# final_schematic.net
KiCad netlist of a schematic drawn in EAGLE
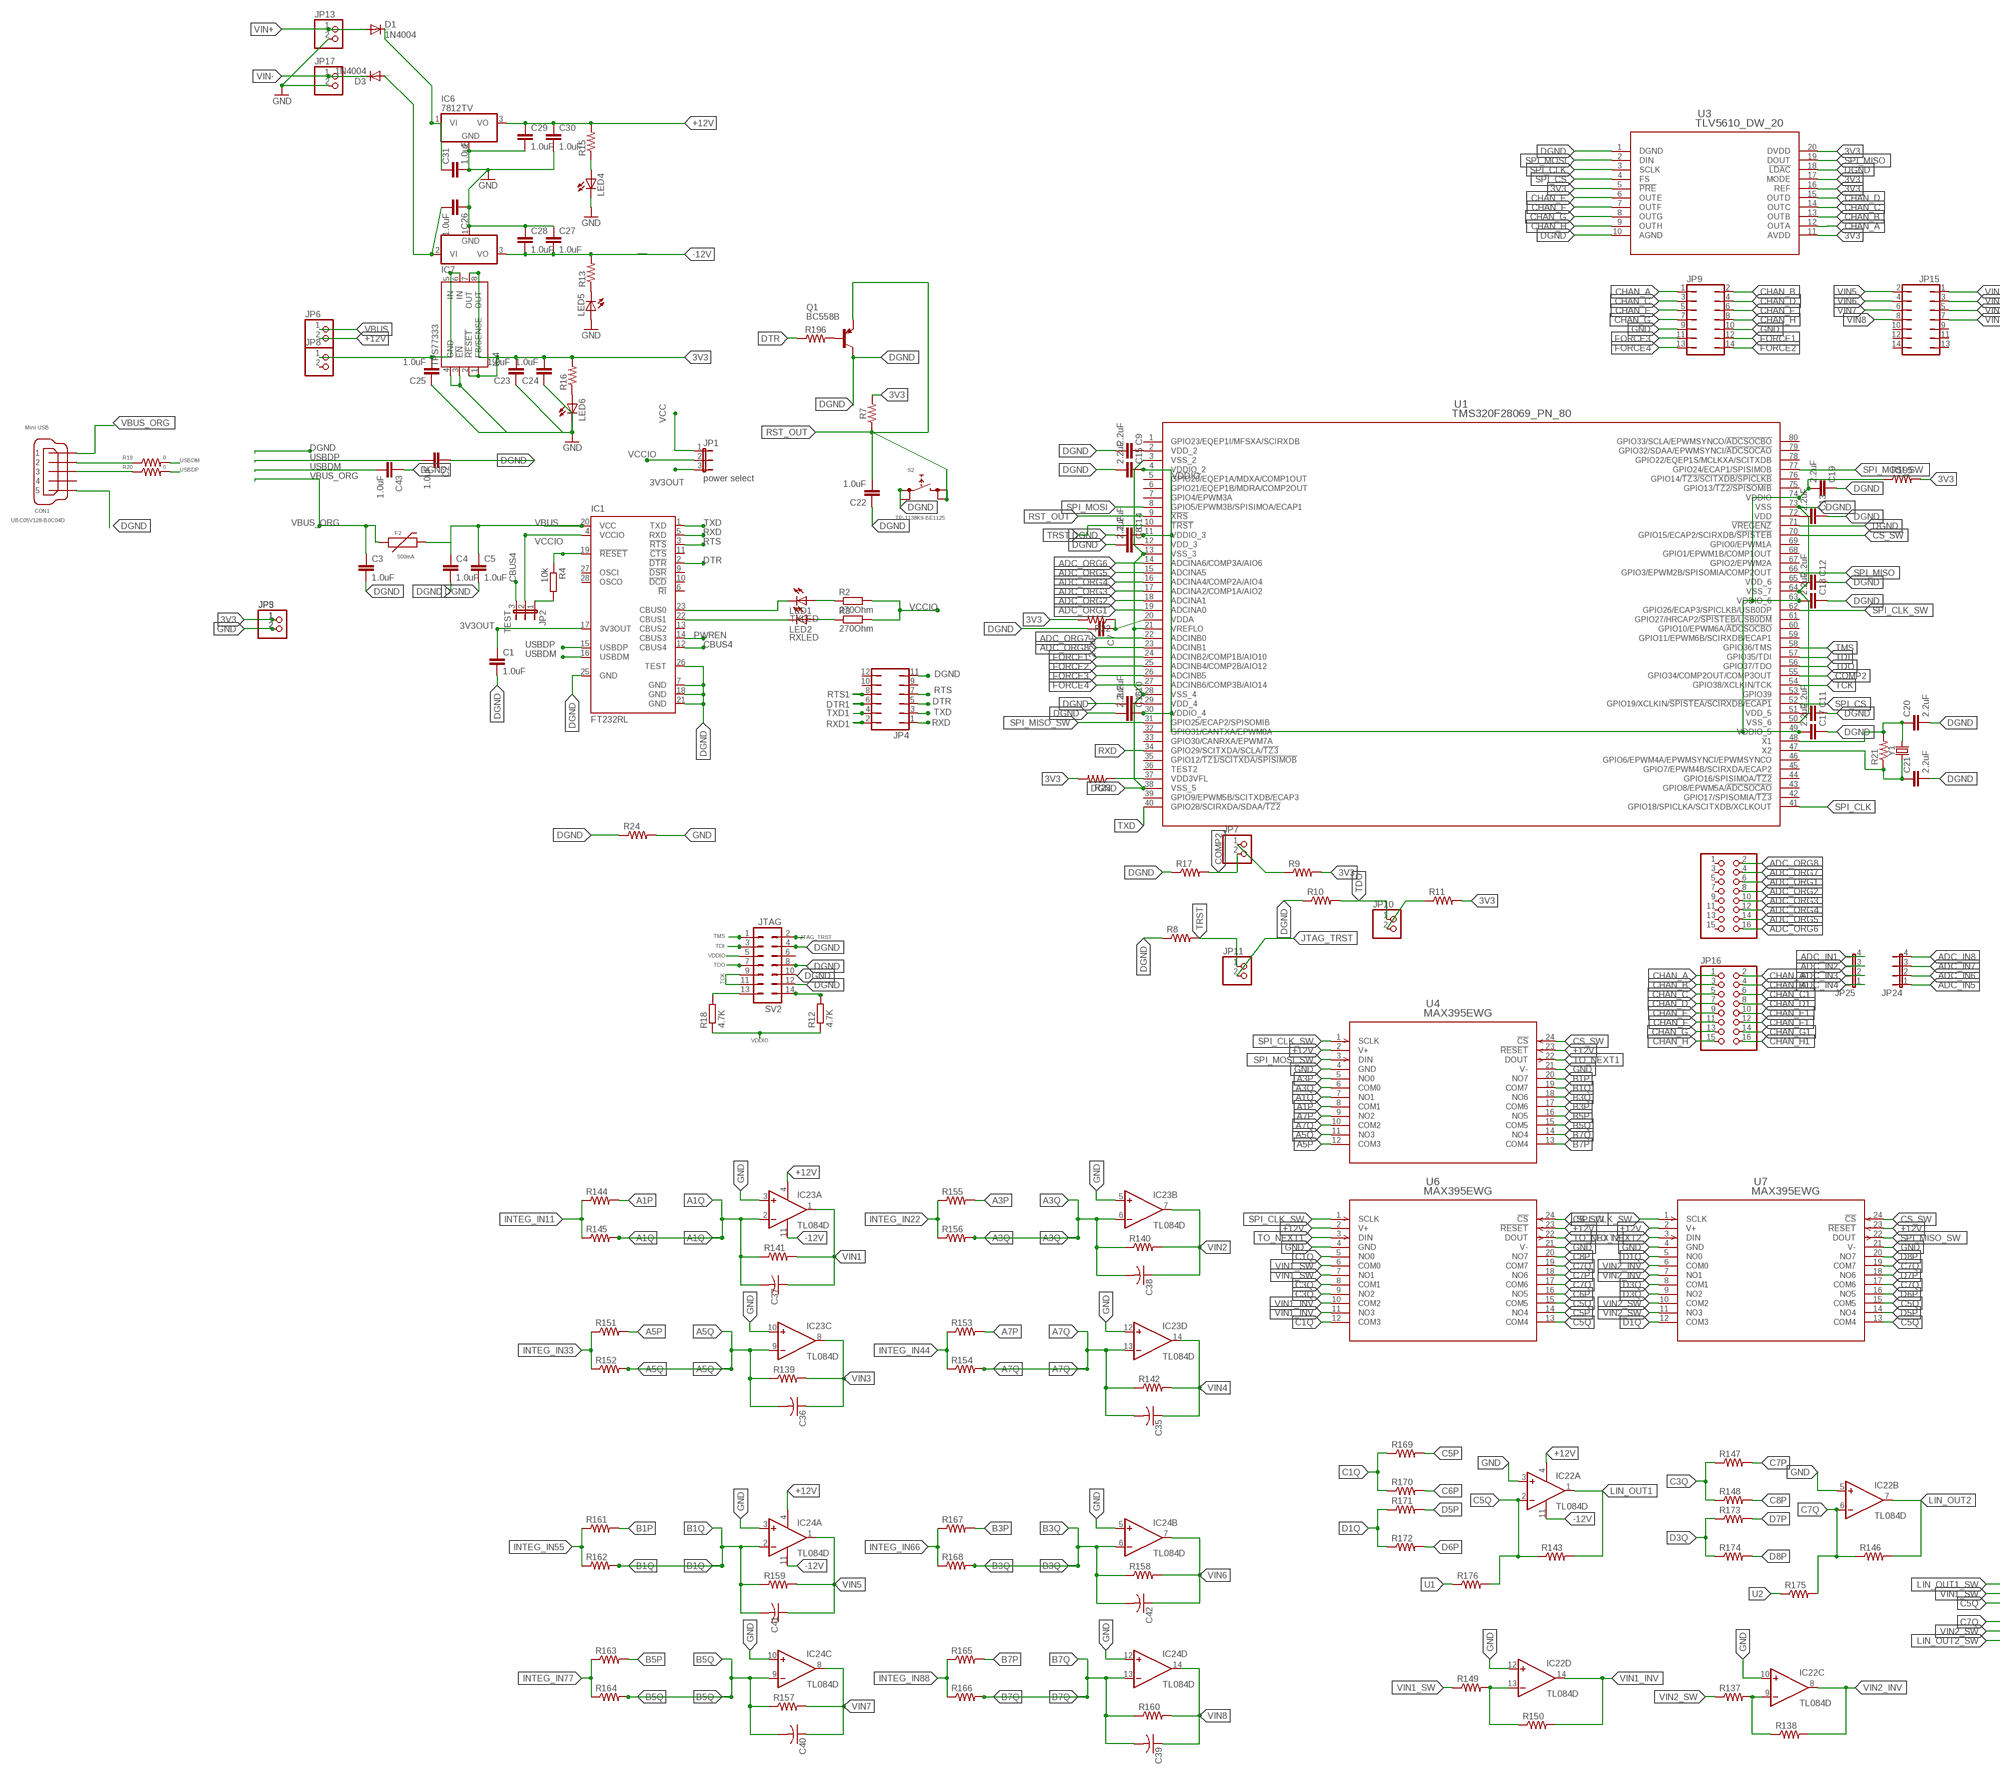
[diagram p0: schematic, sheet 1, part 1 of 3]
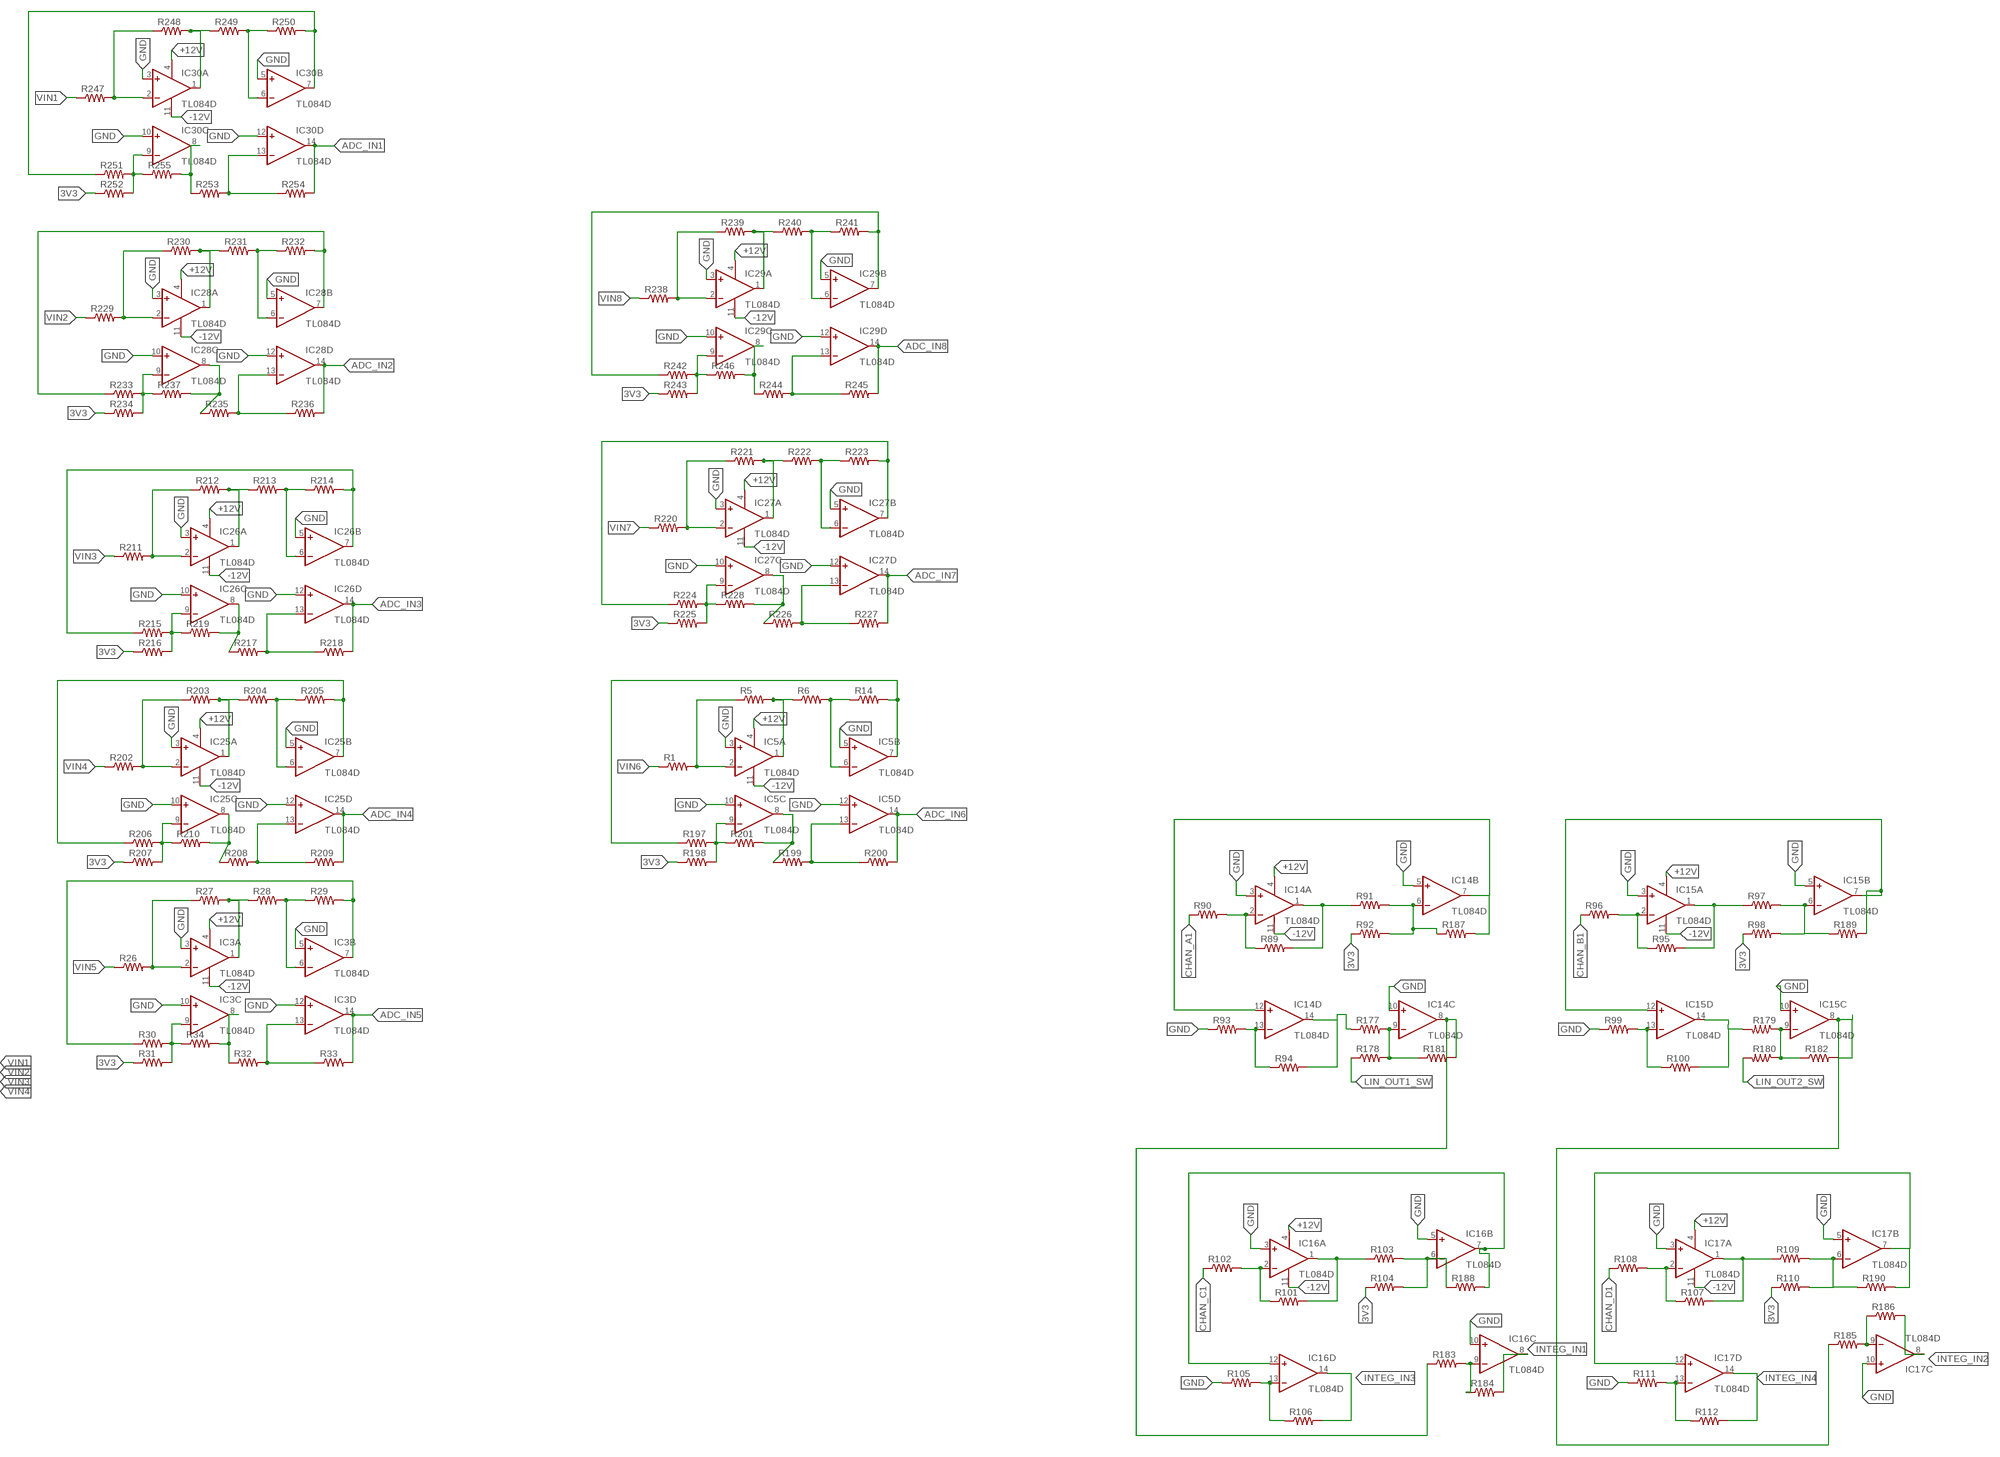
[diagram p1: schematic, sheet 1, part 2 of 3]
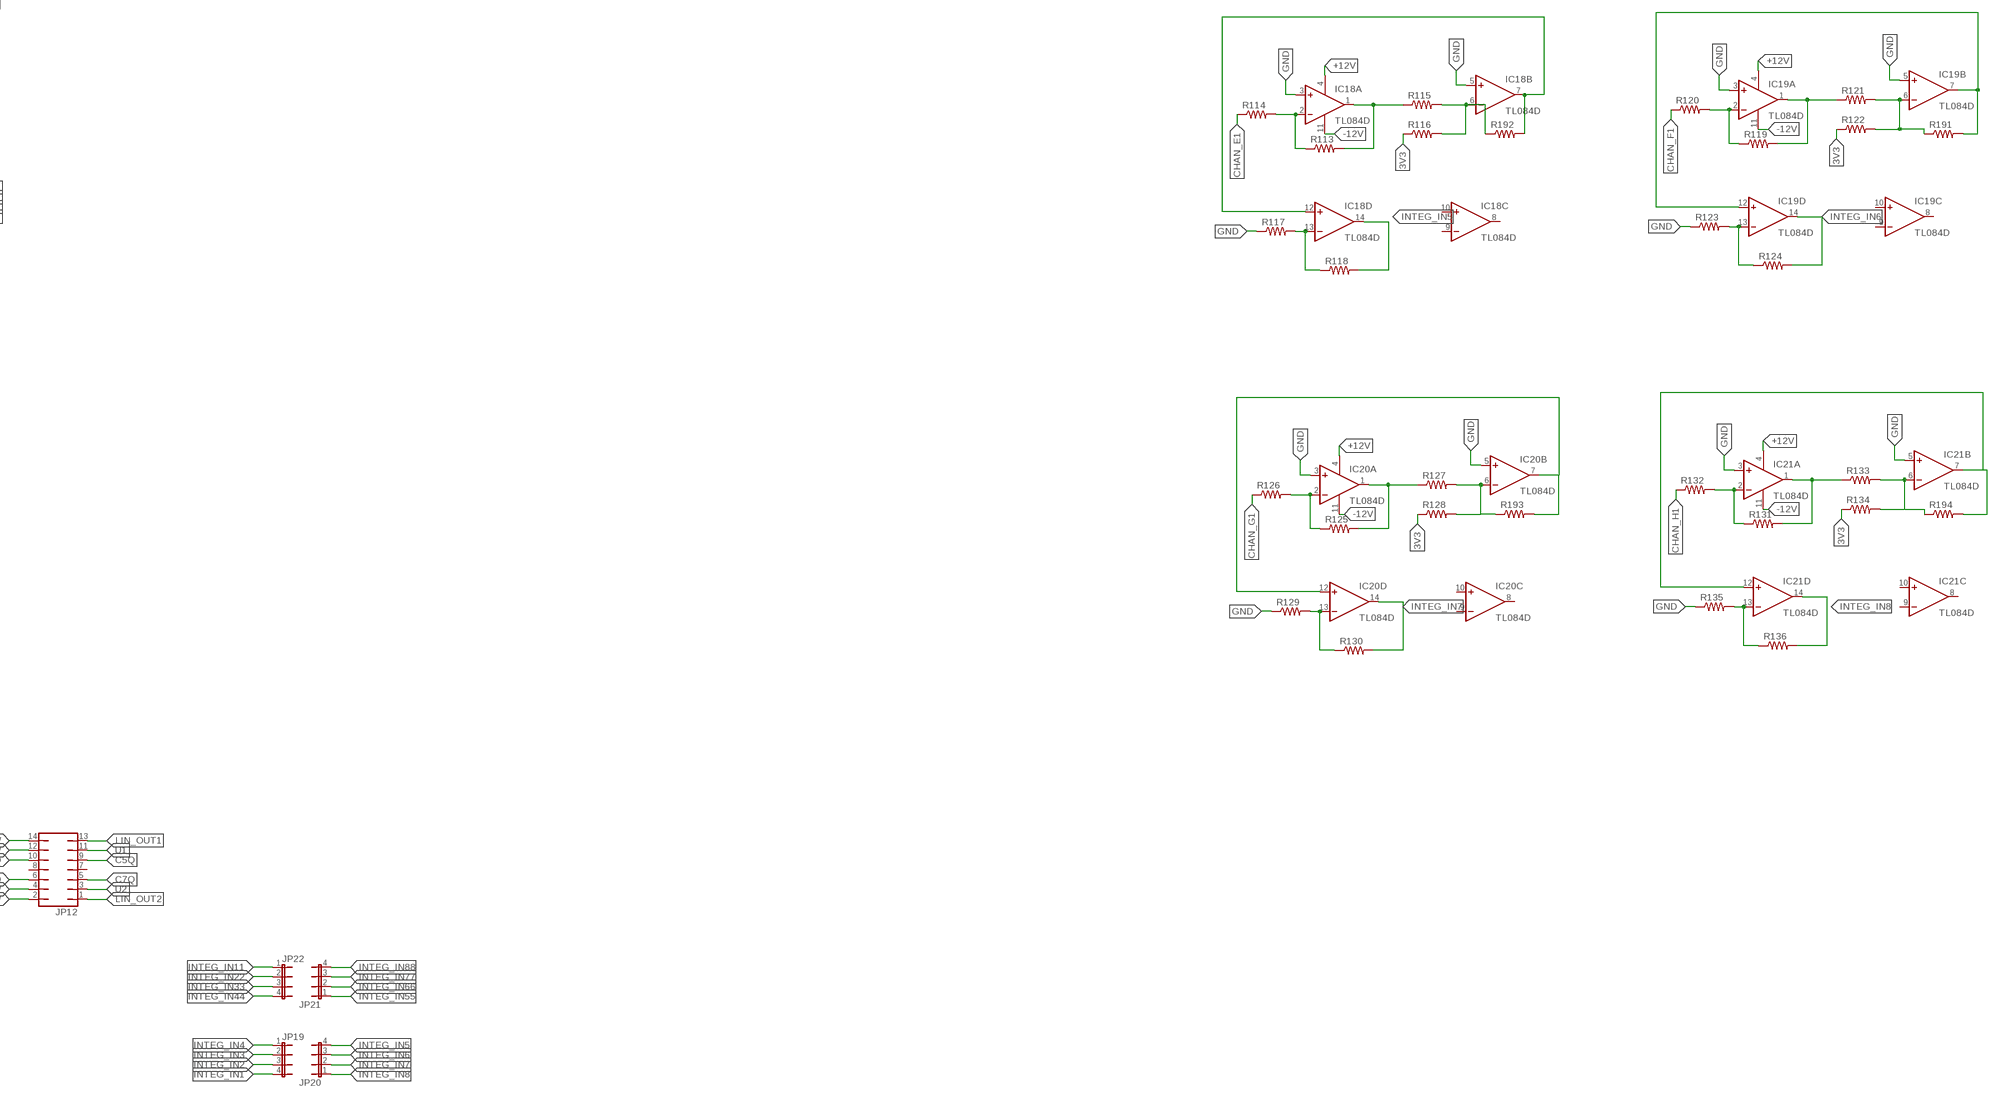
[diagram p2: schematic, sheet 1, part 3 of 3]

(export (version "E")
  (design (tool "Eeschema 10.0.6"))
  (components
    (comp (ref "C1")
      (value "1.0uF")
      (footprint "eagle-import:1206")
      (libsource (lib "eagle-import") (part "1.0UF-1206-50V-10%"))
    )
    (comp (ref "C2")
      (value "1.0uF")
      (footprint "eagle-import:1206")
      (libsource (lib "eagle-import") (part "1.0UF-1206-50V-10%"))
    )
    (comp (ref "C3")
      (value "1.0uF")
      (footprint "eagle-import:1206")
      (libsource (lib "eagle-import") (part "1.0UF-1206-50V-10%"))
    )
    (comp (ref "C4")
      (value "1.0uF")
      (footprint "eagle-import:1206")
      (libsource (lib "eagle-import") (part "1.0UF-1206-50V-10%"))
    )
    (comp (ref "C5")
      (value "1.0uF")
      (footprint "eagle-import:1206")
      (libsource (lib "eagle-import") (part "1.0UF-1206-50V-10%"))
    )
    (comp (ref "C7")
      (value "2.2uF")
      (footprint "eagle-import:1206")
      (libsource (lib "eagle-import") (part "2.2UF-1206-50V-10%"))
    )
    (comp (ref "C8")
      (value "2.2uF")
      (footprint "eagle-import:1206")
      (libsource (lib "eagle-import") (part "2.2UF-1206-50V-10%"))
    )
    (comp (ref "C9")
      (value "2.2uF")
      (footprint "eagle-import:1206")
      (libsource (lib "eagle-import") (part "2.2UF-1206-50V-10%"))
    )
    (comp (ref "C10")
      (value "2.2uF")
      (footprint "eagle-import:1206")
      (libsource (lib "eagle-import") (part "2.2UF-1206-50V-10%"))
    )
    (comp (ref "C11")
      (value "2.2uF")
      (footprint "eagle-import:1206")
      (libsource (lib "eagle-import") (part "2.2UF-1206-50V-10%"))
    )
    (comp (ref "C12")
      (value "2.2uF")
      (footprint "eagle-import:1206")
      (libsource (lib "eagle-import") (part "2.2UF-1206-50V-10%"))
    )
    (comp (ref "C13")
      (value "2.2uF")
      (footprint "eagle-import:1206")
      (libsource (lib "eagle-import") (part "2.2UF-1206-50V-10%"))
    )
    (comp (ref "C14")
      (value "2.2uF")
      (footprint "eagle-import:1206")
      (libsource (lib "eagle-import") (part "2.2UF-1206-50V-10%"))
    )
    (comp (ref "C15")
      (value "2.2uF")
      (footprint "eagle-import:1206")
      (libsource (lib "eagle-import") (part "2.2UF-1206-50V-10%"))
    )
    (comp (ref "C16")
      (value "2.2uF")
      (footprint "eagle-import:1206")
      (libsource (lib "eagle-import") (part "2.2UF-1206-50V-10%"))
    )
    (comp (ref "C17")
      (value "2.2uF")
      (footprint "eagle-import:1206")
      (libsource (lib "eagle-import") (part "2.2UF-1206-50V-10%"))
    )
    (comp (ref "C18")
      (value "2.2uF")
      (footprint "eagle-import:1206")
      (libsource (lib "eagle-import") (part "2.2UF-1206-50V-10%"))
    )
    (comp (ref "C19")
      (value "2.2uF")
      (footprint "eagle-import:1206")
      (libsource (lib "eagle-import") (part "2.2UF-1206-50V-10%"))
    )
    (comp (ref "C20")
      (value "2.2uF")
      (footprint "eagle-import:1206")
      (libsource (lib "eagle-import") (part "2.2UF-1206-50V-10%"))
    )
    (comp (ref "C21")
      (value "2.2uF")
      (footprint "eagle-import:1206")
      (libsource (lib "eagle-import") (part "2.2UF-1206-50V-10%"))
    )
    (comp (ref "C22")
      (value "1.0uF")
      (footprint "eagle-import:1206")
      (libsource (lib "eagle-import") (part "1.0UF-1206-50V-10%"))
    )
    (comp (ref "C23")
      (value "1.0uF")
      (footprint "eagle-import:1206")
      (libsource (lib "eagle-import") (part "1.0UF-1206-50V-10%"))
    )
    (comp (ref "C24")
      (value "1.0uF")
      (footprint "eagle-import:1206")
      (libsource (lib "eagle-import") (part "1.0UF-1206-50V-10%"))
    )
    (comp (ref "C25")
      (value "1.0uF")
      (footprint "eagle-import:1206")
      (libsource (lib "eagle-import") (part "1.0UF-1206-50V-10%"))
    )
    (comp (ref "C26")
      (value "1.0uF")
      (footprint "eagle-import:1206")
      (libsource (lib "eagle-import") (part "1.0UF-1206-50V-10%"))
    )
    (comp (ref "C27")
      (value "1.0uF")
      (footprint "eagle-import:1206")
      (libsource (lib "eagle-import") (part "1.0UF-1206-50V-10%"))
    )
    (comp (ref "C28")
      (value "1.0uF")
      (footprint "eagle-import:1206")
      (libsource (lib "eagle-import") (part "1.0UF-1206-50V-10%"))
    )
    (comp (ref "C29")
      (value "1.0uF")
      (footprint "eagle-import:1206")
      (libsource (lib "eagle-import") (part "1.0UF-1206-50V-10%"))
    )
    (comp (ref "C30")
      (value "1.0uF")
      (footprint "eagle-import:1206")
      (libsource (lib "eagle-import") (part "1.0UF-1206-50V-10%"))
    )
    (comp (ref "C31")
      (value "1.0uF")
      (footprint "eagle-import:1206")
      (libsource (lib "eagle-import") (part "1.0UF-1206-50V-10%"))
    )
    (comp (ref "C35")
      (value "C-USC1206")
      (footprint "eagle-import:C1206")
      (libsource (lib "eagle-import") (part "C-USC1206"))
    )
    (comp (ref "C36")
      (value "C-USC1206")
      (footprint "eagle-import:C1206")
      (libsource (lib "eagle-import") (part "C-USC1206"))
    )
    (comp (ref "C37")
      (value "C-USC1206")
      (footprint "eagle-import:C1206")
      (libsource (lib "eagle-import") (part "C-USC1206"))
    )
    (comp (ref "C38")
      (value "C-USC1206")
      (footprint "eagle-import:C1206")
      (libsource (lib "eagle-import") (part "C-USC1206"))
    )
    (comp (ref "C39")
      (value "C-USC1206")
      (footprint "eagle-import:C1206")
      (libsource (lib "eagle-import") (part "C-USC1206"))
    )
    (comp (ref "C40")
      (value "C-USC1206")
      (footprint "eagle-import:C1206")
      (libsource (lib "eagle-import") (part "C-USC1206"))
    )
    (comp (ref "C41")
      (value "C-USC1206")
      (footprint "eagle-import:C1206")
      (libsource (lib "eagle-import") (part "C-USC1206"))
    )
    (comp (ref "C42")
      (value "C-USC1206")
      (footprint "eagle-import:C1206")
      (libsource (lib "eagle-import") (part "C-USC1206"))
    )
    (comp (ref "C43")
      (value "1.0uF")
      (footprint "eagle-import:1206")
      (libsource (lib "eagle-import") (part "1.0UF-1206-50V-10%"))
    )
    (comp (ref "CON1")
      (value "UBC05V128-B0C04D")
      (footprint "eagle-import:32005-201")
      (libsource (lib "eagle-import") (part "MINI-USB-32005-201"))
    )
    (comp (ref "D1")
      (value "1N4004")
      (footprint "eagle-import:DO41-10")
      (libsource (lib "eagle-import") (part "1N4004"))
    )
    (comp (ref "D3")
      (value "1N4004")
      (footprint "eagle-import:DO41-10")
      (libsource (lib "eagle-import") (part "1N4004"))
    )
    (comp (ref "F2")
      (value "500mA")
      (footprint "eagle-import:PTC-1206")
      (libsource (lib "eagle-import") (part "PTCSMD"))
    )
    (comp (ref "IC1")
      (value "FT232RL")
      (footprint "eagle-import:SSOP28")
      (libsource (lib "eagle-import") (part "FT232RL"))
    )
    (comp (ref "IC3")
      (value "TL084D")
      (footprint "eagle-import:SO14")
      (fields (field (name "SPICEPREFIX") "B"))
      (libsource (lib "eagle-import") (part "TL084D"))
    )
    (comp (ref "IC4")
      (value "TPS77333")
      (footprint "eagle-import:DGK_S-PDSO-G8")
      (fields (field (name "MF") "TEXAS INSTRUMENTS") (field (name "MPN") "TPS77333DGK"))
      (libsource (lib "eagle-import") (part "TPS77333"))
    )
    (comp (ref "IC5")
      (value "TL084D")
      (footprint "eagle-import:SO14")
      (libsource (lib "eagle-import") (part "TL084D"))
    )
    (comp (ref "IC6")
      (value "7812TV")
      (footprint "eagle-import:TO220V")
      (libsource (lib "eagle-import") (part "78TV12"))
    )
    (comp (ref "IC7")
      (value "7912T")
      (footprint "eagle-import:TO220H")
      (libsource (lib "eagle-import") (part "79T12"))
    )
    (comp (ref "IC14")
      (value "TL084D")
      (footprint "eagle-import:SO14")
      (libsource (lib "eagle-import") (part "TL084D"))
    )
    (comp (ref "IC15")
      (value "TL084D")
      (footprint "eagle-import:SO14")
      (libsource (lib "eagle-import") (part "TL084D"))
    )
    (comp (ref "IC16")
      (value "TL084D")
      (footprint "eagle-import:SO14")
      (libsource (lib "eagle-import") (part "TL084D"))
    )
    (comp (ref "IC17")
      (value "TL084D")
      (footprint "eagle-import:SO14")
      (libsource (lib "eagle-import") (part "TL084D"))
    )
    (comp (ref "IC18")
      (value "TL084D")
      (footprint "eagle-import:SO14")
      (libsource (lib "eagle-import") (part "TL084D"))
    )
    (comp (ref "IC19")
      (value "TL084D")
      (footprint "eagle-import:SO14")
      (libsource (lib "eagle-import") (part "TL084D"))
    )
    (comp (ref "IC20")
      (value "TL084D")
      (footprint "eagle-import:SO14")
      (libsource (lib "eagle-import") (part "TL084D"))
    )
    (comp (ref "IC21")
      (value "TL084D")
      (footprint "eagle-import:SO14")
      (libsource (lib "eagle-import") (part "TL084D"))
    )
    (comp (ref "IC22")
      (value "TL084D")
      (footprint "eagle-import:SO14")
      (libsource (lib "eagle-import") (part "TL084D"))
    )
    (comp (ref "IC23")
      (value "TL084D")
      (footprint "eagle-import:SO14")
      (libsource (lib "eagle-import") (part "TL084D"))
    )
    (comp (ref "IC24")
      (value "TL084D")
      (footprint "eagle-import:SO14")
      (libsource (lib "eagle-import") (part "TL084D"))
    )
    (comp (ref "IC25")
      (value "TL084D")
      (footprint "eagle-import:SO14")
      (libsource (lib "eagle-import") (part "TL084D"))
    )
    (comp (ref "IC26")
      (value "TL084D")
      (footprint "eagle-import:SO14")
      (libsource (lib "eagle-import") (part "TL084D"))
    )
    (comp (ref "IC27")
      (value "TL084D")
      (footprint "eagle-import:SO14")
      (libsource (lib "eagle-import") (part "TL084D"))
    )
    (comp (ref "IC28")
      (value "TL084D")
      (footprint "eagle-import:SO14")
      (libsource (lib "eagle-import") (part "TL084D"))
    )
    (comp (ref "IC29")
      (value "TL084D")
      (footprint "eagle-import:SO14")
      (libsource (lib "eagle-import") (part "TL084D"))
    )
    (comp (ref "IC30")
      (value "TL084D")
      (footprint "eagle-import:SO14")
      (fields (field (name "SPICEPREFIX") "B"))
      (libsource (lib "eagle-import") (part "TL084D"))
    )
    (comp (ref "JP1")
      (value "power select")
      (footprint "eagle-import:JP2")
      (libsource (lib "eagle-import") (part "JP2E"))
    )
    (comp (ref "JP2")
      (value "TEST")
      (footprint "eagle-import:JP2")
      (libsource (lib "eagle-import") (part "JP2E"))
    )
    (comp (ref "JP3")
      (value "PINHD-1X2")
      (footprint "eagle-import:1X02")
      (libsource (lib "eagle-import") (part "PINHD-1X2"))
    )
    (comp (ref "JP4")
      (value "JP6Q")
      (footprint "eagle-import:JP6Q")
      (libsource (lib "eagle-import") (part "JP6Q"))
    )
    (comp (ref "JP5")
      (value "PINHD-1X2")
      (footprint "eagle-import:1X02")
      (libsource (lib "eagle-import") (part "PINHD-1X2"))
    )
    (comp (ref "JP6")
      (value "PINHD-1X2")
      (footprint "eagle-import:1X02")
      (libsource (lib "eagle-import") (part "PINHD-1X2"))
    )
    (comp (ref "JP7")
      (value "PINHD-1X2")
      (footprint "eagle-import:1X02")
      (libsource (lib "eagle-import") (part "PINHD-1X2"))
    )
    (comp (ref "JP8")
      (value "PINHD-1X2")
      (footprint "eagle-import:1X02")
      (libsource (lib "eagle-import") (part "PINHD-1X2"))
    )
    (comp (ref "JP9")
      (value "JP7Q")
      (footprint "eagle-import:JP7Q")
      (libsource (lib "eagle-import") (part "JP7Q"))
    )
    (comp (ref "JP10")
      (value "PINHD-1X2")
      (footprint "eagle-import:1X02")
      (libsource (lib "eagle-import") (part "PINHD-1X2"))
    )
    (comp (ref "JP11")
      (value "PINHD-1X2")
      (footprint "eagle-import:1X02")
      (libsource (lib "eagle-import") (part "PINHD-1X2"))
    )
    (comp (ref "JP12")
      (value "JP7Q")
      (footprint "eagle-import:JP7Q")
      (libsource (lib "eagle-import") (part "JP7Q"))
    )
    (comp (ref "JP13")
      (value "PINHD-1X2")
      (footprint "eagle-import:1X02")
      (libsource (lib "eagle-import") (part "PINHD-1X2"))
    )
    (comp (ref "JP15")
      (value "JP7Q")
      (footprint "eagle-import:JP7Q")
      (libsource (lib "eagle-import") (part "JP7Q"))
    )
    (comp (ref "JP16")
      (value "PINHD-2X8")
      (footprint "eagle-import:2X08")
      (libsource (lib "eagle-import") (part "PINHD-2X8"))
    )
    (comp (ref "JP17")
      (value "PINHD-1X2")
      (footprint "eagle-import:1X02")
      (libsource (lib "eagle-import") (part "PINHD-1X2"))
    )
    (comp (ref "JP18")
      (value "PINHD-2X8")
      (footprint "eagle-import:2X08")
      (libsource (lib "eagle-import") (part "PINHD-2X8"))
    )
    (comp (ref "JP19")
      (value "JP4E")
      (footprint "eagle-import:JP4")
      (libsource (lib "eagle-import") (part "JP4E"))
    )
    (comp (ref "JP20")
      (value "JP4E")
      (footprint "eagle-import:JP4")
      (libsource (lib "eagle-import") (part "JP4E"))
    )
    (comp (ref "JP21")
      (value "JP4E")
      (footprint "eagle-import:JP4")
      (libsource (lib "eagle-import") (part "JP4E"))
    )
    (comp (ref "JP22")
      (value "JP4E")
      (footprint "eagle-import:JP4")
      (libsource (lib "eagle-import") (part "JP4E"))
    )
    (comp (ref "JP24")
      (value "JP4E")
      (footprint "eagle-import:JP4")
      (libsource (lib "eagle-import") (part "JP4E"))
    )
    (comp (ref "JP25")
      (value "JP4E")
      (footprint "eagle-import:JP4")
      (libsource (lib "eagle-import") (part "JP4E"))
    )
    (comp (ref "LED1")
      (value "TXLED")
      (footprint "eagle-import:CHIPLED_1206")
      (libsource (lib "eagle-import") (part "LEDCHIPLED_1206"))
    )
    (comp (ref "LED2")
      (value "RXLED")
      (footprint "eagle-import:CHIPLED_1206")
      (libsource (lib "eagle-import") (part "LEDCHIPLED_1206"))
    )
    (comp (ref "LED4")
      (value "LED3MM")
      (footprint "eagle-import:LED3MM")
      (libsource (lib "eagle-import") (part "led_259_LED3MM"))
    )
    (comp (ref "LED5")
      (value "LED3MM")
      (footprint "eagle-import:LED3MM")
      (libsource (lib "eagle-import") (part "led_259_LED3MM"))
    )
    (comp (ref "LED6")
      (value "LED3MM")
      (footprint "eagle-import:LED3MM")
      (libsource (lib "eagle-import") (part "led_259_LED3MM"))
    )
    (comp (ref "Q1")
      (value "BC558B")
      (footprint "eagle-import:TO92-EBC")
      (libsource (lib "eagle-import") (part "BC558B"))
    )
    (comp (ref "R1")
      (value "R-US_R1206")
      (footprint "eagle-import:R1206")
      (libsource (lib "eagle-import") (part "rcl_334_R-US_R1206"))
    )
    (comp (ref "R2")
      (value "270Ohm")
      (footprint "eagle-import:M1206")
      (libsource (lib "eagle-import") (part "R-EU_M1206"))
    )
    (comp (ref "R3")
      (value "270Ohm")
      (footprint "eagle-import:M1206")
      (libsource (lib "eagle-import") (part "R-EU_M1206"))
    )
    (comp (ref "R4")
      (value "10k")
      (footprint "eagle-import:M1206")
      (libsource (lib "eagle-import") (part "R-EU_M1206"))
    )
    (comp (ref "R5")
      (value "R-US_R1206")
      (footprint "eagle-import:R1206")
      (libsource (lib "eagle-import") (part "rcl_334_R-US_R1206"))
    )
    (comp (ref "R6")
      (value "R-US_R1206")
      (footprint "eagle-import:R1206")
      (libsource (lib "eagle-import") (part "rcl_334_R-US_R1206"))
    )
    (comp (ref "R7")
      (value "RESISTOR1206")
      (footprint "eagle-import:1206")
      (libsource (lib "eagle-import") (part "RESISTOR1206"))
    )
    (comp (ref "R8")
      (value "R-US_R1206")
      (footprint "eagle-import:R1206")
      (libsource (lib "eagle-import") (part "rcl_334_R-US_R1206"))
    )
    (comp (ref "R9")
      (value "R-US_R1206")
      (footprint "eagle-import:R1206")
      (libsource (lib "eagle-import") (part "rcl_334_R-US_R1206"))
    )
    (comp (ref "R10")
      (value "R-US_R1206")
      (footprint "eagle-import:R1206")
      (libsource (lib "eagle-import") (part "rcl_334_R-US_R1206"))
    )
    (comp (ref "R11")
      (value "R-US_R1206")
      (footprint "eagle-import:R1206")
      (libsource (lib "eagle-import") (part "rcl_334_R-US_R1206"))
    )
    (comp (ref "R12")
      (value "4.7K")
      (footprint "eagle-import:M1206")
      (libsource (lib "eagle-import") (part "R-EU_M1206"))
    )
    (comp (ref "R13")
      (value "R-US_R1206")
      (footprint "eagle-import:R1206")
      (libsource (lib "eagle-import") (part "rcl_334_R-US_R1206"))
    )
    (comp (ref "R14")
      (value "R-US_R1206")
      (footprint "eagle-import:R1206")
      (libsource (lib "eagle-import") (part "rcl_334_R-US_R1206"))
    )
    (comp (ref "R15")
      (value "R-US_R1206")
      (footprint "eagle-import:R1206")
      (libsource (lib "eagle-import") (part "rcl_334_R-US_R1206"))
    )
    (comp (ref "R16")
      (value "R-US_R1206")
      (footprint "eagle-import:R1206")
      (libsource (lib "eagle-import") (part "rcl_334_R-US_R1206"))
    )
    (comp (ref "R17")
      (value "R-US_R1206")
      (footprint "eagle-import:R1206")
      (libsource (lib "eagle-import") (part "rcl_334_R-US_R1206"))
    )
    (comp (ref "R18")
      (value "4.7K")
      (footprint "eagle-import:M1206")
      (libsource (lib "eagle-import") (part "R-EU_M1206"))
    )
    (comp (ref "R19")
      (value "0")
      (footprint "eagle-import:R1206")
      (libsource (lib "eagle-import") (part "rcl_R-US_R1206"))
    )
    (comp (ref "R20")
      (value "0")
      (footprint "eagle-import:R1206W")
      (libsource (lib "eagle-import") (part "rcl_R-US_R1206W"))
    )
    (comp (ref "R21")
      (value "R-US_R1206")
      (footprint "eagle-import:R1206")
      (libsource (lib "eagle-import") (part "rcl_334_R-US_R1206"))
    )
    (comp (ref "R22")
      (value "R-US_R1206")
      (footprint "eagle-import:R1206")
      (libsource (lib "eagle-import") (part "rcl_334_R-US_R1206"))
    )
    (comp (ref "R23")
      (value "R-US_R1206")
      (footprint "eagle-import:R1206")
      (libsource (lib "eagle-import") (part "rcl_334_R-US_R1206"))
    )
    (comp (ref "R24")
      (value "R-US_0207/7")
      (footprint "eagle-import:0207_7")
      (libsource (lib "eagle-import") (part "R-US_0207/7"))
    )
    (comp (ref "R26")
      (value "R-US_R1206")
      (footprint "eagle-import:R1206")
      (libsource (lib "eagle-import") (part "rcl_334_R-US_R1206"))
    )
    (comp (ref "R27")
      (value "R-US_R1206")
      (footprint "eagle-import:R1206")
      (libsource (lib "eagle-import") (part "rcl_334_R-US_R1206"))
    )
    (comp (ref "R28")
      (value "R-US_R1206")
      (footprint "eagle-import:R1206")
      (libsource (lib "eagle-import") (part "rcl_334_R-US_R1206"))
    )
    (comp (ref "R29")
      (value "R-US_R1206")
      (footprint "eagle-import:R1206")
      (libsource (lib "eagle-import") (part "rcl_334_R-US_R1206"))
    )
    (comp (ref "R30")
      (value "R-US_R1206")
      (footprint "eagle-import:R1206")
      (libsource (lib "eagle-import") (part "rcl_334_R-US_R1206"))
    )
    (comp (ref "R31")
      (value "R-US_R1206")
      (footprint "eagle-import:R1206")
      (libsource (lib "eagle-import") (part "rcl_334_R-US_R1206"))
    )
    (comp (ref "R32")
      (value "R-US_R1206")
      (footprint "eagle-import:R1206")
      (libsource (lib "eagle-import") (part "rcl_334_R-US_R1206"))
    )
    (comp (ref "R33")
      (value "R-US_R1206")
      (footprint "eagle-import:R1206")
      (libsource (lib "eagle-import") (part "rcl_334_R-US_R1206"))
    )
    (comp (ref "R34")
      (value "R-US_R1206")
      (footprint "eagle-import:R1206")
      (libsource (lib "eagle-import") (part "rcl_334_R-US_R1206"))
    )
    (comp (ref "R89")
      (value "R-US_R1206")
      (footprint "eagle-import:R1206")
      (libsource (lib "eagle-import") (part "rcl_334_R-US_R1206"))
    )
    (comp (ref "R90")
      (value "R-US_R1206")
      (footprint "eagle-import:R1206")
      (libsource (lib "eagle-import") (part "rcl_334_R-US_R1206"))
    )
    (comp (ref "R91")
      (value "R-US_R1206")
      (footprint "eagle-import:R1206")
      (libsource (lib "eagle-import") (part "rcl_334_R-US_R1206"))
    )
    (comp (ref "R92")
      (value "R-US_R1206")
      (footprint "eagle-import:R1206")
      (libsource (lib "eagle-import") (part "rcl_334_R-US_R1206"))
    )
    (comp (ref "R93")
      (value "R-US_R1206")
      (footprint "eagle-import:R1206")
      (libsource (lib "eagle-import") (part "rcl_334_R-US_R1206"))
    )
    (comp (ref "R94")
      (value "R-US_R1206")
      (footprint "eagle-import:R1206")
      (libsource (lib "eagle-import") (part "rcl_334_R-US_R1206"))
    )
    (comp (ref "R95")
      (value "R-US_R1206")
      (footprint "eagle-import:R1206")
      (libsource (lib "eagle-import") (part "rcl_334_R-US_R1206"))
    )
    (comp (ref "R96")
      (value "R-US_R1206")
      (footprint "eagle-import:R1206")
      (libsource (lib "eagle-import") (part "rcl_334_R-US_R1206"))
    )
    (comp (ref "R97")
      (value "R-US_R1206")
      (footprint "eagle-import:R1206")
      (libsource (lib "eagle-import") (part "rcl_334_R-US_R1206"))
    )
    (comp (ref "R98")
      (value "R-US_R1206")
      (footprint "eagle-import:R1206")
      (libsource (lib "eagle-import") (part "rcl_334_R-US_R1206"))
    )
    (comp (ref "R99")
      (value "R-US_R1206")
      (footprint "eagle-import:R1206")
      (libsource (lib "eagle-import") (part "rcl_334_R-US_R1206"))
    )
    (comp (ref "R100")
      (value "R-US_R1206")
      (footprint "eagle-import:R1206")
      (libsource (lib "eagle-import") (part "rcl_334_R-US_R1206"))
    )
    (comp (ref "R101")
      (value "R-US_R1206")
      (footprint "eagle-import:R1206")
      (libsource (lib "eagle-import") (part "rcl_334_R-US_R1206"))
    )
    (comp (ref "R102")
      (value "R-US_R1206")
      (footprint "eagle-import:R1206")
      (libsource (lib "eagle-import") (part "rcl_334_R-US_R1206"))
    )
    (comp (ref "R103")
      (value "R-US_R1206")
      (footprint "eagle-import:R1206")
      (libsource (lib "eagle-import") (part "rcl_334_R-US_R1206"))
    )
    (comp (ref "R104")
      (value "R-US_R1206")
      (footprint "eagle-import:R1206")
      (libsource (lib "eagle-import") (part "rcl_334_R-US_R1206"))
    )
    (comp (ref "R105")
      (value "R-US_R1206")
      (footprint "eagle-import:R1206")
      (libsource (lib "eagle-import") (part "rcl_334_R-US_R1206"))
    )
    (comp (ref "R106")
      (value "R-US_R1206")
      (footprint "eagle-import:R1206")
      (libsource (lib "eagle-import") (part "rcl_334_R-US_R1206"))
    )
    (comp (ref "R107")
      (value "R-US_R1206")
      (footprint "eagle-import:R1206")
      (libsource (lib "eagle-import") (part "rcl_334_R-US_R1206"))
    )
    (comp (ref "R108")
      (value "R-US_R1206")
      (footprint "eagle-import:R1206")
      (libsource (lib "eagle-import") (part "rcl_334_R-US_R1206"))
    )
    (comp (ref "R109")
      (value "R-US_R1206")
      (footprint "eagle-import:R1206")
      (libsource (lib "eagle-import") (part "rcl_334_R-US_R1206"))
    )
    (comp (ref "R110")
      (value "R-US_R1206")
      (footprint "eagle-import:R1206")
      (libsource (lib "eagle-import") (part "rcl_334_R-US_R1206"))
    )
    (comp (ref "R111")
      (value "R-US_R1206")
      (footprint "eagle-import:R1206")
      (libsource (lib "eagle-import") (part "rcl_334_R-US_R1206"))
    )
    (comp (ref "R112")
      (value "R-US_R1206")
      (footprint "eagle-import:R1206")
      (libsource (lib "eagle-import") (part "rcl_334_R-US_R1206"))
    )
    (comp (ref "R113")
      (value "R-US_R1206")
      (footprint "eagle-import:R1206")
      (libsource (lib "eagle-import") (part "rcl_334_R-US_R1206"))
    )
    (comp (ref "R114")
      (value "R-US_R1206")
      (footprint "eagle-import:R1206")
      (libsource (lib "eagle-import") (part "rcl_334_R-US_R1206"))
    )
    (comp (ref "R115")
      (value "R-US_R1206")
      (footprint "eagle-import:R1206")
      (libsource (lib "eagle-import") (part "rcl_334_R-US_R1206"))
    )
    (comp (ref "R116")
      (value "R-US_R1206")
      (footprint "eagle-import:R1206")
      (libsource (lib "eagle-import") (part "rcl_334_R-US_R1206"))
    )
    (comp (ref "R117")
      (value "R-US_R1206")
      (footprint "eagle-import:R1206")
      (libsource (lib "eagle-import") (part "rcl_334_R-US_R1206"))
    )
    (comp (ref "R118")
      (value "R-US_R1206")
      (footprint "eagle-import:R1206")
      (libsource (lib "eagle-import") (part "rcl_334_R-US_R1206"))
    )
    (comp (ref "R119")
      (value "R-US_R1206")
      (footprint "eagle-import:R1206")
      (libsource (lib "eagle-import") (part "rcl_334_R-US_R1206"))
    )
    (comp (ref "R120")
      (value "R-US_R1206")
      (footprint "eagle-import:R1206")
      (libsource (lib "eagle-import") (part "rcl_334_R-US_R1206"))
    )
    (comp (ref "R121")
      (value "R-US_R1206")
      (footprint "eagle-import:R1206")
      (libsource (lib "eagle-import") (part "rcl_334_R-US_R1206"))
    )
    (comp (ref "R122")
      (value "R-US_R1206")
      (footprint "eagle-import:R1206")
      (libsource (lib "eagle-import") (part "rcl_334_R-US_R1206"))
    )
    (comp (ref "R123")
      (value "R-US_R1206")
      (footprint "eagle-import:R1206")
      (libsource (lib "eagle-import") (part "rcl_334_R-US_R1206"))
    )
    (comp (ref "R124")
      (value "R-US_R1206")
      (footprint "eagle-import:R1206")
      (libsource (lib "eagle-import") (part "rcl_334_R-US_R1206"))
    )
    (comp (ref "R125")
      (value "R-US_R1206")
      (footprint "eagle-import:R1206")
      (libsource (lib "eagle-import") (part "rcl_334_R-US_R1206"))
    )
    (comp (ref "R126")
      (value "R-US_R1206")
      (footprint "eagle-import:R1206")
      (libsource (lib "eagle-import") (part "rcl_334_R-US_R1206"))
    )
    (comp (ref "R127")
      (value "R-US_R1206")
      (footprint "eagle-import:R1206")
      (libsource (lib "eagle-import") (part "rcl_334_R-US_R1206"))
    )
    (comp (ref "R128")
      (value "R-US_R1206")
      (footprint "eagle-import:R1206")
      (libsource (lib "eagle-import") (part "rcl_334_R-US_R1206"))
    )
    (comp (ref "R129")
      (value "R-US_R1206")
      (footprint "eagle-import:R1206")
      (libsource (lib "eagle-import") (part "rcl_334_R-US_R1206"))
    )
    (comp (ref "R130")
      (value "R-US_R1206")
      (footprint "eagle-import:R1206")
      (libsource (lib "eagle-import") (part "rcl_334_R-US_R1206"))
    )
    (comp (ref "R131")
      (value "R-US_R1206")
      (footprint "eagle-import:R1206")
      (libsource (lib "eagle-import") (part "rcl_334_R-US_R1206"))
    )
    (comp (ref "R132")
      (value "R-US_R1206")
      (footprint "eagle-import:R1206")
      (libsource (lib "eagle-import") (part "rcl_334_R-US_R1206"))
    )
    (comp (ref "R133")
      (value "R-US_R1206")
      (footprint "eagle-import:R1206")
      (libsource (lib "eagle-import") (part "rcl_334_R-US_R1206"))
    )
    (comp (ref "R134")
      (value "R-US_R1206")
      (footprint "eagle-import:R1206")
      (libsource (lib "eagle-import") (part "rcl_334_R-US_R1206"))
    )
    (comp (ref "R135")
      (value "R-US_R1206")
      (footprint "eagle-import:R1206")
      (libsource (lib "eagle-import") (part "rcl_334_R-US_R1206"))
    )
    (comp (ref "R136")
      (value "R-US_R1206")
      (footprint "eagle-import:R1206")
      (libsource (lib "eagle-import") (part "rcl_334_R-US_R1206"))
    )
    (comp (ref "R137")
      (value "R-US_R1206")
      (footprint "eagle-import:R1206")
      (libsource (lib "eagle-import") (part "rcl_334_R-US_R1206"))
    )
    (comp (ref "R138")
      (value "R-US_R1206")
      (footprint "eagle-import:R1206")
      (libsource (lib "eagle-import") (part "rcl_334_R-US_R1206"))
    )
    (comp (ref "R139")
      (value "R-US_R1206")
      (footprint "eagle-import:R1206")
      (libsource (lib "eagle-import") (part "rcl_334_R-US_R1206"))
    )
    (comp (ref "R140")
      (value "R-US_R1206")
      (footprint "eagle-import:R1206")
      (libsource (lib "eagle-import") (part "rcl_334_R-US_R1206"))
    )
    (comp (ref "R141")
      (value "R-US_R1206")
      (footprint "eagle-import:R1206")
      (libsource (lib "eagle-import") (part "rcl_334_R-US_R1206"))
    )
    (comp (ref "R142")
      (value "R-US_R1206")
      (footprint "eagle-import:R1206")
      (libsource (lib "eagle-import") (part "rcl_334_R-US_R1206"))
    )
    (comp (ref "R143")
      (value "R-US_R1206")
      (footprint "eagle-import:R1206")
      (libsource (lib "eagle-import") (part "rcl_334_R-US_R1206"))
    )
    (comp (ref "R144")
      (value "R-US_R1206")
      (footprint "eagle-import:R1206")
      (libsource (lib "eagle-import") (part "rcl_334_R-US_R1206"))
    )
    (comp (ref "R145")
      (value "R-US_R1206")
      (footprint "eagle-import:R1206")
      (libsource (lib "eagle-import") (part "rcl_334_R-US_R1206"))
    )
    (comp (ref "R146")
      (value "R-US_R1206")
      (footprint "eagle-import:R1206")
      (libsource (lib "eagle-import") (part "rcl_334_R-US_R1206"))
    )
    (comp (ref "R147")
      (value "R-US_R1206")
      (footprint "eagle-import:R1206")
      (libsource (lib "eagle-import") (part "rcl_334_R-US_R1206"))
    )
    (comp (ref "R148")
      (value "R-US_R1206")
      (footprint "eagle-import:R1206")
      (libsource (lib "eagle-import") (part "rcl_334_R-US_R1206"))
    )
    (comp (ref "R149")
      (value "R-US_R1206")
      (footprint "eagle-import:R1206")
      (libsource (lib "eagle-import") (part "rcl_334_R-US_R1206"))
    )
    (comp (ref "R150")
      (value "R-US_R1206")
      (footprint "eagle-import:R1206")
      (libsource (lib "eagle-import") (part "rcl_334_R-US_R1206"))
    )
    (comp (ref "R151")
      (value "R-US_R1206")
      (footprint "eagle-import:R1206")
      (libsource (lib "eagle-import") (part "rcl_334_R-US_R1206"))
    )
    (comp (ref "R152")
      (value "R-US_R1206")
      (footprint "eagle-import:R1206")
      (libsource (lib "eagle-import") (part "rcl_334_R-US_R1206"))
    )
    (comp (ref "R153")
      (value "R-US_R1206")
      (footprint "eagle-import:R1206")
      (libsource (lib "eagle-import") (part "rcl_334_R-US_R1206"))
    )
    (comp (ref "R154")
      (value "R-US_R1206")
      (footprint "eagle-import:R1206")
      (libsource (lib "eagle-import") (part "rcl_334_R-US_R1206"))
    )
    (comp (ref "R155")
      (value "R-US_R1206")
      (footprint "eagle-import:R1206")
      (libsource (lib "eagle-import") (part "rcl_334_R-US_R1206"))
    )
    (comp (ref "R156")
      (value "R-US_R1206")
      (footprint "eagle-import:R1206")
      (libsource (lib "eagle-import") (part "rcl_334_R-US_R1206"))
    )
    (comp (ref "R157")
      (value "R-US_R1206")
      (footprint "eagle-import:R1206")
      (libsource (lib "eagle-import") (part "rcl_334_R-US_R1206"))
    )
    (comp (ref "R158")
      (value "R-US_R1206")
      (footprint "eagle-import:R1206")
      (libsource (lib "eagle-import") (part "rcl_334_R-US_R1206"))
    )
    (comp (ref "R159")
      (value "R-US_R1206")
      (footprint "eagle-import:R1206")
      (libsource (lib "eagle-import") (part "rcl_334_R-US_R1206"))
    )
    (comp (ref "R160")
      (value "R-US_R1206")
      (footprint "eagle-import:R1206")
      (libsource (lib "eagle-import") (part "rcl_334_R-US_R1206"))
    )
    (comp (ref "R161")
      (value "R-US_R1206")
      (footprint "eagle-import:R1206")
      (libsource (lib "eagle-import") (part "rcl_334_R-US_R1206"))
    )
    (comp (ref "R162")
      (value "R-US_R1206")
      (footprint "eagle-import:R1206")
      (libsource (lib "eagle-import") (part "rcl_334_R-US_R1206"))
    )
    (comp (ref "R163")
      (value "R-US_R1206")
      (footprint "eagle-import:R1206")
      (libsource (lib "eagle-import") (part "rcl_334_R-US_R1206"))
    )
    (comp (ref "R164")
      (value "R-US_R1206")
      (footprint "eagle-import:R1206")
      (libsource (lib "eagle-import") (part "rcl_334_R-US_R1206"))
    )
    (comp (ref "R165")
      (value "R-US_R1206")
      (footprint "eagle-import:R1206")
      (libsource (lib "eagle-import") (part "rcl_334_R-US_R1206"))
    )
    (comp (ref "R166")
      (value "R-US_R1206")
      (footprint "eagle-import:R1206")
      (libsource (lib "eagle-import") (part "rcl_334_R-US_R1206"))
    )
    (comp (ref "R167")
      (value "R-US_R1206")
      (footprint "eagle-import:R1206")
      (libsource (lib "eagle-import") (part "rcl_334_R-US_R1206"))
    )
    (comp (ref "R168")
      (value "R-US_R1206")
      (footprint "eagle-import:R1206")
      (libsource (lib "eagle-import") (part "rcl_334_R-US_R1206"))
    )
    (comp (ref "R169")
      (value "R-US_R1206")
      (footprint "eagle-import:R1206")
      (libsource (lib "eagle-import") (part "rcl_334_R-US_R1206"))
    )
    (comp (ref "R170")
      (value "R-US_R1206")
      (footprint "eagle-import:R1206")
      (libsource (lib "eagle-import") (part "rcl_334_R-US_R1206"))
    )
    (comp (ref "R171")
      (value "R-US_R1206")
      (footprint "eagle-import:R1206")
      (libsource (lib "eagle-import") (part "rcl_334_R-US_R1206"))
    )
    (comp (ref "R172")
      (value "R-US_R1206")
      (footprint "eagle-import:R1206")
      (libsource (lib "eagle-import") (part "rcl_334_R-US_R1206"))
    )
    (comp (ref "R173")
      (value "R-US_R1206")
      (footprint "eagle-import:R1206")
      (libsource (lib "eagle-import") (part "rcl_334_R-US_R1206"))
    )
    (comp (ref "R174")
      (value "R-US_R1206")
      (footprint "eagle-import:R1206")
      (libsource (lib "eagle-import") (part "rcl_334_R-US_R1206"))
    )
    (comp (ref "R175")
      (value "R-US_R1206")
      (footprint "eagle-import:R1206")
      (libsource (lib "eagle-import") (part "rcl_334_R-US_R1206"))
    )
    (comp (ref "R176")
      (value "R-US_R1206")
      (footprint "eagle-import:R1206")
      (libsource (lib "eagle-import") (part "rcl_334_R-US_R1206"))
    )
    (comp (ref "R177")
      (value "R-US_R1206")
      (footprint "eagle-import:R1206")
      (libsource (lib "eagle-import") (part "rcl_334_R-US_R1206"))
    )
    (comp (ref "R178")
      (value "R-US_R1206")
      (footprint "eagle-import:R1206")
      (libsource (lib "eagle-import") (part "rcl_334_R-US_R1206"))
    )
    (comp (ref "R179")
      (value "R-US_R1206")
      (footprint "eagle-import:R1206")
      (libsource (lib "eagle-import") (part "rcl_334_R-US_R1206"))
    )
    (comp (ref "R180")
      (value "R-US_R1206")
      (footprint "eagle-import:R1206")
      (libsource (lib "eagle-import") (part "rcl_334_R-US_R1206"))
    )
    (comp (ref "R181")
      (value "R-US_R1206")
      (footprint "eagle-import:R1206")
      (libsource (lib "eagle-import") (part "rcl_334_R-US_R1206"))
    )
    (comp (ref "R182")
      (value "R-US_R1206")
      (footprint "eagle-import:R1206")
      (libsource (lib "eagle-import") (part "rcl_334_R-US_R1206"))
    )
    (comp (ref "R183")
      (value "R-US_R1206")
      (footprint "eagle-import:R1206")
      (libsource (lib "eagle-import") (part "rcl_334_R-US_R1206"))
    )
    (comp (ref "R184")
      (value "R-US_R1206")
      (footprint "eagle-import:R1206")
      (libsource (lib "eagle-import") (part "rcl_334_R-US_R1206"))
    )
    (comp (ref "R185")
      (value "R-US_R1206")
      (footprint "eagle-import:R1206")
      (libsource (lib "eagle-import") (part "rcl_334_R-US_R1206"))
    )
    (comp (ref "R186")
      (value "R-US_R1206")
      (footprint "eagle-import:R1206")
      (libsource (lib "eagle-import") (part "rcl_334_R-US_R1206"))
    )
    (comp (ref "R187")
      (value "R-US_R1206")
      (footprint "eagle-import:R1206")
      (libsource (lib "eagle-import") (part "rcl_334_R-US_R1206"))
    )
    (comp (ref "R188")
      (value "R-US_R1206")
      (footprint "eagle-import:R1206")
      (libsource (lib "eagle-import") (part "rcl_334_R-US_R1206"))
    )
    (comp (ref "R189")
      (value "R-US_R1206")
      (footprint "eagle-import:R1206")
      (libsource (lib "eagle-import") (part "rcl_334_R-US_R1206"))
    )
    (comp (ref "R190")
      (value "R-US_R1206")
      (footprint "eagle-import:R1206")
      (libsource (lib "eagle-import") (part "rcl_334_R-US_R1206"))
    )
    (comp (ref "R191")
      (value "R-US_R1206")
      (footprint "eagle-import:R1206")
      (libsource (lib "eagle-import") (part "rcl_334_R-US_R1206"))
    )
    (comp (ref "R192")
      (value "R-US_R1206")
      (footprint "eagle-import:R1206")
      (libsource (lib "eagle-import") (part "rcl_334_R-US_R1206"))
    )
    (comp (ref "R193")
      (value "R-US_R1206")
      (footprint "eagle-import:R1206")
      (libsource (lib "eagle-import") (part "rcl_334_R-US_R1206"))
    )
    (comp (ref "R194")
      (value "R-US_R1206")
      (footprint "eagle-import:R1206")
      (libsource (lib "eagle-import") (part "rcl_334_R-US_R1206"))
    )
    (comp (ref "R195")
      (value "RESISTOR1206")
      (footprint "eagle-import:1206")
      (libsource (lib "eagle-import") (part "RESISTOR1206"))
    )
    (comp (ref "R196")
      (value "RESISTOR1206")
      (footprint "eagle-import:1206")
      (libsource (lib "eagle-import") (part "RESISTOR1206"))
    )
    (comp (ref "R197")
      (value "R-US_R1206")
      (footprint "eagle-import:R1206")
      (libsource (lib "eagle-import") (part "rcl_334_R-US_R1206"))
    )
    (comp (ref "R198")
      (value "R-US_R1206")
      (footprint "eagle-import:R1206")
      (libsource (lib "eagle-import") (part "rcl_334_R-US_R1206"))
    )
    (comp (ref "R199")
      (value "R-US_R1206")
      (footprint "eagle-import:R1206")
      (libsource (lib "eagle-import") (part "rcl_334_R-US_R1206"))
    )
    (comp (ref "R200")
      (value "R-US_R1206")
      (footprint "eagle-import:R1206")
      (libsource (lib "eagle-import") (part "rcl_334_R-US_R1206"))
    )
    (comp (ref "R201")
      (value "R-US_R1206")
      (footprint "eagle-import:R1206")
      (libsource (lib "eagle-import") (part "rcl_334_R-US_R1206"))
    )
    (comp (ref "R202")
      (value "R-US_R1206")
      (footprint "eagle-import:R1206")
      (libsource (lib "eagle-import") (part "rcl_334_R-US_R1206"))
    )
    (comp (ref "R203")
      (value "R-US_R1206")
      (footprint "eagle-import:R1206")
      (libsource (lib "eagle-import") (part "rcl_334_R-US_R1206"))
    )
    (comp (ref "R204")
      (value "R-US_R1206")
      (footprint "eagle-import:R1206")
      (libsource (lib "eagle-import") (part "rcl_334_R-US_R1206"))
    )
    (comp (ref "R205")
      (value "R-US_R1206")
      (footprint "eagle-import:R1206")
      (libsource (lib "eagle-import") (part "rcl_334_R-US_R1206"))
    )
    (comp (ref "R206")
      (value "R-US_R1206")
      (footprint "eagle-import:R1206")
      (libsource (lib "eagle-import") (part "rcl_334_R-US_R1206"))
    )
    (comp (ref "R207")
      (value "R-US_R1206")
      (footprint "eagle-import:R1206")
      (libsource (lib "eagle-import") (part "rcl_334_R-US_R1206"))
    )
    (comp (ref "R208")
      (value "R-US_R1206")
      (footprint "eagle-import:R1206")
      (libsource (lib "eagle-import") (part "rcl_334_R-US_R1206"))
    )
    (comp (ref "R209")
      (value "R-US_R1206")
      (footprint "eagle-import:R1206")
      (libsource (lib "eagle-import") (part "rcl_334_R-US_R1206"))
    )
    (comp (ref "R210")
      (value "R-US_R1206")
      (footprint "eagle-import:R1206")
      (libsource (lib "eagle-import") (part "rcl_334_R-US_R1206"))
    )
    (comp (ref "R211")
      (value "R-US_R1206")
      (footprint "eagle-import:R1206")
      (libsource (lib "eagle-import") (part "rcl_334_R-US_R1206"))
    )
    (comp (ref "R212")
      (value "R-US_R1206")
      (footprint "eagle-import:R1206")
      (libsource (lib "eagle-import") (part "rcl_334_R-US_R1206"))
    )
    (comp (ref "R213")
      (value "R-US_R1206")
      (footprint "eagle-import:R1206")
      (libsource (lib "eagle-import") (part "rcl_334_R-US_R1206"))
    )
    (comp (ref "R214")
      (value "R-US_R1206")
      (footprint "eagle-import:R1206")
      (libsource (lib "eagle-import") (part "rcl_334_R-US_R1206"))
    )
    (comp (ref "R215")
      (value "R-US_R1206")
      (footprint "eagle-import:R1206")
      (libsource (lib "eagle-import") (part "rcl_334_R-US_R1206"))
    )
    (comp (ref "R216")
      (value "R-US_R1206")
      (footprint "eagle-import:R1206")
      (libsource (lib "eagle-import") (part "rcl_334_R-US_R1206"))
    )
    (comp (ref "R217")
      (value "R-US_R1206")
      (footprint "eagle-import:R1206")
      (libsource (lib "eagle-import") (part "rcl_334_R-US_R1206"))
    )
    (comp (ref "R218")
      (value "R-US_R1206")
      (footprint "eagle-import:R1206")
      (libsource (lib "eagle-import") (part "rcl_334_R-US_R1206"))
    )
    (comp (ref "R219")
      (value "R-US_R1206")
      (footprint "eagle-import:R1206")
      (libsource (lib "eagle-import") (part "rcl_334_R-US_R1206"))
    )
    (comp (ref "R220")
      (value "R-US_R1206")
      (footprint "eagle-import:R1206")
      (libsource (lib "eagle-import") (part "rcl_334_R-US_R1206"))
    )
    (comp (ref "R221")
      (value "R-US_R1206")
      (footprint "eagle-import:R1206")
      (libsource (lib "eagle-import") (part "rcl_334_R-US_R1206"))
    )
    (comp (ref "R222")
      (value "R-US_R1206")
      (footprint "eagle-import:R1206")
      (libsource (lib "eagle-import") (part "rcl_334_R-US_R1206"))
    )
    (comp (ref "R223")
      (value "R-US_R1206")
      (footprint "eagle-import:R1206")
      (libsource (lib "eagle-import") (part "rcl_334_R-US_R1206"))
    )
    (comp (ref "R224")
      (value "R-US_R1206")
      (footprint "eagle-import:R1206")
      (libsource (lib "eagle-import") (part "rcl_334_R-US_R1206"))
    )
    (comp (ref "R225")
      (value "R-US_R1206")
      (footprint "eagle-import:R1206")
      (libsource (lib "eagle-import") (part "rcl_334_R-US_R1206"))
    )
    (comp (ref "R226")
      (value "R-US_R1206")
      (footprint "eagle-import:R1206")
      (libsource (lib "eagle-import") (part "rcl_334_R-US_R1206"))
    )
    (comp (ref "R227")
      (value "R-US_R1206")
      (footprint "eagle-import:R1206")
      (libsource (lib "eagle-import") (part "rcl_334_R-US_R1206"))
    )
    (comp (ref "R228")
      (value "R-US_R1206")
      (footprint "eagle-import:R1206")
      (libsource (lib "eagle-import") (part "rcl_334_R-US_R1206"))
    )
    (comp (ref "R229")
      (value "R-US_R1206")
      (footprint "eagle-import:R1206")
      (libsource (lib "eagle-import") (part "rcl_334_R-US_R1206"))
    )
    (comp (ref "R230")
      (value "R-US_R1206")
      (footprint "eagle-import:R1206")
      (libsource (lib "eagle-import") (part "rcl_334_R-US_R1206"))
    )
    (comp (ref "R231")
      (value "R-US_R1206")
      (footprint "eagle-import:R1206")
      (libsource (lib "eagle-import") (part "rcl_334_R-US_R1206"))
    )
    (comp (ref "R232")
      (value "R-US_R1206")
      (footprint "eagle-import:R1206")
      (libsource (lib "eagle-import") (part "rcl_334_R-US_R1206"))
    )
    (comp (ref "R233")
      (value "R-US_R1206")
      (footprint "eagle-import:R1206")
      (libsource (lib "eagle-import") (part "rcl_334_R-US_R1206"))
    )
    (comp (ref "R234")
      (value "R-US_R1206")
      (footprint "eagle-import:R1206")
      (libsource (lib "eagle-import") (part "rcl_334_R-US_R1206"))
    )
    (comp (ref "R235")
      (value "R-US_R1206")
      (footprint "eagle-import:R1206")
      (libsource (lib "eagle-import") (part "rcl_334_R-US_R1206"))
    )
    (comp (ref "R236")
      (value "R-US_R1206")
      (footprint "eagle-import:R1206")
      (libsource (lib "eagle-import") (part "rcl_334_R-US_R1206"))
    )
    (comp (ref "R237")
      (value "R-US_R1206")
      (footprint "eagle-import:R1206")
      (libsource (lib "eagle-import") (part "rcl_334_R-US_R1206"))
    )
    (comp (ref "R238")
      (value "R-US_R1206")
      (footprint "eagle-import:R1206")
      (libsource (lib "eagle-import") (part "rcl_334_R-US_R1206"))
    )
    (comp (ref "R239")
      (value "R-US_R1206")
      (footprint "eagle-import:R1206")
      (libsource (lib "eagle-import") (part "rcl_334_R-US_R1206"))
    )
    (comp (ref "R240")
      (value "R-US_R1206")
      (footprint "eagle-import:R1206")
      (libsource (lib "eagle-import") (part "rcl_334_R-US_R1206"))
    )
    (comp (ref "R241")
      (value "R-US_R1206")
      (footprint "eagle-import:R1206")
      (libsource (lib "eagle-import") (part "rcl_334_R-US_R1206"))
    )
    (comp (ref "R242")
      (value "R-US_R1206")
      (footprint "eagle-import:R1206")
      (libsource (lib "eagle-import") (part "rcl_334_R-US_R1206"))
    )
    (comp (ref "R243")
      (value "R-US_R1206")
      (footprint "eagle-import:R1206")
      (libsource (lib "eagle-import") (part "rcl_334_R-US_R1206"))
    )
    (comp (ref "R244")
      (value "R-US_R1206")
      (footprint "eagle-import:R1206")
      (libsource (lib "eagle-import") (part "rcl_334_R-US_R1206"))
    )
    (comp (ref "R245")
      (value "R-US_R1206")
      (footprint "eagle-import:R1206")
      (libsource (lib "eagle-import") (part "rcl_334_R-US_R1206"))
    )
    (comp (ref "R246")
      (value "R-US_R1206")
      (footprint "eagle-import:R1206")
      (libsource (lib "eagle-import") (part "rcl_334_R-US_R1206"))
    )
    (comp (ref "R247")
      (value "R-US_R1206")
      (footprint "eagle-import:R1206")
      (libsource (lib "eagle-import") (part "rcl_334_R-US_R1206"))
    )
    (comp (ref "R248")
      (value "R-US_R1206")
      (footprint "eagle-import:R1206")
      (libsource (lib "eagle-import") (part "rcl_334_R-US_R1206"))
    )
    (comp (ref "R249")
      (value "R-US_R1206")
      (footprint "eagle-import:R1206")
      (libsource (lib "eagle-import") (part "rcl_334_R-US_R1206"))
    )
    (comp (ref "R250")
      (value "R-US_R1206")
      (footprint "eagle-import:R1206")
      (libsource (lib "eagle-import") (part "rcl_334_R-US_R1206"))
    )
    (comp (ref "R251")
      (value "R-US_R1206")
      (footprint "eagle-import:R1206")
      (libsource (lib "eagle-import") (part "rcl_334_R-US_R1206"))
    )
    (comp (ref "R252")
      (value "R-US_R1206")
      (footprint "eagle-import:R1206")
      (libsource (lib "eagle-import") (part "rcl_334_R-US_R1206"))
    )
    (comp (ref "R253")
      (value "R-US_R1206")
      (footprint "eagle-import:R1206")
      (libsource (lib "eagle-import") (part "rcl_334_R-US_R1206"))
    )
    (comp (ref "R254")
      (value "R-US_R1206")
      (footprint "eagle-import:R1206")
      (libsource (lib "eagle-import") (part "rcl_334_R-US_R1206"))
    )
    (comp (ref "R255")
      (value "R-US_R1206")
      (footprint "eagle-import:R1206")
      (libsource (lib "eagle-import") (part "rcl_334_R-US_R1206"))
    )
    (comp (ref "S2")
      (value "TP-1138K9-BE1125")
      (footprint "eagle-import:FSMJSMA")
      (libsource (lib "eagle-import") (part "FSMJSMA"))
    )
    (comp (ref "SV2")
      (value "JTAG")
      (footprint "eagle-import:MA07-2")
      (libsource (lib "eagle-import") (part "MA07-2"))
    )
    (comp (ref "U1")
      (value "TMS320F28069_PN_80")
      (footprint "eagle-import:PN80")
      (libsource (lib "eagle-import") (part "TMS320F28069_PN_80"))
    )
    (comp (ref "U3")
      (value "TLV5610_DW_20")
      (footprint "eagle-import:DW20")
      (libsource (lib "eagle-import") (part "TLV5610_DW_20"))
    )
    (comp (ref "U4")
      (value "MAX395EWG")
      (footprint "eagle-import:21-0042B_24")
      (fields (field (name "MANUFACTURER_PART_NUMBER") "max395ewg"))
      (libsource (lib "eagle-import") (part "MAX395EWG"))
    )
    (comp (ref "U6")
      (value "MAX395EWG")
      (footprint "eagle-import:21-0042B_24")
      (fields (field (name "MANUFACTURER_PART_NUMBER") "max395ewg"))
      (libsource (lib "eagle-import") (part "MAX395EWG"))
    )
    (comp (ref "U7")
      (value "MAX395EWG")
      (footprint "eagle-import:21-0042B_24")
      (fields (field (name "MANUFACTURER_PART_NUMBER") "max395ewg"))
      (libsource (lib "eagle-import") (part "MAX395EWG"))
    )
    (comp (ref "Y1")
      (value "CRYSTALPTH-HC49UV")
      (footprint "eagle-import:HC49U")
      (libsource (lib "eagle-import") (part "CRYSTALPTH-HC49UV"))
    )
  )
  (nets
    (net (code "1") (name "+12V") (class "Default")
      (node (ref "C29") (pin "1") (pinfunction "1_1") (pintype "passive"))
      (node (ref "C30") (pin "1") (pinfunction "1_1") (pintype "passive"))
      (node (ref "IC14") (pin "4") (pinfunction "V+_4") (pintype "power_in"))
      (node (ref "IC15") (pin "4") (pinfunction "V+_4") (pintype "power_in"))
      (node (ref "IC16") (pin "4") (pinfunction "V+_4") (pintype "power_in"))
      (node (ref "IC17") (pin "4") (pinfunction "V+_4") (pintype "power_in"))
      (node (ref "IC18") (pin "4") (pinfunction "V+_4") (pintype "power_in"))
      (node (ref "IC19") (pin "4") (pinfunction "V+_4") (pintype "power_in"))
      (node (ref "IC20") (pin "4") (pinfunction "V+_4") (pintype "power_in"))
      (node (ref "IC21") (pin "4") (pinfunction "V+_4") (pintype "power_in"))
      (node (ref "IC22") (pin "4") (pinfunction "V+_4") (pintype "power_in"))
      (node (ref "IC23") (pin "4") (pinfunction "V+_4") (pintype "power_in"))
      (node (ref "IC24") (pin "4") (pinfunction "V+_4") (pintype "power_in"))
      (node (ref "IC25") (pin "4") (pinfunction "V+_4") (pintype "power_in"))
      (node (ref "IC26") (pin "4") (pinfunction "V+_4") (pintype "power_in"))
      (node (ref "IC27") (pin "4") (pinfunction "V+_4") (pintype "power_in"))
      (node (ref "IC28") (pin "4") (pinfunction "V+_4") (pintype "power_in"))
      (node (ref "IC29") (pin "4") (pinfunction "V+_4") (pintype "power_in"))
      (node (ref "IC3") (pin "4") (pinfunction "V+_4") (pintype "power_in"))
      (node (ref "IC30") (pin "4") (pinfunction "V+_4") (pintype "power_in"))
      (node (ref "IC5") (pin "4") (pinfunction "V+_4") (pintype "power_in"))
      (node (ref "IC6") (pin "3") (pinfunction "VO_3") (pintype "passive"))
      (node (ref "JP6") (pin "2") (pinfunction "2_2") (pintype "passive"))
      (node (ref "R15") (pin "2") (pinfunction "2_2") (pintype "passive"))
      (node (ref "U4") (pin "2") (pinfunction "V+_2") (pintype "power_in"))
      (node (ref "U4") (pin "23") (pinfunction "~{RESET}_23") (pintype "input"))
      (node (ref "U6") (pin "2") (pinfunction "V+_2") (pintype "power_in"))
      (node (ref "U6") (pin "23") (pinfunction "~{RESET}_23") (pintype "input"))
      (node (ref "U7") (pin "2") (pinfunction "V+_2") (pintype "power_in"))
      (node (ref "U7") (pin "23") (pinfunction "~{RESET}_23") (pintype "input"))
    )
    (net (code "2") (name "-12V") (class "Default")
      (node (ref "C27") (pin "2") (pinfunction "2_2") (pintype "passive"))
      (node (ref "C28") (pin "2") (pinfunction "2_2") (pintype "passive"))
      (node (ref "IC14") (pin "11") (pinfunction "V-_11") (pintype "power_in"))
      (node (ref "IC15") (pin "11") (pinfunction "V-_11") (pintype "power_in"))
      (node (ref "IC16") (pin "11") (pinfunction "V-_11") (pintype "power_in"))
      (node (ref "IC17") (pin "11") (pinfunction "V-_11") (pintype "power_in"))
      (node (ref "IC18") (pin "11") (pinfunction "V-_11") (pintype "power_in"))
      (node (ref "IC19") (pin "11") (pinfunction "V-_11") (pintype "power_in"))
      (node (ref "IC20") (pin "11") (pinfunction "V-_11") (pintype "power_in"))
      (node (ref "IC21") (pin "11") (pinfunction "V-_11") (pintype "power_in"))
      (node (ref "IC22") (pin "11") (pinfunction "V-_11") (pintype "power_in"))
      (node (ref "IC23") (pin "11") (pinfunction "V-_11") (pintype "power_in"))
      (node (ref "IC24") (pin "11") (pinfunction "V-_11") (pintype "power_in"))
      (node (ref "IC25") (pin "11") (pinfunction "V-_11") (pintype "power_in"))
      (node (ref "IC26") (pin "11") (pinfunction "V-_11") (pintype "power_in"))
      (node (ref "IC27") (pin "11") (pinfunction "V-_11") (pintype "power_in"))
      (node (ref "IC28") (pin "11") (pinfunction "V-_11") (pintype "power_in"))
      (node (ref "IC29") (pin "11") (pinfunction "V-_11") (pintype "power_in"))
      (node (ref "IC3") (pin "11") (pinfunction "V-_11") (pintype "power_in"))
      (node (ref "IC30") (pin "11") (pinfunction "V-_11") (pintype "power_in"))
      (node (ref "IC5") (pin "11") (pinfunction "V-_11") (pintype "power_in"))
      (node (ref "IC7") (pin "3") (pinfunction "VO_3") (pintype "passive"))
      (node (ref "R13") (pin "2") (pinfunction "2_2") (pintype "passive"))
    )
    (net (code "3") (name "/3V3OUT") (class "Default")
      (node (ref "C1") (pin "1") (pinfunction "1_1") (pintype "passive"))
      (node (ref "IC1") (pin "17") (pinfunction "3V3OUT_17") (pintype "output"))
      (node (ref "JP1") (pin "3") (pinfunction "3_3") (pintype "passive"))
    )
    (net (code "4") (name "/CBUS4") (class "Default")
      (node (ref "IC1") (pin "12") (pinfunction "CBUS4_12") (pintype "bidirectional"))
      (node (ref "JP2") (pin "3") (pinfunction "3_3") (pintype "passive"))
    )
    (net (code "5") (name "/DTR1") (class "Default")
      (node (ref "JP4") (pin "6") (pinfunction "6_6") (pintype "passive"))
    )
    (net (code "6") (name "/PWREN") (class "Default")
      (node (ref "IC1") (pin "14") (pinfunction "CBUS3_14") (pintype "bidirectional"))
    )
    (net (code "7") (name "/RTS") (class "Default")
      (node (ref "IC1") (pin "3") (pinfunction "~{RTS}_3") (pintype "output"))
      (node (ref "JP4") (pin "7") (pinfunction "7_7") (pintype "passive"))
    )
    (net (code "8") (name "/RTS1") (class "Default")
      (node (ref "JP4") (pin "8") (pinfunction "8_8") (pintype "passive"))
    )
    (net (code "9") (name "/RXD1") (class "Default")
      (node (ref "JP4") (pin "2") (pinfunction "2_2") (pintype "passive"))
    )
    (net (code "10") (name "/TXD1") (class "Default")
      (node (ref "JP4") (pin "4") (pinfunction "4_4") (pintype "passive"))
    )
    (net (code "11") (name "/USBDM") (class "Default")
      (node (ref "C43") (pin "2") (pinfunction "2_2") (pintype "passive"))
      (node (ref "IC1") (pin "16") (pinfunction "USBDM_16") (pintype "bidirectional"))
      (node (ref "R19") (pin "2") (pinfunction "2_2") (pintype "passive"))
    )
    (net (code "12") (name "/USBDP") (class "Default")
      (node (ref "C2") (pin "2") (pinfunction "2_2") (pintype "passive"))
      (node (ref "IC1") (pin "15") (pinfunction "USBDP_15") (pintype "bidirectional"))
      (node (ref "R20") (pin "2") (pinfunction "2_2") (pintype "passive"))
    )
    (net (code "13") (name "/VCC") (class "Default")
      (node (ref "JP1") (pin "1") (pinfunction "1_1") (pintype "passive"))
    )
    (net (code "14") (name "/VCCIO") (class "Default")
      (node (ref "IC1") (pin "4") (pinfunction "VCCIO_4") (pintype "power_in"))
      (node (ref "JP1") (pin "2") (pinfunction "2_2") (pintype "passive"))
      (node (ref "JP2") (pin "2") (pinfunction "2_2") (pintype "passive"))
      (node (ref "R2") (pin "2") (pinfunction "2_2") (pintype "passive"))
      (node (ref "R3") (pin "2") (pinfunction "2_2") (pintype "passive"))
    )
    (net (code "15") (name "/VDDIO") (class "Default")
      (node (ref "C14") (pin "1") (pinfunction "1_1") (pintype "passive"))
      (node (ref "C15") (pin "1") (pinfunction "1_1") (pintype "passive"))
      (node (ref "C16") (pin "1") (pinfunction "1_1") (pintype "passive"))
      (node (ref "C17") (pin "2") (pinfunction "2_2") (pintype "passive"))
      (node (ref "C18") (pin "2") (pinfunction "2_2") (pintype "passive"))
      (node (ref "C19") (pin "2") (pinfunction "2_2") (pintype "passive"))
      (node (ref "R12") (pin "1") (pinfunction "1_1") (pintype "passive"))
      (node (ref "R18") (pin "1") (pinfunction "1_1") (pintype "passive"))
      (node (ref "R195") (pin "1") (pinfunction "1_1") (pintype "passive"))
      (node (ref "SV2") (pin "5") (pinfunction "5_5") (pintype "passive"))
      (node (ref "U1") (pin "11") (pinfunction "VDDIO_3_11") (pintype "power_in"))
      (node (ref "U1") (pin "30") (pinfunction "VDDIO_4_30") (pintype "power_in"))
      (node (ref "U1") (pin "4") (pinfunction "VDDIO_2_4") (pintype "power_in"))
      (node (ref "U1") (pin "49") (pinfunction "VDDIO_5_49") (pintype "power_in"))
      (node (ref "U1") (pin "63") (pinfunction "VDDIO_6_63") (pintype "power_in"))
      (node (ref "U1") (pin "74") (pinfunction "VDDIO_74") (pintype "power_in"))
    )
    (net (code "16") (name "3V3") (class "Default")
      (node (ref "C23") (pin "2") (pinfunction "2_2") (pintype "passive"))
      (node (ref "C24") (pin "2") (pinfunction "2_2") (pintype "passive"))
      (node (ref "IC4") (pin "1") (pinfunction "FB/SENSE_1") (pintype "input"))
      (node (ref "IC4") (pin "2") (pinfunction "~{RESET}_2") (pintype "output"))
      (node (ref "IC4") (pin "7") (pinfunction "OUT_7") (pintype "output"))
      (node (ref "IC4") (pin "8") (pinfunction "OUT_8") (pintype "passive"))
      (node (ref "JP3") (pin "1") (pinfunction "1_1") (pintype "passive"))
      (node (ref "JP5") (pin "1") (pinfunction "1_1") (pintype "passive"))
      (node (ref "R104") (pin "1") (pinfunction "1_1") (pintype "passive"))
      (node (ref "R11") (pin "2") (pinfunction "2_2") (pintype "passive"))
      (node (ref "R110") (pin "1") (pinfunction "1_1") (pintype "passive"))
      (node (ref "R116") (pin "1") (pinfunction "1_1") (pintype "passive"))
      (node (ref "R122") (pin "1") (pinfunction "1_1") (pintype "passive"))
      (node (ref "R128") (pin "1") (pinfunction "1_1") (pintype "passive"))
      (node (ref "R134") (pin "1") (pinfunction "1_1") (pintype "passive"))
      (node (ref "R16") (pin "2") (pinfunction "2_2") (pintype "passive"))
      (node (ref "R195") (pin "2") (pinfunction "2_2") (pintype "passive"))
      (node (ref "R198") (pin "1") (pinfunction "1_1") (pintype "passive"))
      (node (ref "R207") (pin "1") (pinfunction "1_1") (pintype "passive"))
      (node (ref "R216") (pin "1") (pinfunction "1_1") (pintype "passive"))
      (node (ref "R22") (pin "2") (pinfunction "2_2") (pintype "passive"))
      (node (ref "R225") (pin "1") (pinfunction "1_1") (pintype "passive"))
      (node (ref "R23") (pin "2") (pinfunction "2_2") (pintype "passive"))
      (node (ref "R234") (pin "1") (pinfunction "1_1") (pintype "passive"))
      (node (ref "R243") (pin "1") (pinfunction "1_1") (pintype "passive"))
      (node (ref "R252") (pin "1") (pinfunction "1_1") (pintype "passive"))
      (node (ref "R31") (pin "1") (pinfunction "1_1") (pintype "passive"))
      (node (ref "R7") (pin "2") (pinfunction "2_2") (pintype "passive"))
      (node (ref "R9") (pin "2") (pinfunction "2_2") (pintype "passive"))
      (node (ref "R92") (pin "1") (pinfunction "1_1") (pintype "passive"))
      (node (ref "R98") (pin "1") (pinfunction "1_1") (pintype "passive"))
      (node (ref "U3") (pin "11") (pinfunction "AVDD_11") (pintype "power_in"))
      (node (ref "U3") (pin "16") (pinfunction "REF_16") (pintype "input"))
      (node (ref "U3") (pin "17") (pinfunction "MODE_17") (pintype "input"))
      (node (ref "U3") (pin "20") (pinfunction "DVDD_20") (pintype "power_in"))
      (node (ref "U3") (pin "5") (pinfunction "~{PRE}_5") (pintype "input"))
    )
    (net (code "17") (name "A1P") (class "Default")
      (node (ref "R144") (pin "2") (pinfunction "2_2") (pintype "passive"))
      (node (ref "U4") (pin "8") (pinfunction "COM1_8") (pintype "passive"))
    )
    (net (code "18") (name "A1Q") (class "Default")
      (node (ref "C37") (pin "2") (pinfunction "2_2") (pintype "passive"))
      (node (ref "IC23") (pin "2") (pinfunction "-IN_2") (pintype "input"))
      (node (ref "R141") (pin "1") (pinfunction "1_1") (pintype "passive"))
      (node (ref "R145") (pin "2") (pinfunction "2_2") (pintype "passive"))
      (node (ref "U4") (pin "7") (pinfunction "NO1_7") (pintype "passive"))
    )
    (net (code "19") (name "A3P") (class "Default")
      (node (ref "R155") (pin "2") (pinfunction "2_2") (pintype "passive"))
      (node (ref "U4") (pin "5") (pinfunction "NO0_5") (pintype "passive"))
    )
    (net (code "20") (name "A3Q") (class "Default")
      (node (ref "C38") (pin "2") (pinfunction "2_2") (pintype "passive"))
      (node (ref "IC23") (pin "6") (pinfunction "-IN_6") (pintype "input"))
      (node (ref "R140") (pin "1") (pinfunction "1_1") (pintype "passive"))
      (node (ref "R156") (pin "2") (pinfunction "2_2") (pintype "passive"))
      (node (ref "U4") (pin "6") (pinfunction "COM0_6") (pintype "passive"))
    )
    (net (code "21") (name "A5P") (class "Default")
      (node (ref "R151") (pin "2") (pinfunction "2_2") (pintype "passive"))
      (node (ref "U4") (pin "12") (pinfunction "COM3_12") (pintype "passive"))
    )
    (net (code "22") (name "A5Q") (class "Default")
      (node (ref "C36") (pin "2") (pinfunction "2_2") (pintype "passive"))
      (node (ref "IC23") (pin "9") (pinfunction "-IN_9") (pintype "input"))
      (node (ref "R139") (pin "1") (pinfunction "1_1") (pintype "passive"))
      (node (ref "R152") (pin "2") (pinfunction "2_2") (pintype "passive"))
      (node (ref "U4") (pin "11") (pinfunction "NO3_11") (pintype "passive"))
    )
    (net (code "23") (name "A7P") (class "Default")
      (node (ref "R153") (pin "2") (pinfunction "2_2") (pintype "passive"))
      (node (ref "U4") (pin "9") (pinfunction "NO2_9") (pintype "passive"))
    )
    (net (code "24") (name "A7Q") (class "Default")
      (node (ref "C35") (pin "2") (pinfunction "2_2") (pintype "passive"))
      (node (ref "IC23") (pin "13") (pinfunction "-IN_13") (pintype "input"))
      (node (ref "R142") (pin "1") (pinfunction "1_1") (pintype "passive"))
      (node (ref "R154") (pin "2") (pinfunction "2_2") (pintype "passive"))
      (node (ref "U4") (pin "10") (pinfunction "COM2_10") (pintype "passive"))
    )
    (net (code "25") (name "ADC_IN1") (class "Default")
      (node (ref "IC30") (pin "14") (pinfunction "OUT_14") (pintype "output"))
      (node (ref "JP25") (pin "4") (pinfunction "4_4") (pintype "passive"))
      (node (ref "R254") (pin "2") (pinfunction "2_2") (pintype "passive"))
    )
    (net (code "26") (name "ADC_IN2") (class "Default")
      (node (ref "IC28") (pin "14") (pinfunction "OUT_14") (pintype "output"))
      (node (ref "JP25") (pin "3") (pinfunction "3_3") (pintype "passive"))
      (node (ref "R236") (pin "2") (pinfunction "2_2") (pintype "passive"))
    )
    (net (code "27") (name "ADC_IN3") (class "Default")
      (node (ref "IC26") (pin "14") (pinfunction "OUT_14") (pintype "output"))
      (node (ref "JP25") (pin "2") (pinfunction "2_2") (pintype "passive"))
      (node (ref "R218") (pin "2") (pinfunction "2_2") (pintype "passive"))
    )
    (net (code "28") (name "ADC_IN4") (class "Default")
      (node (ref "IC25") (pin "14") (pinfunction "OUT_14") (pintype "output"))
      (node (ref "JP25") (pin "1") (pinfunction "1_1") (pintype "passive"))
      (node (ref "R209") (pin "2") (pinfunction "2_2") (pintype "passive"))
    )
    (net (code "29") (name "ADC_IN5") (class "Default")
      (node (ref "IC3") (pin "14") (pinfunction "OUT_14") (pintype "output"))
      (node (ref "JP24") (pin "1") (pinfunction "1_1") (pintype "passive"))
      (node (ref "R33") (pin "2") (pinfunction "2_2") (pintype "passive"))
    )
    (net (code "30") (name "ADC_IN6") (class "Default")
      (node (ref "IC5") (pin "14") (pinfunction "OUT_14") (pintype "output"))
      (node (ref "JP24") (pin "2") (pinfunction "2_2") (pintype "passive"))
      (node (ref "R200") (pin "2") (pinfunction "2_2") (pintype "passive"))
    )
    (net (code "31") (name "ADC_IN7") (class "Default")
      (node (ref "IC27") (pin "14") (pinfunction "OUT_14") (pintype "output"))
      (node (ref "JP24") (pin "3") (pinfunction "3_3") (pintype "passive"))
      (node (ref "R227") (pin "2") (pinfunction "2_2") (pintype "passive"))
    )
    (net (code "32") (name "ADC_IN8") (class "Default")
      (node (ref "IC29") (pin "14") (pinfunction "OUT_14") (pintype "output"))
      (node (ref "JP24") (pin "4") (pinfunction "4_4") (pintype "passive"))
      (node (ref "R245") (pin "2") (pinfunction "2_2") (pintype "passive"))
    )
    (net (code "33") (name "ADC_ORG1") (class "Default")
      (node (ref "JP18") (pin "6") (pinfunction "6_6") (pintype "passive"))
      (node (ref "U1") (pin "19") (pinfunction "ADCINA0_19") (pintype "passive"))
    )
    (net (code "34") (name "ADC_ORG2") (class "Default")
      (node (ref "JP18") (pin "8") (pinfunction "8_8") (pintype "passive"))
      (node (ref "U1") (pin "18") (pinfunction "ADCINA1_18") (pintype "input"))
    )
    (net (code "35") (name "ADC_ORG3") (class "Default")
      (node (ref "JP18") (pin "10") (pinfunction "10_10") (pintype "passive"))
      (node (ref "U1") (pin "17") (pinfunction "ADCINA2/COMP1A/AIO2_17") (pintype "bidirectional"))
    )
    (net (code "36") (name "ADC_ORG4") (class "Default")
      (node (ref "JP18") (pin "12") (pinfunction "12_12") (pintype "passive"))
      (node (ref "U1") (pin "16") (pinfunction "ADCINA4/COMP2A/AIO4_16") (pintype "bidirectional"))
    )
    (net (code "37") (name "ADC_ORG5") (class "Default")
      (node (ref "JP18") (pin "14") (pinfunction "14_14") (pintype "passive"))
      (node (ref "U1") (pin "15") (pinfunction "ADCINA5_15") (pintype "input"))
    )
    (net (code "38") (name "ADC_ORG6") (class "Default")
      (node (ref "JP18") (pin "16") (pinfunction "16_16") (pintype "passive"))
      (node (ref "U1") (pin "14") (pinfunction "ADCINA6/COMP3A/AIO6_14") (pintype "bidirectional"))
    )
    (net (code "39") (name "ADC_ORG7") (class "Default")
      (node (ref "JP18") (pin "4") (pinfunction "4_4") (pintype "passive"))
      (node (ref "U1") (pin "22") (pinfunction "ADCINB0_22") (pintype "input"))
    )
    (net (code "40") (name "ADC_ORG8") (class "Default")
      (node (ref "JP18") (pin "2") (pinfunction "2_2") (pintype "passive"))
      (node (ref "U1") (pin "23") (pinfunction "ADCINB1_23") (pintype "input"))
    )
    (net (code "41") (name "B1P") (class "Default")
      (node (ref "R161") (pin "2") (pinfunction "2_2") (pintype "passive"))
      (node (ref "U4") (pin "20") (pinfunction "NO7_20") (pintype "passive"))
    )
    (net (code "42") (name "B1Q") (class "Default")
      (node (ref "C41") (pin "2") (pinfunction "2_2") (pintype "passive"))
      (node (ref "IC24") (pin "2") (pinfunction "-IN_2") (pintype "input"))
      (node (ref "R159") (pin "1") (pinfunction "1_1") (pintype "passive"))
      (node (ref "R162") (pin "2") (pinfunction "2_2") (pintype "passive"))
      (node (ref "U4") (pin "19") (pinfunction "COM7_19") (pintype "passive"))
    )
    (net (code "43") (name "B3P") (class "Default")
      (node (ref "R167") (pin "2") (pinfunction "2_2") (pintype "passive"))
      (node (ref "U4") (pin "17") (pinfunction "COM6_17") (pintype "passive"))
    )
    (net (code "44") (name "B3Q") (class "Default")
      (node (ref "C42") (pin "2") (pinfunction "2_2") (pintype "passive"))
      (node (ref "IC24") (pin "6") (pinfunction "-IN_6") (pintype "input"))
      (node (ref "R158") (pin "1") (pinfunction "1_1") (pintype "passive"))
      (node (ref "R168") (pin "2") (pinfunction "2_2") (pintype "passive"))
      (node (ref "U4") (pin "18") (pinfunction "NO6_18") (pintype "passive"))
    )
    (net (code "45") (name "B5P") (class "Default")
      (node (ref "R163") (pin "2") (pinfunction "2_2") (pintype "passive"))
      (node (ref "U4") (pin "16") (pinfunction "NO5_16") (pintype "passive"))
    )
    (net (code "46") (name "B5Q") (class "Default")
      (node (ref "C40") (pin "2") (pinfunction "2_2") (pintype "passive"))
      (node (ref "IC24") (pin "9") (pinfunction "-IN_9") (pintype "input"))
      (node (ref "R157") (pin "1") (pinfunction "1_1") (pintype "passive"))
      (node (ref "R164") (pin "2") (pinfunction "2_2") (pintype "passive"))
      (node (ref "U4") (pin "15") (pinfunction "COM5_15") (pintype "passive"))
    )
    (net (code "47") (name "B7P") (class "Default")
      (node (ref "R165") (pin "2") (pinfunction "2_2") (pintype "passive"))
      (node (ref "U4") (pin "13") (pinfunction "COM4_13") (pintype "passive"))
    )
    (net (code "48") (name "B7Q") (class "Default")
      (node (ref "C39") (pin "2") (pinfunction "2_2") (pintype "passive"))
      (node (ref "IC24") (pin "13") (pinfunction "-IN_13") (pintype "input"))
      (node (ref "R160") (pin "1") (pinfunction "1_1") (pintype "passive"))
      (node (ref "R166") (pin "2") (pinfunction "2_2") (pintype "passive"))
      (node (ref "U4") (pin "14") (pinfunction "NO4_14") (pintype "passive"))
    )
    (net (code "49") (name "C1Q") (class "Default")
      (node (ref "R169") (pin "1") (pinfunction "1_1") (pintype "passive"))
      (node (ref "R170") (pin "1") (pinfunction "1_1") (pintype "passive"))
      (node (ref "U6") (pin "12") (pinfunction "COM3_12") (pintype "passive"))
      (node (ref "U6") (pin "5") (pinfunction "NO0_5") (pintype "passive"))
    )
    (net (code "50") (name "C3Q") (class "Default")
      (node (ref "R147") (pin "1") (pinfunction "1_1") (pintype "passive"))
      (node (ref "R148") (pin "1") (pinfunction "1_1") (pintype "passive"))
      (node (ref "U6") (pin "8") (pinfunction "COM1_8") (pintype "passive"))
      (node (ref "U6") (pin "9") (pinfunction "NO2_9") (pintype "passive"))
    )
    (net (code "51") (name "C5P") (class "Default")
      (node (ref "R169") (pin "2") (pinfunction "2_2") (pintype "passive"))
      (node (ref "U6") (pin "14") (pinfunction "NO4_14") (pintype "passive"))
    )
    (net (code "52") (name "C5Q") (class "Default")
      (node (ref "IC22") (pin "2") (pinfunction "-IN_2") (pintype "input"))
      (node (ref "JP12") (pin "10") (pinfunction "10_10") (pintype "passive"))
      (node (ref "JP12") (pin "9") (pinfunction "9_9") (pintype "passive"))
      (node (ref "R143") (pin "1") (pinfunction "1_1") (pintype "passive"))
      (node (ref "R176") (pin "2") (pinfunction "2_2") (pintype "passive"))
      (node (ref "U6") (pin "13") (pinfunction "COM4_13") (pintype "passive"))
      (node (ref "U6") (pin "15") (pinfunction "COM5_15") (pintype "passive"))
      (node (ref "U7") (pin "13") (pinfunction "COM4_13") (pintype "passive"))
      (node (ref "U7") (pin "15") (pinfunction "COM5_15") (pintype "passive"))
    )
    (net (code "53") (name "C6P") (class "Default")
      (node (ref "R170") (pin "2") (pinfunction "2_2") (pintype "passive"))
      (node (ref "U6") (pin "16") (pinfunction "NO5_16") (pintype "passive"))
    )
    (net (code "54") (name "C7P") (class "Default")
      (node (ref "R147") (pin "2") (pinfunction "2_2") (pintype "passive"))
      (node (ref "U6") (pin "18") (pinfunction "NO6_18") (pintype "passive"))
    )
    (net (code "55") (name "C7Q") (class "Default")
      (node (ref "IC22") (pin "6") (pinfunction "-IN_6") (pintype "input"))
      (node (ref "JP12") (pin "5") (pinfunction "5_5") (pintype "passive"))
      (node (ref "JP12") (pin "6") (pinfunction "6_6") (pintype "passive"))
      (node (ref "R146") (pin "1") (pinfunction "1_1") (pintype "passive"))
      (node (ref "R175") (pin "2") (pinfunction "2_2") (pintype "passive"))
      (node (ref "U6") (pin "17") (pinfunction "COM6_17") (pintype "passive"))
      (node (ref "U6") (pin "19") (pinfunction "COM7_19") (pintype "passive"))
      (node (ref "U7") (pin "17") (pinfunction "COM6_17") (pintype "passive"))
      (node (ref "U7") (pin "19") (pinfunction "COM7_19") (pintype "passive"))
    )
    (net (code "56") (name "C8P") (class "Default")
      (node (ref "R148") (pin "2") (pinfunction "2_2") (pintype "passive"))
      (node (ref "U6") (pin "20") (pinfunction "NO7_20") (pintype "passive"))
    )
    (net (code "57") (name "CHAN_A") (class "Default")
      (node (ref "JP16") (pin "1") (pinfunction "1_1") (pintype "passive"))
      (node (ref "JP9") (pin "1") (pinfunction "1_1") (pintype "passive"))
      (node (ref "U3") (pin "12") (pinfunction "OUTA_12") (pintype "output"))
    )
    (net (code "58") (name "CHAN_A1") (class "Default")
      (node (ref "JP16") (pin "2") (pinfunction "2_2") (pintype "passive"))
      (node (ref "R90") (pin "1") (pinfunction "1_1") (pintype "passive"))
    )
    (net (code "59") (name "CHAN_B") (class "Default")
      (node (ref "JP16") (pin "3") (pinfunction "3_3") (pintype "passive"))
      (node (ref "JP9") (pin "2") (pinfunction "2_2") (pintype "passive"))
      (node (ref "U3") (pin "13") (pinfunction "OUTB_13") (pintype "output"))
    )
    (net (code "60") (name "CHAN_B1") (class "Default")
      (node (ref "JP16") (pin "4") (pinfunction "4_4") (pintype "passive"))
      (node (ref "R96") (pin "1") (pinfunction "1_1") (pintype "passive"))
    )
    (net (code "61") (name "CHAN_C") (class "Default")
      (node (ref "JP16") (pin "5") (pinfunction "5_5") (pintype "passive"))
      (node (ref "JP9") (pin "3") (pinfunction "3_3") (pintype "passive"))
      (node (ref "U3") (pin "14") (pinfunction "OUTC_14") (pintype "output"))
    )
    (net (code "62") (name "CHAN_C1") (class "Default")
      (node (ref "JP16") (pin "6") (pinfunction "6_6") (pintype "passive"))
      (node (ref "R102") (pin "1") (pinfunction "1_1") (pintype "passive"))
    )
    (net (code "63") (name "CHAN_D") (class "Default")
      (node (ref "JP16") (pin "7") (pinfunction "7_7") (pintype "passive"))
      (node (ref "JP9") (pin "4") (pinfunction "4_4") (pintype "passive"))
      (node (ref "U3") (pin "15") (pinfunction "OUTD_15") (pintype "output"))
    )
    (net (code "64") (name "CHAN_D1") (class "Default")
      (node (ref "JP16") (pin "8") (pinfunction "8_8") (pintype "passive"))
      (node (ref "R108") (pin "1") (pinfunction "1_1") (pintype "passive"))
    )
    (net (code "65") (name "CHAN_E") (class "Default")
      (node (ref "JP16") (pin "9") (pinfunction "9_9") (pintype "passive"))
      (node (ref "JP9") (pin "5") (pinfunction "5_5") (pintype "passive"))
      (node (ref "U3") (pin "6") (pinfunction "OUTE_6") (pintype "output"))
    )
    (net (code "66") (name "CHAN_E1") (class "Default")
      (node (ref "JP16") (pin "10") (pinfunction "10_10") (pintype "passive"))
      (node (ref "R114") (pin "1") (pinfunction "1_1") (pintype "passive"))
    )
    (net (code "67") (name "CHAN_F") (class "Default")
      (node (ref "JP16") (pin "11") (pinfunction "11_11") (pintype "passive"))
      (node (ref "JP9") (pin "6") (pinfunction "6_6") (pintype "passive"))
      (node (ref "U3") (pin "7") (pinfunction "OUTF_7") (pintype "output"))
    )
    (net (code "68") (name "CHAN_F1") (class "Default")
      (node (ref "JP16") (pin "12") (pinfunction "12_12") (pintype "passive"))
      (node (ref "R120") (pin "1") (pinfunction "1_1") (pintype "passive"))
    )
    (net (code "69") (name "CHAN_G") (class "Default")
      (node (ref "JP16") (pin "13") (pinfunction "13_13") (pintype "passive"))
      (node (ref "JP9") (pin "7") (pinfunction "7_7") (pintype "passive"))
      (node (ref "U3") (pin "8") (pinfunction "OUTG_8") (pintype "output"))
    )
    (net (code "70") (name "CHAN_G1") (class "Default")
      (node (ref "JP16") (pin "14") (pinfunction "14_14") (pintype "passive"))
      (node (ref "R126") (pin "1") (pinfunction "1_1") (pintype "passive"))
    )
    (net (code "71") (name "CHAN_H") (class "Default")
      (node (ref "JP16") (pin "15") (pinfunction "15_15") (pintype "passive"))
      (node (ref "JP9") (pin "8") (pinfunction "8_8") (pintype "passive"))
      (node (ref "U3") (pin "9") (pinfunction "OUTH_9") (pintype "output"))
    )
    (net (code "72") (name "CHAN_H1") (class "Default")
      (node (ref "JP16") (pin "16") (pinfunction "16_16") (pintype "passive"))
      (node (ref "R132") (pin "1") (pinfunction "1_1") (pintype "passive"))
    )
    (net (code "73") (name "COMP2") (class "Default")
      (node (ref "JP7") (pin "2") (pinfunction "2_2") (pintype "passive"))
      (node (ref "R17") (pin "2") (pinfunction "2_2") (pintype "passive"))
      (node (ref "U1") (pin "55") (pinfunction "GPIO34/COMP2OUT/COMP3OUT_55") (pintype "bidirectional"))
    )
    (net (code "74") (name "CS_SW") (class "Default")
      (node (ref "U1") (pin "70") (pinfunction "GPIO15/ECAP2/SCIRXDB/~{SPISTEB}_70") (pintype "bidirectional"))
      (node (ref "U4") (pin "24") (pinfunction "~{CS}_24") (pintype "input"))
      (node (ref "U6") (pin "24") (pinfunction "~{CS}_24") (pintype "input"))
      (node (ref "U7") (pin "24") (pinfunction "~{CS}_24") (pintype "input"))
    )
    (net (code "75") (name "D1Q") (class "Default")
      (node (ref "R171") (pin "1") (pinfunction "1_1") (pintype "passive"))
      (node (ref "R172") (pin "1") (pinfunction "1_1") (pintype "passive"))
      (node (ref "U7") (pin "12") (pinfunction "COM3_12") (pintype "passive"))
      (node (ref "U7") (pin "5") (pinfunction "NO0_5") (pintype "passive"))
    )
    (net (code "76") (name "D3Q") (class "Default")
      (node (ref "R173") (pin "1") (pinfunction "1_1") (pintype "passive"))
      (node (ref "R174") (pin "1") (pinfunction "1_1") (pintype "passive"))
      (node (ref "U7") (pin "8") (pinfunction "COM1_8") (pintype "passive"))
      (node (ref "U7") (pin "9") (pinfunction "NO2_9") (pintype "passive"))
    )
    (net (code "77") (name "D5P") (class "Default")
      (node (ref "R171") (pin "2") (pinfunction "2_2") (pintype "passive"))
      (node (ref "U7") (pin "14") (pinfunction "NO4_14") (pintype "passive"))
    )
    (net (code "78") (name "D6P") (class "Default")
      (node (ref "R172") (pin "2") (pinfunction "2_2") (pintype "passive"))
      (node (ref "U7") (pin "16") (pinfunction "NO5_16") (pintype "passive"))
    )
    (net (code "79") (name "D7P") (class "Default")
      (node (ref "R173") (pin "2") (pinfunction "2_2") (pintype "passive"))
      (node (ref "U7") (pin "18") (pinfunction "NO6_18") (pintype "passive"))
    )
    (net (code "80") (name "D8P") (class "Default")
      (node (ref "R174") (pin "2") (pinfunction "2_2") (pintype "passive"))
      (node (ref "U7") (pin "20") (pinfunction "NO7_20") (pintype "passive"))
    )
    (net (code "81") (name "DGND") (class "Default")
      (node (ref "C1") (pin "2") (pinfunction "2_2") (pintype "passive"))
      (node (ref "C10") (pin "2") (pinfunction "2_2") (pintype "passive"))
      (node (ref "C11") (pin "1") (pinfunction "1_1") (pintype "passive"))
      (node (ref "C12") (pin "1") (pinfunction "1_1") (pintype "passive"))
      (node (ref "C13") (pin "1") (pinfunction "1_1") (pintype "passive"))
      (node (ref "C14") (pin "2") (pinfunction "2_2") (pintype "passive"))
      (node (ref "C15") (pin "2") (pinfunction "2_2") (pintype "passive"))
      (node (ref "C16") (pin "2") (pinfunction "2_2") (pintype "passive"))
      (node (ref "C17") (pin "1") (pinfunction "1_1") (pintype "passive"))
      (node (ref "C18") (pin "1") (pinfunction "1_1") (pintype "passive"))
      (node (ref "C19") (pin "1") (pinfunction "1_1") (pintype "passive"))
      (node (ref "C2") (pin "1") (pinfunction "1_1") (pintype "passive"))
      (node (ref "C20") (pin "2") (pinfunction "2_2") (pintype "passive"))
      (node (ref "C21") (pin "2") (pinfunction "2_2") (pintype "passive"))
      (node (ref "C22") (pin "1") (pinfunction "1_1") (pintype "passive"))
      (node (ref "C3") (pin "2") (pinfunction "2_2") (pintype "passive"))
      (node (ref "C4") (pin "2") (pinfunction "2_2") (pintype "passive"))
      (node (ref "C43") (pin "1") (pinfunction "1_1") (pintype "passive"))
      (node (ref "C5") (pin "2") (pinfunction "2_2") (pintype "passive"))
      (node (ref "C7") (pin "2") (pinfunction "2_2") (pintype "passive"))
      (node (ref "C8") (pin "2") (pinfunction "2_2") (pintype "passive"))
      (node (ref "C9") (pin "2") (pinfunction "2_2") (pintype "passive"))
      (node (ref "CON1") (pin "5") (pinfunction "5_5") (pintype "passive"))
      (node (ref "IC1") (pin "18") (pinfunction "GND_18") (pintype "power_in"))
      (node (ref "IC1") (pin "21") (pinfunction "GND_21") (pintype "power_in"))
      (node (ref "IC1") (pin "25") (pinfunction "GND_25") (pintype "power_in"))
      (node (ref "IC1") (pin "26") (pinfunction "TEST_26") (pintype "input"))
      (node (ref "IC1") (pin "7") (pinfunction "GND_7") (pintype "power_in"))
      (node (ref "JP4") (pin "11") (pinfunction "11_11") (pintype "passive"))
      (node (ref "Q1") (pin "C") (pinfunction "C_C") (pintype "passive"))
      (node (ref "R10") (pin "1") (pinfunction "1_1") (pintype "passive"))
      (node (ref "R17") (pin "1") (pinfunction "1_1") (pintype "passive"))
      (node (ref "R24") (pin "1") (pinfunction "1_1") (pintype "passive"))
      (node (ref "R8") (pin "1") (pinfunction "1_1") (pintype "passive"))
      (node (ref "S2") (pin "P$1") (pinfunction "0_P$1") (pintype "passive"))
      (node (ref "S2") (pin "P$2") (pinfunction "0_P$2") (pintype "passive"))
      (node (ref "SV2") (pin "10") (pinfunction "10_10") (pintype "passive"))
      (node (ref "SV2") (pin "12") (pinfunction "12_12") (pintype "passive"))
      (node (ref "SV2") (pin "4") (pinfunction "4_4") (pintype "passive"))
      (node (ref "SV2") (pin "8") (pinfunction "8_8") (pintype "passive"))
      (node (ref "U1") (pin "13") (pinfunction "VSS_3_13") (pintype "power_in"))
      (node (ref "U1") (pin "21") (pinfunction "VREFLO_21") (pintype "passive"))
      (node (ref "U1") (pin "28") (pinfunction "VSS_4_28") (pintype "power_in"))
      (node (ref "U1") (pin "3") (pinfunction "VSS_2_3") (pintype "power_in"))
      (node (ref "U1") (pin "38") (pinfunction "VSS_5_38") (pintype "power_in"))
      (node (ref "U1") (pin "50") (pinfunction "VSS_6_50") (pintype "power_in"))
      (node (ref "U1") (pin "64") (pinfunction "VSS_7_64") (pintype "power_in"))
      (node (ref "U1") (pin "71") (pinfunction "~{VREGENZ}_71") (pintype "input"))
      (node (ref "U1") (pin "73") (pinfunction "VSS_73") (pintype "power_in"))
      (node (ref "U3") (pin "1") (pinfunction "DGND_1") (pintype "power_in"))
      (node (ref "U3") (pin "10") (pinfunction "AGND_10") (pintype "power_in"))
      (node (ref "U3") (pin "18") (pinfunction "~{LDAC}_18") (pintype "input"))
    )
    (net (code "82") (name "DTR") (class "Default")
      (node (ref "IC1") (pin "2") (pinfunction "~{DTR}_2") (pintype "output"))
      (node (ref "JP4") (pin "5") (pinfunction "5_5") (pintype "passive"))
      (node (ref "R196") (pin "1") (pinfunction "1_1") (pintype "passive"))
    )
    (net (code "83") (name "FORCE1") (class "Default")
      (node (ref "JP9") (pin "12") (pinfunction "12_12") (pintype "passive"))
      (node (ref "U1") (pin "24") (pinfunction "ADCINB2/COMP1B/AIO10_24") (pintype "bidirectional"))
    )
    (net (code "84") (name "FORCE2") (class "Default")
      (node (ref "JP9") (pin "14") (pinfunction "14_14") (pintype "passive"))
      (node (ref "U1") (pin "25") (pinfunction "ADCINB4/COMP2B/AIO12_25") (pintype "bidirectional"))
    )
    (net (code "85") (name "FORCE3") (class "Default")
      (node (ref "JP9") (pin "11") (pinfunction "11_11") (pintype "passive"))
      (node (ref "U1") (pin "26") (pinfunction "ADCINB5_26") (pintype "input"))
    )
    (net (code "86") (name "FORCE4") (class "Default")
      (node (ref "JP9") (pin "13") (pinfunction "13_13") (pintype "passive"))
      (node (ref "U1") (pin "27") (pinfunction "ADCINB6/COMP3B/AIO14_27") (pintype "bidirectional"))
    )
    (net (code "87") (name "GND") (class "Default")
      (node (ref "C23") (pin "1") (pinfunction "1_1") (pintype "passive"))
      (node (ref "C24") (pin "1") (pinfunction "1_1") (pintype "passive"))
      (node (ref "C25") (pin "1") (pinfunction "1_1") (pintype "passive"))
      (node (ref "C26") (pin "1") (pinfunction "1_1") (pintype "passive"))
      (node (ref "C27") (pin "1") (pinfunction "1_1") (pintype "passive"))
      (node (ref "C28") (pin "1") (pinfunction "1_1") (pintype "passive"))
      (node (ref "C29") (pin "2") (pinfunction "2_2") (pintype "passive"))
      (node (ref "C30") (pin "2") (pinfunction "2_2") (pintype "passive"))
      (node (ref "C31") (pin "2") (pinfunction "2_2") (pintype "passive"))
      (node (ref "IC14") (pin "10") (pinfunction "+IN_10") (pintype "input"))
      (node (ref "IC14") (pin "3") (pinfunction "+IN_3") (pintype "input"))
      (node (ref "IC14") (pin "5") (pinfunction "+IN_5") (pintype "input"))
      (node (ref "IC15") (pin "10") (pinfunction "+IN_10") (pintype "input"))
      (node (ref "IC15") (pin "3") (pinfunction "+IN_3") (pintype "input"))
      (node (ref "IC15") (pin "5") (pinfunction "+IN_5") (pintype "input"))
      (node (ref "IC16") (pin "10") (pinfunction "+IN_10") (pintype "input"))
      (node (ref "IC16") (pin "3") (pinfunction "+IN_3") (pintype "input"))
      (node (ref "IC16") (pin "5") (pinfunction "+IN_5") (pintype "input"))
      (node (ref "IC17") (pin "10") (pinfunction "+IN_10") (pintype "input"))
      (node (ref "IC17") (pin "3") (pinfunction "+IN_3") (pintype "input"))
      (node (ref "IC17") (pin "5") (pinfunction "+IN_5") (pintype "input"))
      (node (ref "IC18") (pin "3") (pinfunction "+IN_3") (pintype "input"))
      (node (ref "IC18") (pin "5") (pinfunction "+IN_5") (pintype "input"))
      (node (ref "IC19") (pin "3") (pinfunction "+IN_3") (pintype "input"))
      (node (ref "IC19") (pin "5") (pinfunction "+IN_5") (pintype "input"))
      (node (ref "IC20") (pin "3") (pinfunction "+IN_3") (pintype "input"))
      (node (ref "IC20") (pin "5") (pinfunction "+IN_5") (pintype "input"))
      (node (ref "IC21") (pin "3") (pinfunction "+IN_3") (pintype "input"))
      (node (ref "IC21") (pin "5") (pinfunction "+IN_5") (pintype "input"))
      (node (ref "IC22") (pin "10") (pinfunction "+IN_10") (pintype "input"))
      (node (ref "IC22") (pin "12") (pinfunction "+IN_12") (pintype "input"))
      (node (ref "IC22") (pin "3") (pinfunction "+IN_3") (pintype "input"))
      (node (ref "IC22") (pin "5") (pinfunction "+IN_5") (pintype "input"))
      (node (ref "IC23") (pin "10") (pinfunction "+IN_10") (pintype "input"))
      (node (ref "IC23") (pin "12") (pinfunction "+IN_12") (pintype "input"))
      (node (ref "IC23") (pin "3") (pinfunction "+IN_3") (pintype "input"))
      (node (ref "IC23") (pin "5") (pinfunction "+IN_5") (pintype "input"))
      (node (ref "IC24") (pin "10") (pinfunction "+IN_10") (pintype "input"))
      (node (ref "IC24") (pin "12") (pinfunction "+IN_12") (pintype "input"))
      (node (ref "IC24") (pin "3") (pinfunction "+IN_3") (pintype "input"))
      (node (ref "IC24") (pin "5") (pinfunction "+IN_5") (pintype "input"))
      (node (ref "IC25") (pin "10") (pinfunction "+IN_10") (pintype "input"))
      (node (ref "IC25") (pin "12") (pinfunction "+IN_12") (pintype "input"))
      (node (ref "IC25") (pin "3") (pinfunction "+IN_3") (pintype "input"))
      (node (ref "IC25") (pin "5") (pinfunction "+IN_5") (pintype "input"))
      (node (ref "IC26") (pin "10") (pinfunction "+IN_10") (pintype "input"))
      (node (ref "IC26") (pin "12") (pinfunction "+IN_12") (pintype "input"))
      (node (ref "IC26") (pin "3") (pinfunction "+IN_3") (pintype "input"))
      (node (ref "IC26") (pin "5") (pinfunction "+IN_5") (pintype "input"))
      (node (ref "IC27") (pin "10") (pinfunction "+IN_10") (pintype "input"))
      (node (ref "IC27") (pin "12") (pinfunction "+IN_12") (pintype "input"))
      (node (ref "IC27") (pin "3") (pinfunction "+IN_3") (pintype "input"))
      (node (ref "IC27") (pin "5") (pinfunction "+IN_5") (pintype "input"))
      (node (ref "IC28") (pin "10") (pinfunction "+IN_10") (pintype "input"))
      (node (ref "IC28") (pin "12") (pinfunction "+IN_12") (pintype "input"))
      (node (ref "IC28") (pin "3") (pinfunction "+IN_3") (pintype "input"))
      (node (ref "IC28") (pin "5") (pinfunction "+IN_5") (pintype "input"))
      (node (ref "IC29") (pin "10") (pinfunction "+IN_10") (pintype "input"))
      (node (ref "IC29") (pin "12") (pinfunction "+IN_12") (pintype "input"))
      (node (ref "IC29") (pin "3") (pinfunction "+IN_3") (pintype "input"))
      (node (ref "IC29") (pin "5") (pinfunction "+IN_5") (pintype "input"))
      (node (ref "IC3") (pin "10") (pinfunction "+IN_10") (pintype "input"))
      (node (ref "IC3") (pin "12") (pinfunction "+IN_12") (pintype "input"))
      (node (ref "IC3") (pin "3") (pinfunction "+IN_3") (pintype "input"))
      (node (ref "IC3") (pin "5") (pinfunction "+IN_5") (pintype "input"))
      (node (ref "IC30") (pin "10") (pinfunction "+IN_10") (pintype "input"))
      (node (ref "IC30") (pin "12") (pinfunction "+IN_12") (pintype "input"))
      (node (ref "IC30") (pin "3") (pinfunction "+IN_3") (pintype "input"))
      (node (ref "IC30") (pin "5") (pinfunction "+IN_5") (pintype "input"))
      (node (ref "IC4") (pin "3") (pinfunction "~{EN}_3") (pintype "input"))
      (node (ref "IC4") (pin "4") (pinfunction "GND_4") (pintype "power_in"))
      (node (ref "IC5") (pin "10") (pinfunction "+IN_10") (pintype "input"))
      (node (ref "IC5") (pin "12") (pinfunction "+IN_12") (pintype "input"))
      (node (ref "IC5") (pin "3") (pinfunction "+IN_3") (pintype "input"))
      (node (ref "IC5") (pin "5") (pinfunction "+IN_5") (pintype "input"))
      (node (ref "IC6") (pin "2") (pinfunction "GND_2") (pintype "passive"))
      (node (ref "IC7") (pin "1") (pinfunction "GND_1") (pintype "passive"))
      (node (ref "JP13") (pin "2") (pinfunction "2_2") (pintype "passive"))
      (node (ref "JP17") (pin "2") (pinfunction "2_2") (pintype "passive"))
      (node (ref "JP3") (pin "2") (pinfunction "2_2") (pintype "passive"))
      (node (ref "JP5") (pin "2") (pinfunction "2_2") (pintype "passive"))
      (node (ref "JP9") (pin "10") (pinfunction "10_10") (pintype "passive"))
      (node (ref "JP9") (pin "9") (pinfunction "9_9") (pintype "passive"))
      (node (ref "LED4") (pin "K") (pinfunction "C_K") (pintype "passive"))
      (node (ref "LED5") (pin "A") (pinfunction "A_A") (pintype "passive"))
      (node (ref "LED6") (pin "K") (pinfunction "C_K") (pintype "passive"))
      (node (ref "R105") (pin "1") (pinfunction "1_1") (pintype "passive"))
      (node (ref "R111") (pin "1") (pinfunction "1_1") (pintype "passive"))
      (node (ref "R117") (pin "1") (pinfunction "1_1") (pintype "passive"))
      (node (ref "R123") (pin "1") (pinfunction "1_1") (pintype "passive"))
      (node (ref "R129") (pin "1") (pinfunction "1_1") (pintype "passive"))
      (node (ref "R135") (pin "1") (pinfunction "1_1") (pintype "passive"))
      (node (ref "R24") (pin "2") (pinfunction "2_2") (pintype "passive"))
      (node (ref "R93") (pin "1") (pinfunction "1_1") (pintype "passive"))
      (node (ref "R99") (pin "1") (pinfunction "1_1") (pintype "passive"))
      (node (ref "U4") (pin "21") (pinfunction "V-_21") (pintype "power_in"))
      (node (ref "U4") (pin "4") (pinfunction "GND_4") (pintype "power_in"))
      (node (ref "U6") (pin "21") (pinfunction "V-_21") (pintype "power_in"))
      (node (ref "U6") (pin "4") (pinfunction "GND_4") (pintype "power_in"))
      (node (ref "U7") (pin "21") (pinfunction "V-_21") (pintype "power_in"))
      (node (ref "U7") (pin "4") (pinfunction "GND_4") (pintype "power_in"))
    )
    (net (code "88") (name "INTEG_IN1") (class "Default")
      (node (ref "IC16") (pin "8") (pinfunction "OUT_8") (pintype "output"))
      (node (ref "JP19") (pin "4") (pinfunction "4_4") (pintype "passive"))
      (node (ref "R184") (pin "2") (pinfunction "2_2") (pintype "passive"))
    )
    (net (code "89") (name "INTEG_IN2") (class "Default")
      (node (ref "IC17") (pin "8") (pinfunction "OUT_8") (pintype "output"))
      (node (ref "JP19") (pin "3") (pinfunction "3_3") (pintype "passive"))
      (node (ref "R186") (pin "2") (pinfunction "2_2") (pintype "passive"))
    )
    (net (code "90") (name "INTEG_IN3") (class "Default")
      (node (ref "IC16") (pin "14") (pinfunction "OUT_14") (pintype "output"))
      (node (ref "JP19") (pin "2") (pinfunction "2_2") (pintype "passive"))
      (node (ref "R106") (pin "2") (pinfunction "2_2") (pintype "passive"))
    )
    (net (code "91") (name "INTEG_IN4") (class "Default")
      (node (ref "IC17") (pin "14") (pinfunction "OUT_14") (pintype "output"))
      (node (ref "JP19") (pin "1") (pinfunction "1_1") (pintype "passive"))
      (node (ref "R112") (pin "2") (pinfunction "2_2") (pintype "passive"))
    )
    (net (code "92") (name "INTEG_IN5") (class "Default")
      (node (ref "IC18") (pin "14") (pinfunction "OUT_14") (pintype "output"))
      (node (ref "JP20") (pin "4") (pinfunction "4_4") (pintype "passive"))
      (node (ref "R118") (pin "2") (pinfunction "2_2") (pintype "passive"))
    )
    (net (code "93") (name "INTEG_IN6") (class "Default")
      (node (ref "IC19") (pin "14") (pinfunction "OUT_14") (pintype "output"))
      (node (ref "JP20") (pin "3") (pinfunction "3_3") (pintype "passive"))
      (node (ref "R124") (pin "2") (pinfunction "2_2") (pintype "passive"))
    )
    (net (code "94") (name "INTEG_IN7") (class "Default")
      (node (ref "IC20") (pin "14") (pinfunction "OUT_14") (pintype "output"))
      (node (ref "JP20") (pin "2") (pinfunction "2_2") (pintype "passive"))
      (node (ref "R130") (pin "2") (pinfunction "2_2") (pintype "passive"))
    )
    (net (code "95") (name "INTEG_IN8") (class "Default")
      (node (ref "IC21") (pin "14") (pinfunction "OUT_14") (pintype "output"))
      (node (ref "JP20") (pin "1") (pinfunction "1_1") (pintype "passive"))
      (node (ref "R136") (pin "2") (pinfunction "2_2") (pintype "passive"))
    )
    (net (code "96") (name "INTEG_IN11") (class "Default")
      (node (ref "JP22") (pin "1") (pinfunction "1_1") (pintype "passive"))
      (node (ref "R144") (pin "1") (pinfunction "1_1") (pintype "passive"))
      (node (ref "R145") (pin "1") (pinfunction "1_1") (pintype "passive"))
    )
    (net (code "97") (name "INTEG_IN22") (class "Default")
      (node (ref "JP22") (pin "2") (pinfunction "2_2") (pintype "passive"))
      (node (ref "R155") (pin "1") (pinfunction "1_1") (pintype "passive"))
      (node (ref "R156") (pin "1") (pinfunction "1_1") (pintype "passive"))
    )
    (net (code "98") (name "INTEG_IN33") (class "Default")
      (node (ref "JP22") (pin "3") (pinfunction "3_3") (pintype "passive"))
      (node (ref "R151") (pin "1") (pinfunction "1_1") (pintype "passive"))
      (node (ref "R152") (pin "1") (pinfunction "1_1") (pintype "passive"))
    )
    (net (code "99") (name "INTEG_IN44") (class "Default")
      (node (ref "JP22") (pin "4") (pinfunction "4_4") (pintype "passive"))
      (node (ref "R153") (pin "1") (pinfunction "1_1") (pintype "passive"))
      (node (ref "R154") (pin "1") (pinfunction "1_1") (pintype "passive"))
    )
    (net (code "100") (name "INTEG_IN55") (class "Default")
      (node (ref "JP21") (pin "1") (pinfunction "1_1") (pintype "passive"))
      (node (ref "R161") (pin "1") (pinfunction "1_1") (pintype "passive"))
      (node (ref "R162") (pin "1") (pinfunction "1_1") (pintype "passive"))
    )
    (net (code "101") (name "INTEG_IN66") (class "Default")
      (node (ref "JP21") (pin "2") (pinfunction "2_2") (pintype "passive"))
      (node (ref "R167") (pin "1") (pinfunction "1_1") (pintype "passive"))
      (node (ref "R168") (pin "1") (pinfunction "1_1") (pintype "passive"))
    )
    (net (code "102") (name "INTEG_IN77") (class "Default")
      (node (ref "JP21") (pin "3") (pinfunction "3_3") (pintype "passive"))
      (node (ref "R163") (pin "1") (pinfunction "1_1") (pintype "passive"))
      (node (ref "R164") (pin "1") (pinfunction "1_1") (pintype "passive"))
    )
    (net (code "103") (name "INTEG_IN88") (class "Default")
      (node (ref "JP21") (pin "4") (pinfunction "4_4") (pintype "passive"))
      (node (ref "R165") (pin "1") (pinfunction "1_1") (pintype "passive"))
      (node (ref "R166") (pin "1") (pinfunction "1_1") (pintype "passive"))
    )
    (net (code "104") (name "JTAG_TRST") (class "Default")
      (node (ref "JP11") (pin "2") (pinfunction "2_2") (pintype "passive"))
      (node (ref "SV2") (pin "2") (pinfunction "2_2") (pintype "passive"))
    )
    (net (code "105") (name "LIN_OUT1") (class "Default")
      (node (ref "IC22") (pin "1") (pinfunction "OUT_1") (pintype "output"))
      (node (ref "JP12") (pin "13") (pinfunction "13_13") (pintype "passive"))
      (node (ref "R143") (pin "2") (pinfunction "2_2") (pintype "passive"))
    )
    (net (code "106") (name "LIN_OUT1_SW") (class "Default")
      (node (ref "JP12") (pin "14") (pinfunction "14_14") (pintype "passive"))
      (node (ref "R178") (pin "1") (pinfunction "1_1") (pintype "passive"))
    )
    (net (code "107") (name "LIN_OUT2") (class "Default")
      (node (ref "IC22") (pin "7") (pinfunction "OUT_7") (pintype "output"))
      (node (ref "JP12") (pin "1") (pinfunction "1_1") (pintype "passive"))
      (node (ref "R146") (pin "2") (pinfunction "2_2") (pintype "passive"))
    )
    (net (code "108") (name "LIN_OUT2_SW") (class "Default")
      (node (ref "JP12") (pin "2") (pinfunction "2_2") (pintype "passive"))
      (node (ref "R180") (pin "2") (pinfunction "2_2") (pintype "passive"))
    )
    (net (code "109") (name "Net-(C25-Pad2)") (class "Default")
      (node (ref "C25") (pin "2") (pinfunction "2_2") (pintype "passive"))
      (node (ref "IC4") (pin "5") (pinfunction "IN_5") (pintype "input"))
      (node (ref "IC4") (pin "6") (pinfunction "IN_6") (pintype "input"))
      (node (ref "JP8") (pin "1") (pinfunction "1_1") (pintype "passive"))
    )
    (net (code "110") (name "Net-(CON1-Pad2)") (class "Default")
      (node (ref "CON1") (pin "2") (pinfunction "2_2") (pintype "passive"))
      (node (ref "R19") (pin "1") (pinfunction "1_1") (pintype "passive"))
    )
    (net (code "111") (name "Net-(CON1-Pad3)") (class "Default")
      (node (ref "CON1") (pin "3") (pinfunction "3_3") (pintype "passive"))
      (node (ref "R20") (pin "1") (pinfunction "1_1") (pintype "passive"))
    )
    (net (code "112") (name "Net-(IC1-CBUS0)") (class "Default")
      (node (ref "IC1") (pin "23") (pinfunction "CBUS0_23") (pintype "bidirectional"))
      (node (ref "LED1") (pin "C") (pinfunction "C_C") (pintype "passive"))
    )
    (net (code "113") (name "Net-(IC1-CBUS1)") (class "Default")
      (node (ref "IC1") (pin "22") (pinfunction "CBUS1_22") (pintype "bidirectional"))
      (node (ref "LED2") (pin "C") (pinfunction "C_C") (pintype "passive"))
    )
    (net (code "114") (name "Net-(IC1-~{RESET})") (class "Default")
      (node (ref "IC1") (pin "19") (pinfunction "~{RESET}_19") (pintype "input"))
      (node (ref "R4") (pin "1") (pinfunction "1_1") (pintype "passive"))
    )
    (net (code "115") (name "Net-(IC3A--IN)") (class "Default")
      (node (ref "IC3") (pin "2") (pinfunction "-IN_2") (pintype "input"))
      (node (ref "R26") (pin "2") (pinfunction "2_2") (pintype "passive"))
      (node (ref "R27") (pin "1") (pinfunction "1_1") (pintype "passive"))
    )
    (net (code "116") (name "Net-(IC3A-OUT)") (class "Default")
      (node (ref "IC3") (pin "1") (pinfunction "OUT_1") (pintype "output"))
      (node (ref "R27") (pin "2") (pinfunction "2_2") (pintype "passive"))
      (node (ref "R28") (pin "1") (pinfunction "1_1") (pintype "passive"))
    )
    (net (code "117") (name "Net-(IC3B--IN)") (class "Default")
      (node (ref "IC3") (pin "6") (pinfunction "-IN_6") (pintype "input"))
      (node (ref "R28") (pin "2") (pinfunction "2_2") (pintype "passive"))
      (node (ref "R29") (pin "1") (pinfunction "1_1") (pintype "passive"))
    )
    (net (code "118") (name "Net-(IC3B-OUT)") (class "Default")
      (node (ref "IC3") (pin "7") (pinfunction "OUT_7") (pintype "output"))
      (node (ref "R29") (pin "2") (pinfunction "2_2") (pintype "passive"))
      (node (ref "R30") (pin "1") (pinfunction "1_1") (pintype "passive"))
    )
    (net (code "119") (name "Net-(IC3C--IN)") (class "Default")
      (node (ref "IC3") (pin "9") (pinfunction "-IN_9") (pintype "input"))
      (node (ref "R30") (pin "2") (pinfunction "2_2") (pintype "passive"))
      (node (ref "R31") (pin "2") (pinfunction "2_2") (pintype "passive"))
      (node (ref "R34") (pin "1") (pinfunction "1_1") (pintype "passive"))
    )
    (net (code "120") (name "Net-(IC3C-OUT)") (class "Default")
      (node (ref "IC3") (pin "8") (pinfunction "OUT_8") (pintype "output"))
      (node (ref "R32") (pin "1") (pinfunction "1_1") (pintype "passive"))
      (node (ref "R34") (pin "2") (pinfunction "2_2") (pintype "passive"))
    )
    (net (code "121") (name "Net-(IC3D--IN)") (class "Default")
      (node (ref "IC3") (pin "13") (pinfunction "-IN_13") (pintype "input"))
      (node (ref "R32") (pin "2") (pinfunction "2_2") (pintype "passive"))
      (node (ref "R33") (pin "1") (pinfunction "1_1") (pintype "passive"))
    )
    (net (code "122") (name "Net-(IC5A--IN)") (class "Default")
      (node (ref "IC5") (pin "2") (pinfunction "-IN_2") (pintype "input"))
      (node (ref "R1") (pin "2") (pinfunction "2_2") (pintype "passive"))
      (node (ref "R5") (pin "1") (pinfunction "1_1") (pintype "passive"))
    )
    (net (code "123") (name "Net-(IC5A-OUT)") (class "Default")
      (node (ref "IC5") (pin "1") (pinfunction "OUT_1") (pintype "output"))
      (node (ref "R5") (pin "2") (pinfunction "2_2") (pintype "passive"))
      (node (ref "R6") (pin "1") (pinfunction "1_1") (pintype "passive"))
    )
    (net (code "124") (name "Net-(IC5B--IN)") (class "Default")
      (node (ref "IC5") (pin "6") (pinfunction "-IN_6") (pintype "input"))
      (node (ref "R14") (pin "1") (pinfunction "1_1") (pintype "passive"))
      (node (ref "R6") (pin "2") (pinfunction "2_2") (pintype "passive"))
    )
    (net (code "125") (name "Net-(IC5B-OUT)") (class "Default")
      (node (ref "IC5") (pin "7") (pinfunction "OUT_7") (pintype "output"))
      (node (ref "R14") (pin "2") (pinfunction "2_2") (pintype "passive"))
      (node (ref "R197") (pin "1") (pinfunction "1_1") (pintype "passive"))
    )
    (net (code "126") (name "Net-(IC5C--IN)") (class "Default")
      (node (ref "IC5") (pin "9") (pinfunction "-IN_9") (pintype "input"))
      (node (ref "R197") (pin "2") (pinfunction "2_2") (pintype "passive"))
      (node (ref "R198") (pin "2") (pinfunction "2_2") (pintype "passive"))
      (node (ref "R201") (pin "1") (pinfunction "1_1") (pintype "passive"))
    )
    (net (code "127") (name "Net-(IC5C-OUT)") (class "Default")
      (node (ref "IC5") (pin "8") (pinfunction "OUT_8") (pintype "output"))
      (node (ref "R199") (pin "1") (pinfunction "1_1") (pintype "passive"))
      (node (ref "R201") (pin "2") (pinfunction "2_2") (pintype "passive"))
    )
    (net (code "128") (name "Net-(IC5D--IN)") (class "Default")
      (node (ref "IC5") (pin "13") (pinfunction "-IN_13") (pintype "input"))
      (node (ref "R199") (pin "2") (pinfunction "2_2") (pintype "passive"))
      (node (ref "R200") (pin "1") (pinfunction "1_1") (pintype "passive"))
    )
    (net (code "129") (name "Net-(IC6-VI)") (class "Default")
      (node (ref "C31") (pin "1") (pinfunction "1_1") (pintype "passive"))
      (node (ref "D1") (pin "C") (pinfunction "C_C") (pintype "passive"))
      (node (ref "IC6") (pin "1") (pinfunction "VI_1") (pintype "input"))
    )
    (net (code "130") (name "Net-(IC7-VI)") (class "Default")
      (node (ref "C26") (pin "2") (pinfunction "2_2") (pintype "passive"))
      (node (ref "D3") (pin "A") (pinfunction "A_A") (pintype "passive"))
      (node (ref "IC7") (pin "2") (pinfunction "VI_2") (pintype "input"))
    )
    (net (code "131") (name "Net-(IC14A--IN)") (class "Default")
      (node (ref "IC14") (pin "2") (pinfunction "-IN_2") (pintype "input"))
      (node (ref "R89") (pin "1") (pinfunction "1_1") (pintype "passive"))
      (node (ref "R90") (pin "2") (pinfunction "2_2") (pintype "passive"))
    )
    (net (code "132") (name "Net-(IC14A-OUT)") (class "Default")
      (node (ref "IC14") (pin "1") (pinfunction "OUT_1") (pintype "output"))
      (node (ref "R89") (pin "2") (pinfunction "2_2") (pintype "passive"))
      (node (ref "R91") (pin "1") (pinfunction "1_1") (pintype "passive"))
    )
    (net (code "133") (name "Net-(IC14B--IN)") (class "Default")
      (node (ref "IC14") (pin "6") (pinfunction "-IN_6") (pintype "input"))
      (node (ref "R187") (pin "1") (pinfunction "1_1") (pintype "passive"))
      (node (ref "R91") (pin "2") (pinfunction "2_2") (pintype "passive"))
      (node (ref "R92") (pin "2") (pinfunction "2_2") (pintype "passive"))
    )
    (net (code "134") (name "Net-(IC14B-OUT)") (class "Default")
      (node (ref "IC14") (pin "12") (pinfunction "+IN_12") (pintype "input"))
      (node (ref "IC14") (pin "7") (pinfunction "OUT_7") (pintype "output"))
      (node (ref "R187") (pin "2") (pinfunction "2_2") (pintype "passive"))
    )
    (net (code "135") (name "Net-(IC14C--IN)") (class "Default")
      (node (ref "IC14") (pin "9") (pinfunction "-IN_9") (pintype "input"))
      (node (ref "R177") (pin "2") (pinfunction "2_2") (pintype "passive"))
      (node (ref "R178") (pin "2") (pinfunction "2_2") (pintype "passive"))
      (node (ref "R181") (pin "1") (pinfunction "1_1") (pintype "passive"))
    )
    (net (code "136") (name "Net-(IC14C-OUT)") (class "Default")
      (node (ref "IC14") (pin "8") (pinfunction "OUT_8") (pintype "output"))
      (node (ref "R181") (pin "2") (pinfunction "2_2") (pintype "passive"))
      (node (ref "R183") (pin "1") (pinfunction "1_1") (pintype "passive"))
    )
    (net (code "137") (name "Net-(IC14D--IN)") (class "Default")
      (node (ref "IC14") (pin "13") (pinfunction "-IN_13") (pintype "input"))
      (node (ref "R93") (pin "2") (pinfunction "2_2") (pintype "passive"))
      (node (ref "R94") (pin "1") (pinfunction "1_1") (pintype "passive"))
    )
    (net (code "138") (name "Net-(IC14D-OUT)") (class "Default")
      (node (ref "IC14") (pin "14") (pinfunction "OUT_14") (pintype "output"))
      (node (ref "R177") (pin "1") (pinfunction "1_1") (pintype "passive"))
      (node (ref "R94") (pin "2") (pinfunction "2_2") (pintype "passive"))
    )
    (net (code "139") (name "Net-(IC15A--IN)") (class "Default")
      (node (ref "IC15") (pin "2") (pinfunction "-IN_2") (pintype "input"))
      (node (ref "R95") (pin "1") (pinfunction "1_1") (pintype "passive"))
      (node (ref "R96") (pin "2") (pinfunction "2_2") (pintype "passive"))
    )
    (net (code "140") (name "Net-(IC15A-OUT)") (class "Default")
      (node (ref "IC15") (pin "1") (pinfunction "OUT_1") (pintype "output"))
      (node (ref "R95") (pin "2") (pinfunction "2_2") (pintype "passive"))
      (node (ref "R97") (pin "1") (pinfunction "1_1") (pintype "passive"))
    )
    (net (code "141") (name "Net-(IC15B--IN)") (class "Default")
      (node (ref "IC15") (pin "6") (pinfunction "-IN_6") (pintype "input"))
      (node (ref "R189") (pin "1") (pinfunction "1_1") (pintype "passive"))
      (node (ref "R97") (pin "2") (pinfunction "2_2") (pintype "passive"))
      (node (ref "R98") (pin "2") (pinfunction "2_2") (pintype "passive"))
    )
    (net (code "142") (name "Net-(IC15B-OUT)") (class "Default")
      (node (ref "IC15") (pin "12") (pinfunction "+IN_12") (pintype "input"))
      (node (ref "IC15") (pin "7") (pinfunction "OUT_7") (pintype "output"))
      (node (ref "R189") (pin "2") (pinfunction "2_2") (pintype "passive"))
    )
    (net (code "143") (name "Net-(IC15C--IN)") (class "Default")
      (node (ref "IC15") (pin "9") (pinfunction "-IN_9") (pintype "input"))
      (node (ref "R179") (pin "1") (pinfunction "1_1") (pintype "passive"))
      (node (ref "R180") (pin "1") (pinfunction "1_1") (pintype "passive"))
      (node (ref "R182") (pin "1") (pinfunction "1_1") (pintype "passive"))
    )
    (net (code "144") (name "Net-(IC15C-OUT)") (class "Default")
      (node (ref "IC15") (pin "8") (pinfunction "OUT_8") (pintype "output"))
      (node (ref "R182") (pin "2") (pinfunction "2_2") (pintype "passive"))
      (node (ref "R185") (pin "1") (pinfunction "1_1") (pintype "passive"))
    )
    (net (code "145") (name "Net-(IC15D--IN)") (class "Default")
      (node (ref "IC15") (pin "13") (pinfunction "-IN_13") (pintype "input"))
      (node (ref "R100") (pin "1") (pinfunction "1_1") (pintype "passive"))
      (node (ref "R99") (pin "2") (pinfunction "2_2") (pintype "passive"))
    )
    (net (code "146") (name "Net-(IC15D-OUT)") (class "Default")
      (node (ref "IC15") (pin "14") (pinfunction "OUT_14") (pintype "output"))
      (node (ref "R100") (pin "2") (pinfunction "2_2") (pintype "passive"))
      (node (ref "R179") (pin "2") (pinfunction "2_2") (pintype "passive"))
    )
    (net (code "147") (name "Net-(IC16A--IN)") (class "Default")
      (node (ref "IC16") (pin "2") (pinfunction "-IN_2") (pintype "input"))
      (node (ref "R101") (pin "1") (pinfunction "1_1") (pintype "passive"))
      (node (ref "R102") (pin "2") (pinfunction "2_2") (pintype "passive"))
    )
    (net (code "148") (name "Net-(IC16A-OUT)") (class "Default")
      (node (ref "IC16") (pin "1") (pinfunction "OUT_1") (pintype "output"))
      (node (ref "R101") (pin "2") (pinfunction "2_2") (pintype "passive"))
      (node (ref "R103") (pin "1") (pinfunction "1_1") (pintype "passive"))
    )
    (net (code "149") (name "Net-(IC16B--IN)") (class "Default")
      (node (ref "IC16") (pin "6") (pinfunction "-IN_6") (pintype "input"))
      (node (ref "R103") (pin "2") (pinfunction "2_2") (pintype "passive"))
      (node (ref "R104") (pin "2") (pinfunction "2_2") (pintype "passive"))
      (node (ref "R188") (pin "1") (pinfunction "1_1") (pintype "passive"))
    )
    (net (code "150") (name "Net-(IC16B-OUT)") (class "Default")
      (node (ref "IC16") (pin "12") (pinfunction "+IN_12") (pintype "input"))
      (node (ref "IC16") (pin "7") (pinfunction "OUT_7") (pintype "output"))
      (node (ref "R188") (pin "2") (pinfunction "2_2") (pintype "passive"))
    )
    (net (code "151") (name "Net-(IC16C--IN)") (class "Default")
      (node (ref "IC16") (pin "9") (pinfunction "-IN_9") (pintype "input"))
      (node (ref "R183") (pin "2") (pinfunction "2_2") (pintype "passive"))
      (node (ref "R184") (pin "1") (pinfunction "1_1") (pintype "passive"))
    )
    (net (code "152") (name "Net-(IC16D--IN)") (class "Default")
      (node (ref "IC16") (pin "13") (pinfunction "-IN_13") (pintype "input"))
      (node (ref "R105") (pin "2") (pinfunction "2_2") (pintype "passive"))
      (node (ref "R106") (pin "1") (pinfunction "1_1") (pintype "passive"))
    )
    (net (code "153") (name "Net-(IC17A--IN)") (class "Default")
      (node (ref "IC17") (pin "2") (pinfunction "-IN_2") (pintype "input"))
      (node (ref "R107") (pin "1") (pinfunction "1_1") (pintype "passive"))
      (node (ref "R108") (pin "2") (pinfunction "2_2") (pintype "passive"))
    )
    (net (code "154") (name "Net-(IC17A-OUT)") (class "Default")
      (node (ref "IC17") (pin "1") (pinfunction "OUT_1") (pintype "output"))
      (node (ref "R107") (pin "2") (pinfunction "2_2") (pintype "passive"))
      (node (ref "R109") (pin "1") (pinfunction "1_1") (pintype "passive"))
    )
    (net (code "155") (name "Net-(IC17B--IN)") (class "Default")
      (node (ref "IC17") (pin "6") (pinfunction "-IN_6") (pintype "input"))
      (node (ref "R109") (pin "2") (pinfunction "2_2") (pintype "passive"))
      (node (ref "R110") (pin "2") (pinfunction "2_2") (pintype "passive"))
      (node (ref "R190") (pin "1") (pinfunction "1_1") (pintype "passive"))
    )
    (net (code "156") (name "Net-(IC17B-OUT)") (class "Default")
      (node (ref "IC17") (pin "12") (pinfunction "+IN_12") (pintype "input"))
      (node (ref "IC17") (pin "7") (pinfunction "OUT_7") (pintype "output"))
      (node (ref "R190") (pin "2") (pinfunction "2_2") (pintype "passive"))
    )
    (net (code "157") (name "Net-(IC17C--IN)") (class "Default")
      (node (ref "IC17") (pin "9") (pinfunction "-IN_9") (pintype "input"))
      (node (ref "R185") (pin "2") (pinfunction "2_2") (pintype "passive"))
      (node (ref "R186") (pin "1") (pinfunction "1_1") (pintype "passive"))
    )
    (net (code "158") (name "Net-(IC17D--IN)") (class "Default")
      (node (ref "IC17") (pin "13") (pinfunction "-IN_13") (pintype "input"))
      (node (ref "R111") (pin "2") (pinfunction "2_2") (pintype "passive"))
      (node (ref "R112") (pin "1") (pinfunction "1_1") (pintype "passive"))
    )
    (net (code "159") (name "Net-(IC18A--IN)") (class "Default")
      (node (ref "IC18") (pin "2") (pinfunction "-IN_2") (pintype "input"))
      (node (ref "R113") (pin "1") (pinfunction "1_1") (pintype "passive"))
      (node (ref "R114") (pin "2") (pinfunction "2_2") (pintype "passive"))
    )
    (net (code "160") (name "Net-(IC18A-OUT)") (class "Default")
      (node (ref "IC18") (pin "1") (pinfunction "OUT_1") (pintype "output"))
      (node (ref "R113") (pin "2") (pinfunction "2_2") (pintype "passive"))
      (node (ref "R115") (pin "1") (pinfunction "1_1") (pintype "passive"))
    )
    (net (code "161") (name "Net-(IC18B--IN)") (class "Default")
      (node (ref "IC18") (pin "6") (pinfunction "-IN_6") (pintype "input"))
      (node (ref "R115") (pin "2") (pinfunction "2_2") (pintype "passive"))
      (node (ref "R116") (pin "2") (pinfunction "2_2") (pintype "passive"))
      (node (ref "R192") (pin "1") (pinfunction "1_1") (pintype "passive"))
    )
    (net (code "162") (name "Net-(IC18B-OUT)") (class "Default")
      (node (ref "IC18") (pin "12") (pinfunction "+IN_12") (pintype "input"))
      (node (ref "IC18") (pin "7") (pinfunction "OUT_7") (pintype "output"))
      (node (ref "R192") (pin "2") (pinfunction "2_2") (pintype "passive"))
    )
    (net (code "163") (name "Net-(IC18D--IN)") (class "Default")
      (node (ref "IC18") (pin "13") (pinfunction "-IN_13") (pintype "input"))
      (node (ref "R117") (pin "2") (pinfunction "2_2") (pintype "passive"))
      (node (ref "R118") (pin "1") (pinfunction "1_1") (pintype "passive"))
    )
    (net (code "164") (name "Net-(IC19A--IN)") (class "Default")
      (node (ref "IC19") (pin "2") (pinfunction "-IN_2") (pintype "input"))
      (node (ref "R119") (pin "1") (pinfunction "1_1") (pintype "passive"))
      (node (ref "R120") (pin "2") (pinfunction "2_2") (pintype "passive"))
    )
    (net (code "165") (name "Net-(IC19A-OUT)") (class "Default")
      (node (ref "IC19") (pin "1") (pinfunction "OUT_1") (pintype "output"))
      (node (ref "R119") (pin "2") (pinfunction "2_2") (pintype "passive"))
      (node (ref "R121") (pin "1") (pinfunction "1_1") (pintype "passive"))
    )
    (net (code "166") (name "Net-(IC19B--IN)") (class "Default")
      (node (ref "IC19") (pin "6") (pinfunction "-IN_6") (pintype "input"))
      (node (ref "R121") (pin "2") (pinfunction "2_2") (pintype "passive"))
      (node (ref "R122") (pin "2") (pinfunction "2_2") (pintype "passive"))
      (node (ref "R191") (pin "1") (pinfunction "1_1") (pintype "passive"))
    )
    (net (code "167") (name "Net-(IC19B-OUT)") (class "Default")
      (node (ref "IC19") (pin "12") (pinfunction "+IN_12") (pintype "input"))
      (node (ref "IC19") (pin "7") (pinfunction "OUT_7") (pintype "output"))
      (node (ref "R191") (pin "2") (pinfunction "2_2") (pintype "passive"))
    )
    (net (code "168") (name "Net-(IC19D--IN)") (class "Default")
      (node (ref "IC19") (pin "13") (pinfunction "-IN_13") (pintype "input"))
      (node (ref "R123") (pin "2") (pinfunction "2_2") (pintype "passive"))
      (node (ref "R124") (pin "1") (pinfunction "1_1") (pintype "passive"))
    )
    (net (code "169") (name "Net-(IC20A--IN)") (class "Default")
      (node (ref "IC20") (pin "2") (pinfunction "-IN_2") (pintype "input"))
      (node (ref "R125") (pin "1") (pinfunction "1_1") (pintype "passive"))
      (node (ref "R126") (pin "2") (pinfunction "2_2") (pintype "passive"))
    )
    (net (code "170") (name "Net-(IC20A-OUT)") (class "Default")
      (node (ref "IC20") (pin "1") (pinfunction "OUT_1") (pintype "output"))
      (node (ref "R125") (pin "2") (pinfunction "2_2") (pintype "passive"))
      (node (ref "R127") (pin "1") (pinfunction "1_1") (pintype "passive"))
    )
    (net (code "171") (name "Net-(IC20B--IN)") (class "Default")
      (node (ref "IC20") (pin "6") (pinfunction "-IN_6") (pintype "input"))
      (node (ref "R127") (pin "2") (pinfunction "2_2") (pintype "passive"))
      (node (ref "R128") (pin "2") (pinfunction "2_2") (pintype "passive"))
      (node (ref "R193") (pin "1") (pinfunction "1_1") (pintype "passive"))
    )
    (net (code "172") (name "Net-(IC20B-OUT)") (class "Default")
      (node (ref "IC20") (pin "12") (pinfunction "+IN_12") (pintype "input"))
      (node (ref "IC20") (pin "7") (pinfunction "OUT_7") (pintype "output"))
      (node (ref "R193") (pin "2") (pinfunction "2_2") (pintype "passive"))
    )
    (net (code "173") (name "Net-(IC20D--IN)") (class "Default")
      (node (ref "IC20") (pin "13") (pinfunction "-IN_13") (pintype "input"))
      (node (ref "R129") (pin "2") (pinfunction "2_2") (pintype "passive"))
      (node (ref "R130") (pin "1") (pinfunction "1_1") (pintype "passive"))
    )
    (net (code "174") (name "Net-(IC21A--IN)") (class "Default")
      (node (ref "IC21") (pin "2") (pinfunction "-IN_2") (pintype "input"))
      (node (ref "R131") (pin "1") (pinfunction "1_1") (pintype "passive"))
      (node (ref "R132") (pin "2") (pinfunction "2_2") (pintype "passive"))
    )
    (net (code "175") (name "Net-(IC21A-OUT)") (class "Default")
      (node (ref "IC21") (pin "1") (pinfunction "OUT_1") (pintype "output"))
      (node (ref "R131") (pin "2") (pinfunction "2_2") (pintype "passive"))
      (node (ref "R133") (pin "1") (pinfunction "1_1") (pintype "passive"))
    )
    (net (code "176") (name "Net-(IC21B--IN)") (class "Default")
      (node (ref "IC21") (pin "6") (pinfunction "-IN_6") (pintype "input"))
      (node (ref "R133") (pin "2") (pinfunction "2_2") (pintype "passive"))
      (node (ref "R134") (pin "2") (pinfunction "2_2") (pintype "passive"))
      (node (ref "R194") (pin "1") (pinfunction "1_1") (pintype "passive"))
    )
    (net (code "177") (name "Net-(IC21B-OUT)") (class "Default")
      (node (ref "IC21") (pin "12") (pinfunction "+IN_12") (pintype "input"))
      (node (ref "IC21") (pin "7") (pinfunction "OUT_7") (pintype "output"))
      (node (ref "R194") (pin "2") (pinfunction "2_2") (pintype "passive"))
    )
    (net (code "178") (name "Net-(IC21D--IN)") (class "Default")
      (node (ref "IC21") (pin "13") (pinfunction "-IN_13") (pintype "input"))
      (node (ref "R135") (pin "2") (pinfunction "2_2") (pintype "passive"))
      (node (ref "R136") (pin "1") (pinfunction "1_1") (pintype "passive"))
    )
    (net (code "179") (name "Net-(IC22C--IN)") (class "Default")
      (node (ref "IC22") (pin "9") (pinfunction "-IN_9") (pintype "input"))
      (node (ref "R137") (pin "2") (pinfunction "2_2") (pintype "passive"))
      (node (ref "R138") (pin "1") (pinfunction "1_1") (pintype "passive"))
    )
    (net (code "180") (name "Net-(IC22D--IN)") (class "Default")
      (node (ref "IC22") (pin "13") (pinfunction "-IN_13") (pintype "input"))
      (node (ref "R149") (pin "2") (pinfunction "2_2") (pintype "passive"))
      (node (ref "R150") (pin "1") (pinfunction "1_1") (pintype "passive"))
    )
    (net (code "181") (name "Net-(IC25A--IN)") (class "Default")
      (node (ref "IC25") (pin "2") (pinfunction "-IN_2") (pintype "input"))
      (node (ref "R202") (pin "2") (pinfunction "2_2") (pintype "passive"))
      (node (ref "R203") (pin "1") (pinfunction "1_1") (pintype "passive"))
    )
    (net (code "182") (name "Net-(IC25A-OUT)") (class "Default")
      (node (ref "IC25") (pin "1") (pinfunction "OUT_1") (pintype "output"))
      (node (ref "R203") (pin "2") (pinfunction "2_2") (pintype "passive"))
      (node (ref "R204") (pin "1") (pinfunction "1_1") (pintype "passive"))
    )
    (net (code "183") (name "Net-(IC25B--IN)") (class "Default")
      (node (ref "IC25") (pin "6") (pinfunction "-IN_6") (pintype "input"))
      (node (ref "R204") (pin "2") (pinfunction "2_2") (pintype "passive"))
      (node (ref "R205") (pin "1") (pinfunction "1_1") (pintype "passive"))
    )
    (net (code "184") (name "Net-(IC25B-OUT)") (class "Default")
      (node (ref "IC25") (pin "7") (pinfunction "OUT_7") (pintype "output"))
      (node (ref "R205") (pin "2") (pinfunction "2_2") (pintype "passive"))
      (node (ref "R206") (pin "1") (pinfunction "1_1") (pintype "passive"))
    )
    (net (code "185") (name "Net-(IC25C--IN)") (class "Default")
      (node (ref "IC25") (pin "9") (pinfunction "-IN_9") (pintype "input"))
      (node (ref "R206") (pin "2") (pinfunction "2_2") (pintype "passive"))
      (node (ref "R207") (pin "2") (pinfunction "2_2") (pintype "passive"))
      (node (ref "R210") (pin "1") (pinfunction "1_1") (pintype "passive"))
    )
    (net (code "186") (name "Net-(IC25C-OUT)") (class "Default")
      (node (ref "IC25") (pin "8") (pinfunction "OUT_8") (pintype "output"))
      (node (ref "R208") (pin "1") (pinfunction "1_1") (pintype "passive"))
      (node (ref "R210") (pin "2") (pinfunction "2_2") (pintype "passive"))
    )
    (net (code "187") (name "Net-(IC25D--IN)") (class "Default")
      (node (ref "IC25") (pin "13") (pinfunction "-IN_13") (pintype "input"))
      (node (ref "R208") (pin "2") (pinfunction "2_2") (pintype "passive"))
      (node (ref "R209") (pin "1") (pinfunction "1_1") (pintype "passive"))
    )
    (net (code "188") (name "Net-(IC26A--IN)") (class "Default")
      (node (ref "IC26") (pin "2") (pinfunction "-IN_2") (pintype "input"))
      (node (ref "R211") (pin "2") (pinfunction "2_2") (pintype "passive"))
      (node (ref "R212") (pin "1") (pinfunction "1_1") (pintype "passive"))
    )
    (net (code "189") (name "Net-(IC26A-OUT)") (class "Default")
      (node (ref "IC26") (pin "1") (pinfunction "OUT_1") (pintype "output"))
      (node (ref "R212") (pin "2") (pinfunction "2_2") (pintype "passive"))
      (node (ref "R213") (pin "1") (pinfunction "1_1") (pintype "passive"))
    )
    (net (code "190") (name "Net-(IC26B--IN)") (class "Default")
      (node (ref "IC26") (pin "6") (pinfunction "-IN_6") (pintype "input"))
      (node (ref "R213") (pin "2") (pinfunction "2_2") (pintype "passive"))
      (node (ref "R214") (pin "1") (pinfunction "1_1") (pintype "passive"))
    )
    (net (code "191") (name "Net-(IC26B-OUT)") (class "Default")
      (node (ref "IC26") (pin "7") (pinfunction "OUT_7") (pintype "output"))
      (node (ref "R214") (pin "2") (pinfunction "2_2") (pintype "passive"))
      (node (ref "R215") (pin "1") (pinfunction "1_1") (pintype "passive"))
    )
    (net (code "192") (name "Net-(IC26C--IN)") (class "Default")
      (node (ref "IC26") (pin "9") (pinfunction "-IN_9") (pintype "input"))
      (node (ref "R215") (pin "2") (pinfunction "2_2") (pintype "passive"))
      (node (ref "R216") (pin "2") (pinfunction "2_2") (pintype "passive"))
      (node (ref "R219") (pin "1") (pinfunction "1_1") (pintype "passive"))
    )
    (net (code "193") (name "Net-(IC26C-OUT)") (class "Default")
      (node (ref "IC26") (pin "8") (pinfunction "OUT_8") (pintype "output"))
      (node (ref "R217") (pin "1") (pinfunction "1_1") (pintype "passive"))
      (node (ref "R219") (pin "2") (pinfunction "2_2") (pintype "passive"))
    )
    (net (code "194") (name "Net-(IC26D--IN)") (class "Default")
      (node (ref "IC26") (pin "13") (pinfunction "-IN_13") (pintype "input"))
      (node (ref "R217") (pin "2") (pinfunction "2_2") (pintype "passive"))
      (node (ref "R218") (pin "1") (pinfunction "1_1") (pintype "passive"))
    )
    (net (code "195") (name "Net-(IC27A--IN)") (class "Default")
      (node (ref "IC27") (pin "2") (pinfunction "-IN_2") (pintype "input"))
      (node (ref "R220") (pin "2") (pinfunction "2_2") (pintype "passive"))
      (node (ref "R221") (pin "1") (pinfunction "1_1") (pintype "passive"))
    )
    (net (code "196") (name "Net-(IC27A-OUT)") (class "Default")
      (node (ref "IC27") (pin "1") (pinfunction "OUT_1") (pintype "output"))
      (node (ref "R221") (pin "2") (pinfunction "2_2") (pintype "passive"))
      (node (ref "R222") (pin "1") (pinfunction "1_1") (pintype "passive"))
    )
    (net (code "197") (name "Net-(IC27B--IN)") (class "Default")
      (node (ref "IC27") (pin "6") (pinfunction "-IN_6") (pintype "input"))
      (node (ref "R222") (pin "2") (pinfunction "2_2") (pintype "passive"))
      (node (ref "R223") (pin "1") (pinfunction "1_1") (pintype "passive"))
    )
    (net (code "198") (name "Net-(IC27B-OUT)") (class "Default")
      (node (ref "IC27") (pin "7") (pinfunction "OUT_7") (pintype "output"))
      (node (ref "R223") (pin "2") (pinfunction "2_2") (pintype "passive"))
      (node (ref "R224") (pin "1") (pinfunction "1_1") (pintype "passive"))
    )
    (net (code "199") (name "Net-(IC27C--IN)") (class "Default")
      (node (ref "IC27") (pin "9") (pinfunction "-IN_9") (pintype "input"))
      (node (ref "R224") (pin "2") (pinfunction "2_2") (pintype "passive"))
      (node (ref "R225") (pin "2") (pinfunction "2_2") (pintype "passive"))
      (node (ref "R228") (pin "1") (pinfunction "1_1") (pintype "passive"))
    )
    (net (code "200") (name "Net-(IC27C-OUT)") (class "Default")
      (node (ref "IC27") (pin "8") (pinfunction "OUT_8") (pintype "output"))
      (node (ref "R226") (pin "1") (pinfunction "1_1") (pintype "passive"))
      (node (ref "R228") (pin "2") (pinfunction "2_2") (pintype "passive"))
    )
    (net (code "201") (name "Net-(IC27D--IN)") (class "Default")
      (node (ref "IC27") (pin "13") (pinfunction "-IN_13") (pintype "input"))
      (node (ref "R226") (pin "2") (pinfunction "2_2") (pintype "passive"))
      (node (ref "R227") (pin "1") (pinfunction "1_1") (pintype "passive"))
    )
    (net (code "202") (name "Net-(IC28A--IN)") (class "Default")
      (node (ref "IC28") (pin "2") (pinfunction "-IN_2") (pintype "input"))
      (node (ref "R229") (pin "2") (pinfunction "2_2") (pintype "passive"))
      (node (ref "R230") (pin "1") (pinfunction "1_1") (pintype "passive"))
    )
    (net (code "203") (name "Net-(IC28A-OUT)") (class "Default")
      (node (ref "IC28") (pin "1") (pinfunction "OUT_1") (pintype "output"))
      (node (ref "R230") (pin "2") (pinfunction "2_2") (pintype "passive"))
      (node (ref "R231") (pin "1") (pinfunction "1_1") (pintype "passive"))
    )
    (net (code "204") (name "Net-(IC28B--IN)") (class "Default")
      (node (ref "IC28") (pin "6") (pinfunction "-IN_6") (pintype "input"))
      (node (ref "R231") (pin "2") (pinfunction "2_2") (pintype "passive"))
      (node (ref "R232") (pin "1") (pinfunction "1_1") (pintype "passive"))
    )
    (net (code "205") (name "Net-(IC28B-OUT)") (class "Default")
      (node (ref "IC28") (pin "7") (pinfunction "OUT_7") (pintype "output"))
      (node (ref "R232") (pin "2") (pinfunction "2_2") (pintype "passive"))
      (node (ref "R233") (pin "1") (pinfunction "1_1") (pintype "passive"))
    )
    (net (code "206") (name "Net-(IC28C--IN)") (class "Default")
      (node (ref "IC28") (pin "9") (pinfunction "-IN_9") (pintype "input"))
      (node (ref "R233") (pin "2") (pinfunction "2_2") (pintype "passive"))
      (node (ref "R234") (pin "2") (pinfunction "2_2") (pintype "passive"))
      (node (ref "R237") (pin "1") (pinfunction "1_1") (pintype "passive"))
    )
    (net (code "207") (name "Net-(IC28C-OUT)") (class "Default")
      (node (ref "IC28") (pin "8") (pinfunction "OUT_8") (pintype "output"))
      (node (ref "R235") (pin "1") (pinfunction "1_1") (pintype "passive"))
      (node (ref "R237") (pin "2") (pinfunction "2_2") (pintype "passive"))
    )
    (net (code "208") (name "Net-(IC28D--IN)") (class "Default")
      (node (ref "IC28") (pin "13") (pinfunction "-IN_13") (pintype "input"))
      (node (ref "R235") (pin "2") (pinfunction "2_2") (pintype "passive"))
      (node (ref "R236") (pin "1") (pinfunction "1_1") (pintype "passive"))
    )
    (net (code "209") (name "Net-(IC29A--IN)") (class "Default")
      (node (ref "IC29") (pin "2") (pinfunction "-IN_2") (pintype "input"))
      (node (ref "R238") (pin "2") (pinfunction "2_2") (pintype "passive"))
      (node (ref "R239") (pin "1") (pinfunction "1_1") (pintype "passive"))
    )
    (net (code "210") (name "Net-(IC29A-OUT)") (class "Default")
      (node (ref "IC29") (pin "1") (pinfunction "OUT_1") (pintype "output"))
      (node (ref "R239") (pin "2") (pinfunction "2_2") (pintype "passive"))
      (node (ref "R240") (pin "1") (pinfunction "1_1") (pintype "passive"))
    )
    (net (code "211") (name "Net-(IC29B--IN)") (class "Default")
      (node (ref "IC29") (pin "6") (pinfunction "-IN_6") (pintype "input"))
      (node (ref "R240") (pin "2") (pinfunction "2_2") (pintype "passive"))
      (node (ref "R241") (pin "1") (pinfunction "1_1") (pintype "passive"))
    )
    (net (code "212") (name "Net-(IC29B-OUT)") (class "Default")
      (node (ref "IC29") (pin "7") (pinfunction "OUT_7") (pintype "output"))
      (node (ref "R241") (pin "2") (pinfunction "2_2") (pintype "passive"))
      (node (ref "R242") (pin "1") (pinfunction "1_1") (pintype "passive"))
    )
    (net (code "213") (name "Net-(IC29C--IN)") (class "Default")
      (node (ref "IC29") (pin "9") (pinfunction "-IN_9") (pintype "input"))
      (node (ref "R242") (pin "2") (pinfunction "2_2") (pintype "passive"))
      (node (ref "R243") (pin "2") (pinfunction "2_2") (pintype "passive"))
      (node (ref "R246") (pin "1") (pinfunction "1_1") (pintype "passive"))
    )
    (net (code "214") (name "Net-(IC29C-OUT)") (class "Default")
      (node (ref "IC29") (pin "8") (pinfunction "OUT_8") (pintype "output"))
      (node (ref "R244") (pin "1") (pinfunction "1_1") (pintype "passive"))
      (node (ref "R246") (pin "2") (pinfunction "2_2") (pintype "passive"))
    )
    (net (code "215") (name "Net-(IC29D--IN)") (class "Default")
      (node (ref "IC29") (pin "13") (pinfunction "-IN_13") (pintype "input"))
      (node (ref "R244") (pin "2") (pinfunction "2_2") (pintype "passive"))
      (node (ref "R245") (pin "1") (pinfunction "1_1") (pintype "passive"))
    )
    (net (code "216") (name "Net-(IC30A--IN)") (class "Default")
      (node (ref "IC30") (pin "2") (pinfunction "-IN_2") (pintype "input"))
      (node (ref "R247") (pin "2") (pinfunction "2_2") (pintype "passive"))
      (node (ref "R248") (pin "1") (pinfunction "1_1") (pintype "passive"))
    )
    (net (code "217") (name "Net-(IC30A-OUT)") (class "Default")
      (node (ref "IC30") (pin "1") (pinfunction "OUT_1") (pintype "output"))
      (node (ref "R248") (pin "2") (pinfunction "2_2") (pintype "passive"))
      (node (ref "R249") (pin "1") (pinfunction "1_1") (pintype "passive"))
    )
    (net (code "218") (name "Net-(IC30B--IN)") (class "Default")
      (node (ref "IC30") (pin "6") (pinfunction "-IN_6") (pintype "input"))
      (node (ref "R249") (pin "2") (pinfunction "2_2") (pintype "passive"))
      (node (ref "R250") (pin "1") (pinfunction "1_1") (pintype "passive"))
    )
    (net (code "219") (name "Net-(IC30B-OUT)") (class "Default")
      (node (ref "IC30") (pin "7") (pinfunction "OUT_7") (pintype "output"))
      (node (ref "R250") (pin "2") (pinfunction "2_2") (pintype "passive"))
      (node (ref "R251") (pin "1") (pinfunction "1_1") (pintype "passive"))
    )
    (net (code "220") (name "Net-(IC30C--IN)") (class "Default")
      (node (ref "IC30") (pin "9") (pinfunction "-IN_9") (pintype "input"))
      (node (ref "R251") (pin "2") (pinfunction "2_2") (pintype "passive"))
      (node (ref "R252") (pin "2") (pinfunction "2_2") (pintype "passive"))
      (node (ref "R255") (pin "1") (pinfunction "1_1") (pintype "passive"))
    )
    (net (code "221") (name "Net-(IC30C-OUT)") (class "Default")
      (node (ref "IC30") (pin "8") (pinfunction "OUT_8") (pintype "output"))
      (node (ref "R253") (pin "1") (pinfunction "1_1") (pintype "passive"))
      (node (ref "R255") (pin "2") (pinfunction "2_2") (pintype "passive"))
    )
    (net (code "222") (name "Net-(IC30D--IN)") (class "Default")
      (node (ref "IC30") (pin "13") (pinfunction "-IN_13") (pintype "input"))
      (node (ref "R253") (pin "2") (pinfunction "2_2") (pintype "passive"))
      (node (ref "R254") (pin "1") (pinfunction "1_1") (pintype "passive"))
    )
    (net (code "223") (name "Net-(JP2-Pad1)") (class "Default")
      (node (ref "JP2") (pin "1") (pinfunction "1_1") (pintype "passive"))
      (node (ref "R4") (pin "2") (pinfunction "2_2") (pintype "passive"))
    )
    (net (code "224") (name "Net-(JP7-Pad1)") (class "Default")
      (node (ref "JP7") (pin "1") (pinfunction "1_1") (pintype "passive"))
      (node (ref "R9") (pin "1") (pinfunction "1_1") (pintype "passive"))
    )
    (net (code "225") (name "Net-(JP10-Pad2)") (class "Default")
      (node (ref "JP10") (pin "2") (pinfunction "2_2") (pintype "passive"))
      (node (ref "R11") (pin "1") (pinfunction "1_1") (pintype "passive"))
    )
    (net (code "226") (name "Net-(LED1-PadA)") (class "Default")
      (node (ref "LED1") (pin "A") (pinfunction "A_A") (pintype "passive"))
      (node (ref "R2") (pin "1") (pinfunction "1_1") (pintype "passive"))
    )
    (net (code "227") (name "Net-(LED2-PadA)") (class "Default")
      (node (ref "LED2") (pin "A") (pinfunction "A_A") (pintype "passive"))
      (node (ref "R3") (pin "1") (pinfunction "1_1") (pintype "passive"))
    )
    (net (code "228") (name "Net-(LED4-PadA)") (class "Default")
      (node (ref "LED4") (pin "A") (pinfunction "A_A") (pintype "passive"))
      (node (ref "R15") (pin "1") (pinfunction "1_1") (pintype "passive"))
    )
    (net (code "229") (name "Net-(LED5-C)") (class "Default")
      (node (ref "LED5") (pin "K") (pinfunction "C_K") (pintype "passive"))
      (node (ref "R13") (pin "1") (pinfunction "1_1") (pintype "passive"))
    )
    (net (code "230") (name "Net-(LED6-PadA)") (class "Default")
      (node (ref "LED6") (pin "A") (pinfunction "A_A") (pintype "passive"))
      (node (ref "R16") (pin "1") (pinfunction "1_1") (pintype "passive"))
    )
    (net (code "231") (name "Net-(Q1-PadB)") (class "Default")
      (node (ref "Q1") (pin "B") (pinfunction "B_B") (pintype "passive"))
      (node (ref "R196") (pin "2") (pinfunction "2_2") (pintype "passive"))
    )
    (net (code "232") (name "Net-(R12-Pad2)") (class "Default")
      (node (ref "R12") (pin "2") (pinfunction "2_2") (pintype "passive"))
      (node (ref "SV2") (pin "14") (pinfunction "14_14") (pintype "passive"))
    )
    (net (code "233") (name "Net-(R18-Pad2)") (class "Default")
      (node (ref "R18") (pin "2") (pinfunction "2_2") (pintype "passive"))
      (node (ref "SV2") (pin "13") (pinfunction "13_13") (pintype "passive"))
    )
    (net (code "234") (name "Net-(U1-VDD)") (class "Default")
      (node (ref "C13") (pin "2") (pinfunction "2_2") (pintype "passive"))
      (node (ref "U1") (pin "72") (pinfunction "VDD_72") (pintype "power_in"))
    )
    (net (code "235") (name "Net-(U1-VDD3VFL)") (class "Default")
      (node (ref "R23") (pin "1") (pinfunction "1_1") (pintype "passive"))
      (node (ref "U1") (pin "37") (pinfunction "VDD3VFL_37") (pintype "power_in"))
    )
    (net (code "236") (name "Net-(U1-VDDA)") (class "Default")
      (node (ref "C7") (pin "1") (pinfunction "1_1") (pintype "passive"))
      (node (ref "R22") (pin "1") (pinfunction "1_1") (pintype "passive"))
      (node (ref "U1") (pin "20") (pinfunction "VDDA_20") (pintype "power_in"))
    )
    (net (code "237") (name "Net-(U1-VDD_2)") (class "Default")
      (node (ref "C9") (pin "1") (pinfunction "1_1") (pintype "passive"))
      (node (ref "U1") (pin "2") (pinfunction "VDD_2_2") (pintype "power_in"))
    )
    (net (code "238") (name "Net-(U1-VDD_3)") (class "Default")
      (node (ref "C8") (pin "1") (pinfunction "1_1") (pintype "passive"))
      (node (ref "U1") (pin "12") (pinfunction "VDD_3_12") (pintype "power_in"))
    )
    (net (code "239") (name "Net-(U1-VDD_4)") (class "Default")
      (node (ref "C10") (pin "1") (pinfunction "1_1") (pintype "passive"))
      (node (ref "U1") (pin "29") (pinfunction "VDD_4_29") (pintype "power_in"))
    )
    (net (code "240") (name "Net-(U1-VDD_5)") (class "Default")
      (node (ref "C11") (pin "2") (pinfunction "2_2") (pintype "passive"))
      (node (ref "U1") (pin "51") (pinfunction "VDD_5_51") (pintype "power_in"))
    )
    (net (code "241") (name "Net-(U1-VDD_6)") (class "Default")
      (node (ref "C12") (pin "2") (pinfunction "2_2") (pintype "passive"))
      (node (ref "U1") (pin "65") (pinfunction "VDD_6_65") (pintype "power_in"))
    )
    (net (code "242") (name "Net-(U1-X1)") (class "Default")
      (node (ref "C20") (pin "1") (pinfunction "1_1") (pintype "passive"))
      (node (ref "R21") (pin "2") (pinfunction "2_2") (pintype "passive"))
      (node (ref "U1") (pin "48") (pinfunction "X1_48") (pintype "input"))
      (node (ref "Y1") (pin "2") (pinfunction "2_2") (pintype "passive"))
    )
    (net (code "243") (name "Net-(U1-X2)") (class "Default")
      (node (ref "C21") (pin "1") (pinfunction "1_1") (pintype "passive"))
      (node (ref "R21") (pin "1") (pinfunction "1_1") (pintype "passive"))
      (node (ref "U1") (pin "47") (pinfunction "X2_47") (pintype "output"))
      (node (ref "Y1") (pin "1") (pinfunction "1_1") (pintype "passive"))
    )
    (net (code "244") (name "RST_OUT") (class "Default")
      (node (ref "C22") (pin "2") (pinfunction "2_2") (pintype "passive"))
      (node (ref "Q1") (pin "E") (pinfunction "E_E") (pintype "passive"))
      (node (ref "R7") (pin "1") (pinfunction "1_1") (pintype "passive"))
      (node (ref "S2") (pin "P$3") (pinfunction "1_P$3") (pintype "passive"))
      (node (ref "S2") (pin "P$4") (pinfunction "1_P$4") (pintype "passive"))
      (node (ref "U1") (pin "9") (pinfunction "~{XRS}_9") (pintype "bidirectional"))
    )
    (net (code "245") (name "RXD") (class "Default")
      (node (ref "IC1") (pin "5") (pinfunction "RXD_5") (pintype "input"))
      (node (ref "JP4") (pin "1") (pinfunction "1_1") (pintype "passive"))
      (node (ref "U1") (pin "34") (pinfunction "GPIO29/SCITXDA/SCLA/~{TZ3}_34") (pintype "bidirectional"))
    )
    (net (code "246") (name "SPI_CLK") (class "Default")
      (node (ref "U1") (pin "41") (pinfunction "GPIO18/SPICLKA/SCITXDB/XCLKOUT_41") (pintype "bidirectional"))
      (node (ref "U3") (pin "3") (pinfunction "SCLK_3") (pintype "input"))
    )
    (net (code "247") (name "SPI_CLK_SW") (class "Default")
      (node (ref "U1") (pin "62") (pinfunction "GPIO26/ECAP3/SPICLKB/USB0DP_62") (pintype "bidirectional"))
      (node (ref "U4") (pin "1") (pinfunction "SCLK_1") (pintype "input"))
      (node (ref "U6") (pin "1") (pinfunction "SCLK_1") (pintype "input"))
      (node (ref "U7") (pin "1") (pinfunction "SCLK_1") (pintype "input"))
    )
    (net (code "248") (name "SPI_CS") (class "Default")
      (node (ref "U1") (pin "52") (pinfunction "GPIO19/XCLKIN/~{SPISTEA/SCIRXDB/ECAP1}_52") (pintype "bidirectional"))
      (node (ref "U3") (pin "4") (pinfunction "FS_4") (pintype "input"))
    )
    (net (code "249") (name "SPI_MISO") (class "Default")
      (node (ref "U1") (pin "66") (pinfunction "GPIO3/EPWM2B/SPISOMIA/COMP2OUT_66") (pintype "bidirectional"))
      (node (ref "U3") (pin "19") (pinfunction "DOUT_19") (pintype "output"))
    )
    (net (code "250") (name "SPI_MISO_SW") (class "Default")
      (node (ref "U1") (pin "31") (pinfunction "GPIO25/ECAP2/SPISOMIB_31") (pintype "bidirectional"))
      (node (ref "U7") (pin "22") (pinfunction "DOUT_22") (pintype "output"))
    )
    (net (code "251") (name "SPI_MOSI") (class "Default")
      (node (ref "U1") (pin "8") (pinfunction "GPIO5/EPWM3B/SPISIMOA/ECAP1_8") (pintype "bidirectional"))
      (node (ref "U3") (pin "2") (pinfunction "DIN_2") (pintype "input"))
    )
    (net (code "252") (name "SPI_MOSI_SW") (class "Default")
      (node (ref "U1") (pin "77") (pinfunction "GPIO24/ECAP1/SPISIMOB_77") (pintype "bidirectional"))
      (node (ref "U4") (pin "3") (pinfunction "DIN_3") (pintype "input"))
    )
    (net (code "253") (name "TCK") (class "Default")
      (node (ref "SV2") (pin "11") (pinfunction "11_11") (pintype "passive"))
      (node (ref "SV2") (pin "9") (pinfunction "9_9") (pintype "passive"))
      (node (ref "U1") (pin "54") (pinfunction "GPIO38/XCLKIN/TCK_54") (pintype "bidirectional"))
    )
    (net (code "254") (name "TDI") (class "Default")
      (node (ref "SV2") (pin "3") (pinfunction "3_3") (pintype "passive"))
      (node (ref "U1") (pin "57") (pinfunction "GPIO35/TDI_57") (pintype "bidirectional"))
    )
    (net (code "255") (name "TDO") (class "Default")
      (node (ref "JP10") (pin "1") (pinfunction "1_1") (pintype "passive"))
      (node (ref "R10") (pin "2") (pinfunction "2_2") (pintype "passive"))
      (node (ref "SV2") (pin "7") (pinfunction "7_7") (pintype "passive"))
      (node (ref "U1") (pin "56") (pinfunction "GPIO37/TDO_56") (pintype "bidirectional"))
    )
    (net (code "256") (name "TMS") (class "Default")
      (node (ref "SV2") (pin "1") (pinfunction "1_1") (pintype "passive"))
      (node (ref "U1") (pin "58") (pinfunction "GPIO36/TMS_58") (pintype "bidirectional"))
    )
    (net (code "257") (name "TO_NEXT1") (class "Default")
      (node (ref "U4") (pin "22") (pinfunction "DOUT_22") (pintype "output"))
      (node (ref "U6") (pin "3") (pinfunction "DIN_3") (pintype "input"))
    )
    (net (code "258") (name "TO_NEXT2") (class "Default")
      (node (ref "U6") (pin "22") (pinfunction "DOUT_22") (pintype "output"))
      (node (ref "U7") (pin "3") (pinfunction "DIN_3") (pintype "input"))
    )
    (net (code "259") (name "TRST") (class "Default")
      (node (ref "JP11") (pin "1") (pinfunction "1_1") (pintype "passive"))
      (node (ref "R8") (pin "2") (pinfunction "2_2") (pintype "passive"))
      (node (ref "U1") (pin "10") (pinfunction "~{TRST}_10") (pintype "input"))
    )
    (net (code "260") (name "TXD") (class "Default")
      (node (ref "IC1") (pin "1") (pinfunction "TXD_1") (pintype "output"))
      (node (ref "JP4") (pin "3") (pinfunction "3_3") (pintype "passive"))
      (node (ref "U1") (pin "40") (pinfunction "GPIO28/SCIRXDA/SDAA/~{TZ2}_40") (pintype "bidirectional"))
    )
    (net (code "261") (name "U1") (class "Default")
      (node (ref "JP12") (pin "11") (pinfunction "11_11") (pintype "passive"))
      (node (ref "R176") (pin "1") (pinfunction "1_1") (pintype "passive"))
    )
    (net (code "262") (name "U2") (class "Default")
      (node (ref "JP12") (pin "3") (pinfunction "3_3") (pintype "passive"))
      (node (ref "R175") (pin "1") (pinfunction "1_1") (pintype "passive"))
    )
    (net (code "263") (name "VBUS") (class "Default")
      (node (ref "C4") (pin "1") (pinfunction "1_1") (pintype "passive"))
      (node (ref "C5") (pin "1") (pinfunction "1_1") (pintype "passive"))
      (node (ref "F2") (pin "2") (pinfunction "2_2") (pintype "bidirectional"))
      (node (ref "IC1") (pin "20") (pinfunction "VCC_20") (pintype "power_in"))
      (node (ref "JP6") (pin "1") (pinfunction "1_1") (pintype "passive"))
    )
    (net (code "264") (name "VBUS_ORG") (class "Default")
      (node (ref "C3") (pin "1") (pinfunction "1_1") (pintype "passive"))
      (node (ref "CON1") (pin "1") (pinfunction "1_1") (pintype "passive"))
      (node (ref "F2") (pin "1") (pinfunction "1_1") (pintype "bidirectional"))
    )
    (net (code "265") (name "VIN+") (class "Default")
      (node (ref "D1") (pin "A") (pinfunction "A_A") (pintype "passive"))
      (node (ref "JP13") (pin "1") (pinfunction "1_1") (pintype "passive"))
    )
    (net (code "266") (name "VIN-") (class "Default")
      (node (ref "D3") (pin "C") (pinfunction "C_C") (pintype "passive"))
      (node (ref "JP17") (pin "1") (pinfunction "1_1") (pintype "passive"))
    )
    (net (code "267") (name "VIN1") (class "Default")
      (node (ref "C37") (pin "1") (pinfunction "1_1") (pintype "passive"))
      (node (ref "IC23") (pin "1") (pinfunction "OUT_1") (pintype "output"))
      (node (ref "JP15") (pin "1") (pinfunction "1_1") (pintype "passive"))
      (node (ref "R141") (pin "2") (pinfunction "2_2") (pintype "passive"))
      (node (ref "R247") (pin "1") (pinfunction "1_1") (pintype "passive"))
    )
    (net (code "268") (name "VIN1_INV") (class "Default")
      (node (ref "IC22") (pin "14") (pinfunction "OUT_14") (pintype "output"))
      (node (ref "R150") (pin "2") (pinfunction "2_2") (pintype "passive"))
      (node (ref "U6") (pin "10") (pinfunction "COM2_10") (pintype "passive"))
      (node (ref "U6") (pin "11") (pinfunction "NO3_11") (pintype "passive"))
    )
    (net (code "269") (name "VIN1_SW") (class "Default")
      (node (ref "JP12") (pin "12") (pinfunction "12_12") (pintype "passive"))
      (node (ref "R149") (pin "1") (pinfunction "1_1") (pintype "passive"))
      (node (ref "U6") (pin "6") (pinfunction "COM0_6") (pintype "passive"))
      (node (ref "U6") (pin "7") (pinfunction "NO1_7") (pintype "passive"))
    )
    (net (code "270") (name "VIN2") (class "Default")
      (node (ref "C38") (pin "1") (pinfunction "1_1") (pintype "passive"))
      (node (ref "IC23") (pin "7") (pinfunction "OUT_7") (pintype "output"))
      (node (ref "JP15") (pin "3") (pinfunction "3_3") (pintype "passive"))
      (node (ref "R140") (pin "2") (pinfunction "2_2") (pintype "passive"))
      (node (ref "R229") (pin "1") (pinfunction "1_1") (pintype "passive"))
    )
    (net (code "271") (name "VIN2_INV") (class "Default")
      (node (ref "IC22") (pin "8") (pinfunction "OUT_8") (pintype "output"))
      (node (ref "R138") (pin "2") (pinfunction "2_2") (pintype "passive"))
      (node (ref "U7") (pin "6") (pinfunction "COM0_6") (pintype "passive"))
      (node (ref "U7") (pin "7") (pinfunction "NO1_7") (pintype "passive"))
    )
    (net (code "272") (name "VIN2_SW") (class "Default")
      (node (ref "JP12") (pin "4") (pinfunction "4_4") (pintype "passive"))
      (node (ref "R137") (pin "1") (pinfunction "1_1") (pintype "passive"))
      (node (ref "U7") (pin "10") (pinfunction "COM2_10") (pintype "passive"))
      (node (ref "U7") (pin "11") (pinfunction "NO3_11") (pintype "passive"))
    )
    (net (code "273") (name "VIN3") (class "Default")
      (node (ref "C36") (pin "1") (pinfunction "1_1") (pintype "passive"))
      (node (ref "IC23") (pin "8") (pinfunction "OUT_8") (pintype "output"))
      (node (ref "JP15") (pin "5") (pinfunction "5_5") (pintype "passive"))
      (node (ref "R139") (pin "2") (pinfunction "2_2") (pintype "passive"))
      (node (ref "R211") (pin "1") (pinfunction "1_1") (pintype "passive"))
    )
    (net (code "274") (name "VIN4") (class "Default")
      (node (ref "C35") (pin "1") (pinfunction "1_1") (pintype "passive"))
      (node (ref "IC23") (pin "14") (pinfunction "OUT_14") (pintype "output"))
      (node (ref "JP15") (pin "7") (pinfunction "7_7") (pintype "passive"))
      (node (ref "R142") (pin "2") (pinfunction "2_2") (pintype "passive"))
      (node (ref "R202") (pin "1") (pinfunction "1_1") (pintype "passive"))
    )
    (net (code "275") (name "VIN5") (class "Default")
      (node (ref "C41") (pin "1") (pinfunction "1_1") (pintype "passive"))
      (node (ref "IC24") (pin "1") (pinfunction "OUT_1") (pintype "output"))
      (node (ref "JP15") (pin "2") (pinfunction "2_2") (pintype "passive"))
      (node (ref "R159") (pin "2") (pinfunction "2_2") (pintype "passive"))
      (node (ref "R26") (pin "1") (pinfunction "1_1") (pintype "passive"))
    )
    (net (code "276") (name "VIN6") (class "Default")
      (node (ref "C42") (pin "1") (pinfunction "1_1") (pintype "passive"))
      (node (ref "IC24") (pin "7") (pinfunction "OUT_7") (pintype "output"))
      (node (ref "JP15") (pin "4") (pinfunction "4_4") (pintype "passive"))
      (node (ref "R1") (pin "1") (pinfunction "1_1") (pintype "passive"))
      (node (ref "R158") (pin "2") (pinfunction "2_2") (pintype "passive"))
    )
    (net (code "277") (name "VIN7") (class "Default")
      (node (ref "C40") (pin "1") (pinfunction "1_1") (pintype "passive"))
      (node (ref "IC24") (pin "8") (pinfunction "OUT_8") (pintype "output"))
      (node (ref "JP15") (pin "6") (pinfunction "6_6") (pintype "passive"))
      (node (ref "R157") (pin "2") (pinfunction "2_2") (pintype "passive"))
      (node (ref "R220") (pin "1") (pinfunction "1_1") (pintype "passive"))
    )
    (net (code "278") (name "VIN8") (class "Default")
      (node (ref "C39") (pin "1") (pinfunction "1_1") (pintype "passive"))
      (node (ref "IC24") (pin "14") (pinfunction "OUT_14") (pintype "output"))
      (node (ref "JP15") (pin "8") (pinfunction "8_8") (pintype "passive"))
      (node (ref "R160") (pin "2") (pinfunction "2_2") (pintype "passive"))
      (node (ref "R238") (pin "1") (pinfunction "1_1") (pintype "passive"))
    )
    (net (code "279") (name "unconnected-(CON1-Pad4)") (class "Default")
      (node (ref "CON1") (pin "4") (pinfunction "4_4") (pintype "passive"))
    )
    (net (code "280") (name "unconnected-(IC1-CBUS2-Pad13)") (class "Default")
      (node (ref "IC1") (pin "13") (pinfunction "CBUS2_13") (pintype "bidirectional"))
    )
    (net (code "281") (name "unconnected-(IC1-OSCI-Pad27)") (class "Default")
      (node (ref "IC1") (pin "27") (pinfunction "OSCI_27") (pintype "input"))
    )
    (net (code "282") (name "unconnected-(IC1-OSCO-Pad28)") (class "Default")
      (node (ref "IC1") (pin "28") (pinfunction "OSCO_28") (pintype "output"))
    )
    (net (code "283") (name "unconnected-(IC1-~{CTS}-Pad11)") (class "Default")
      (node (ref "IC1") (pin "11") (pinfunction "~{CTS}_11") (pintype "input"))
    )
    (net (code "284") (name "unconnected-(IC1-~{DCD}-Pad10)") (class "Default")
      (node (ref "IC1") (pin "10") (pinfunction "~{DCD}_10") (pintype "input"))
    )
    (net (code "285") (name "unconnected-(IC1-~{DSR}-Pad9)") (class "Default")
      (node (ref "IC1") (pin "9") (pinfunction "~{DSR}_9") (pintype "input"))
    )
    (net (code "286") (name "unconnected-(IC1-~{RI}-Pad6)") (class "Default")
      (node (ref "IC1") (pin "6") (pinfunction "~{RI}_6") (pintype "input"))
    )
    (net (code "287") (name "unconnected-(IC18C-+IN-Pad10)") (class "Default")
      (node (ref "IC18") (pin "10") (pinfunction "+IN_10") (pintype "input"))
    )
    (net (code "288") (name "unconnected-(IC18C--IN-Pad9)") (class "Default")
      (node (ref "IC18") (pin "9") (pinfunction "-IN_9") (pintype "input"))
    )
    (net (code "289") (name "unconnected-(IC18C-OUT-Pad8)") (class "Default")
      (node (ref "IC18") (pin "8") (pinfunction "OUT_8") (pintype "output"))
    )
    (net (code "290") (name "unconnected-(IC19C-+IN-Pad10)") (class "Default")
      (node (ref "IC19") (pin "10") (pinfunction "+IN_10") (pintype "input"))
    )
    (net (code "291") (name "unconnected-(IC19C--IN-Pad9)") (class "Default")
      (node (ref "IC19") (pin "9") (pinfunction "-IN_9") (pintype "input"))
    )
    (net (code "292") (name "unconnected-(IC19C-OUT-Pad8)") (class "Default")
      (node (ref "IC19") (pin "8") (pinfunction "OUT_8") (pintype "output"))
    )
    (net (code "293") (name "unconnected-(IC20C-+IN-Pad10)") (class "Default")
      (node (ref "IC20") (pin "10") (pinfunction "+IN_10") (pintype "input"))
    )
    (net (code "294") (name "unconnected-(IC20C--IN-Pad9)") (class "Default")
      (node (ref "IC20") (pin "9") (pinfunction "-IN_9") (pintype "input"))
    )
    (net (code "295") (name "unconnected-(IC20C-OUT-Pad8)") (class "Default")
      (node (ref "IC20") (pin "8") (pinfunction "OUT_8") (pintype "output"))
    )
    (net (code "296") (name "unconnected-(IC21C-+IN-Pad10)") (class "Default")
      (node (ref "IC21") (pin "10") (pinfunction "+IN_10") (pintype "input"))
    )
    (net (code "297") (name "unconnected-(IC21C--IN-Pad9)") (class "Default")
      (node (ref "IC21") (pin "9") (pinfunction "-IN_9") (pintype "input"))
    )
    (net (code "298") (name "unconnected-(IC21C-OUT-Pad8)") (class "Default")
      (node (ref "IC21") (pin "8") (pinfunction "OUT_8") (pintype "output"))
    )
    (net (code "299") (name "unconnected-(JP4-Pad9)") (class "Default")
      (node (ref "JP4") (pin "9") (pinfunction "9_9") (pintype "passive"))
    )
    (net (code "300") (name "unconnected-(JP4-Pad10)") (class "Default")
      (node (ref "JP4") (pin "10") (pinfunction "10_10") (pintype "passive"))
    )
    (net (code "301") (name "unconnected-(JP4-Pad12)") (class "Default")
      (node (ref "JP4") (pin "12") (pinfunction "12_12") (pintype "passive"))
    )
    (net (code "302") (name "unconnected-(JP8-Pad2)") (class "Default")
      (node (ref "JP8") (pin "2") (pinfunction "2_2") (pintype "passive"))
    )
    (net (code "303") (name "unconnected-(JP12-Pad7)") (class "Default")
      (node (ref "JP12") (pin "7") (pinfunction "7_7") (pintype "passive"))
    )
    (net (code "304") (name "unconnected-(JP12-Pad8)") (class "Default")
      (node (ref "JP12") (pin "8") (pinfunction "8_8") (pintype "passive"))
    )
    (net (code "305") (name "unconnected-(JP15-Pad9)") (class "Default")
      (node (ref "JP15") (pin "9") (pinfunction "9_9") (pintype "passive"))
    )
    (net (code "306") (name "unconnected-(JP15-Pad10)") (class "Default")
      (node (ref "JP15") (pin "10") (pinfunction "10_10") (pintype "passive"))
    )
    (net (code "307") (name "unconnected-(JP15-Pad11)") (class "Default")
      (node (ref "JP15") (pin "11") (pinfunction "11_11") (pintype "passive"))
    )
    (net (code "308") (name "unconnected-(JP15-Pad12)") (class "Default")
      (node (ref "JP15") (pin "12") (pinfunction "12_12") (pintype "passive"))
    )
    (net (code "309") (name "unconnected-(JP15-Pad13)") (class "Default")
      (node (ref "JP15") (pin "13") (pinfunction "13_13") (pintype "passive"))
    )
    (net (code "310") (name "unconnected-(JP15-Pad14)") (class "Default")
      (node (ref "JP15") (pin "14") (pinfunction "14_14") (pintype "passive"))
    )
    (net (code "311") (name "unconnected-(JP18-Pad1)") (class "Default")
      (node (ref "JP18") (pin "1") (pinfunction "1_1") (pintype "passive"))
    )
    (net (code "312") (name "unconnected-(JP18-Pad3)") (class "Default")
      (node (ref "JP18") (pin "3") (pinfunction "3_3") (pintype "passive"))
    )
    (net (code "313") (name "unconnected-(JP18-Pad5)") (class "Default")
      (node (ref "JP18") (pin "5") (pinfunction "5_5") (pintype "passive"))
    )
    (net (code "314") (name "unconnected-(JP18-Pad7)") (class "Default")
      (node (ref "JP18") (pin "7") (pinfunction "7_7") (pintype "passive"))
    )
    (net (code "315") (name "unconnected-(JP18-Pad9)") (class "Default")
      (node (ref "JP18") (pin "9") (pinfunction "9_9") (pintype "passive"))
    )
    (net (code "316") (name "unconnected-(JP18-Pad11)") (class "Default")
      (node (ref "JP18") (pin "11") (pinfunction "11_11") (pintype "passive"))
    )
    (net (code "317") (name "unconnected-(JP18-Pad13)") (class "Default")
      (node (ref "JP18") (pin "13") (pinfunction "13_13") (pintype "passive"))
    )
    (net (code "318") (name "unconnected-(JP18-Pad15)") (class "Default")
      (node (ref "JP18") (pin "15") (pinfunction "15_15") (pintype "passive"))
    )
    (net (code "319") (name "unconnected-(SV2-Pad6)") (class "Default")
      (node (ref "SV2") (pin "6") (pinfunction "6_6") (pintype "passive"))
    )
    (net (code "320") (name "unconnected-(U1-GPIO0{slash}EPWM1A-Pad69)") (class "Default")
      (node (ref "U1") (pin "69") (pinfunction "GPIO0/EPWM1A_69") (pintype "bidirectional"))
    )
    (net (code "321") (name "unconnected-(U1-GPIO1{slash}EPWM1B{slash}COMP1OUT-Pad68)") (class "Default")
      (node (ref "U1") (pin "68") (pinfunction "GPIO1/EPWM1B/COMP1OUT_68") (pintype "bidirectional"))
    )
    (net (code "322") (name "unconnected-(U1-GPIO2{slash}EPWM2A-Pad67)") (class "Default")
      (node (ref "U1") (pin "67") (pinfunction "GPIO2/EPWM2A_67") (pintype "bidirectional"))
    )
    (net (code "323") (name "unconnected-(U1-GPIO4{slash}EPWM3A-Pad7)") (class "Default")
      (node (ref "U1") (pin "7") (pinfunction "GPIO4/EPWM3A_7") (pintype "bidirectional"))
    )
    (net (code "324") (name "unconnected-(U1-GPIO6{slash}EPWM4A{slash}EPWMSYNCI{slash}EPWMSYNCO-Pad46)") (class "Default")
      (node (ref "U1") (pin "46") (pinfunction "GPIO6/EPWM4A/EPWMSYNCI/EPWMSYNCO_46") (pintype "bidirectional"))
    )
    (net (code "325") (name "unconnected-(U1-GPIO7{slash}EPWM4B{slash}SCIRXDA{slash}ECAP2-Pad45)") (class "Default")
      (node (ref "U1") (pin "45") (pinfunction "GPIO7/EPWM4B/SCIRXDA/ECAP2_45") (pintype "bidirectional"))
    )
    (net (code "326") (name "unconnected-(U1-GPIO8{slash}EPWM5A{slash}~{ADCSOCAO}-Pad43)") (class "Default")
      (node (ref "U1") (pin "43") (pinfunction "GPIO8/EPWM5A/~{ADCSOCAO}_43") (pintype "bidirectional"))
    )
    (net (code "327") (name "unconnected-(U1-GPIO9{slash}EPWM5B{slash}SCITXDB{slash}ECAP3-Pad39)") (class "Default")
      (node (ref "U1") (pin "39") (pinfunction "GPIO9/EPWM5B/SCITXDB/ECAP3_39") (pintype "bidirectional"))
    )
    (net (code "328") (name "unconnected-(U1-GPIO10{slash}EPWM6A{slash}~{ADCSOCBO}-Pad60)") (class "Default")
      (node (ref "U1") (pin "60") (pinfunction "GPIO10/EPWM6A/~{ADCSOCBO}_60") (pintype "bidirectional"))
    )
    (net (code "329") (name "unconnected-(U1-GPIO11{slash}EPWM6B{slash}SCIRXDB{slash}ECAP1-Pad59)") (class "Default")
      (node (ref "U1") (pin "59") (pinfunction "GPIO11/EPWM6B/SCIRXDB/ECAP1_59") (pintype "bidirectional"))
    )
    (net (code "330") (name "unconnected-(U1-GPIO12{slash}~{TZ1{slash}SCITXDA{slash}SPISIMOB}-Pad35)") (class "Default")
      (node (ref "U1") (pin "35") (pinfunction "GPIO12/~{TZ1/SCITXDA/SPISIMOB}_35") (pintype "bidirectional"))
    )
    (net (code "331") (name "unconnected-(U1-GPIO13{slash}~{TZ2{slash}SPISOMIB}-Pad75)") (class "Default")
      (node (ref "U1") (pin "75") (pinfunction "GPIO13/~{TZ2/SPISOMIB}_75") (pintype "bidirectional"))
    )
    (net (code "332") (name "unconnected-(U1-GPIO14{slash}~{TZ3{slash}SCITXDB{slash}SPICLKB}-Pad76)") (class "Default")
      (node (ref "U1") (pin "76") (pinfunction "GPIO14/~{TZ3/SCITXDB/SPICLKB}_76") (pintype "bidirectional"))
    )
    (net (code "333") (name "unconnected-(U1-GPIO16{slash}SPISIMOA{slash}~{TZ2}-Pad44)") (class "Default")
      (node (ref "U1") (pin "44") (pinfunction "GPIO16/SPISIMOA/~{TZ2}_44") (pintype "bidirectional"))
    )
    (net (code "334") (name "unconnected-(U1-GPIO17{slash}SPISOMIA{slash}~{TZ3}-Pad42)") (class "Default")
      (node (ref "U1") (pin "42") (pinfunction "GPIO17/SPISOMIA/~{TZ3}_42") (pintype "bidirectional"))
    )
    (net (code "335") (name "unconnected-(U1-GPIO20{slash}EQEP1A{slash}MDXA{slash}COMP1OUT-Pad5)") (class "Default")
      (node (ref "U1") (pin "5") (pinfunction "GPIO20/EQEP1A/MDXA/COMP1OUT_5") (pintype "bidirectional"))
    )
    (net (code "336") (name "unconnected-(U1-GPIO21{slash}EQEP1B{slash}MDRA{slash}COMP2OUT-Pad6)") (class "Default")
      (node (ref "U1") (pin "6") (pinfunction "GPIO21/EQEP1B/MDRA/COMP2OUT_6") (pintype "bidirectional"))
    )
    (net (code "337") (name "unconnected-(U1-GPIO22{slash}EQEP1S{slash}MCLKXA{slash}SCITXDB-Pad78)") (class "Default")
      (node (ref "U1") (pin "78") (pinfunction "GPIO22/EQEP1S/MCLKXA/SCITXDB_78") (pintype "bidirectional"))
    )
    (net (code "338") (name "unconnected-(U1-GPIO23{slash}EQEP1I{slash}MFSXA{slash}SCIRXDB-Pad1)") (class "Default")
      (node (ref "U1") (pin "1") (pinfunction "GPIO23/EQEP1I/MFSXA/SCIRXDB_1") (pintype "bidirectional"))
    )
    (net (code "339") (name "unconnected-(U1-GPIO27{slash}HRCAP2{slash}~{SPISTEB{slash}USB0DM}-Pad61)") (class "Default")
      (node (ref "U1") (pin "61") (pinfunction "GPIO27/HRCAP2/~{SPISTEB/USB0DM}_61") (pintype "bidirectional"))
    )
    (net (code "340") (name "unconnected-(U1-GPIO30{slash}CANRXA{slash}EPWM7A-Pad33)") (class "Default")
      (node (ref "U1") (pin "33") (pinfunction "GPIO30/CANRXA/EPWM7A_33") (pintype "bidirectional"))
    )
    (net (code "341") (name "unconnected-(U1-GPIO31{slash}CANTXA{slash}EPWM8A-Pad32)") (class "Default")
      (node (ref "U1") (pin "32") (pinfunction "GPIO31/CANTXA/EPWM8A_32") (pintype "bidirectional"))
    )
    (net (code "342") (name "unconnected-(U1-GPIO32{slash}SDAA{slash}EPWMSYNCI{slash}~{ADCSOCAO}-Pad79)") (class "Default")
      (node (ref "U1") (pin "79") (pinfunction "GPIO32/SDAA/EPWMSYNCI/~{ADCSOCAO}_79") (pintype "bidirectional"))
    )
    (net (code "343") (name "unconnected-(U1-GPIO33{slash}SCLA{slash}EPWMSYNCO{slash}~{ADCSOCBO}-Pad80)") (class "Default")
      (node (ref "U1") (pin "80") (pinfunction "GPIO33/SCLA/EPWMSYNCO/~{ADCSOCBO}_80") (pintype "bidirectional"))
    )
    (net (code "344") (name "unconnected-(U1-GPIO39-Pad53)") (class "Default")
      (node (ref "U1") (pin "53") (pinfunction "GPIO39_53") (pintype "bidirectional"))
    )
    (net (code "345") (name "unconnected-(U1-TEST2-Pad36)") (class "Default")
      (node (ref "U1") (pin "36") (pinfunction "TEST2_36") (pintype "bidirectional"))
    )
  )
)
